# PX4FMUv2_4_3.net
KiCad netlist of a schematic drawn in EAGLE
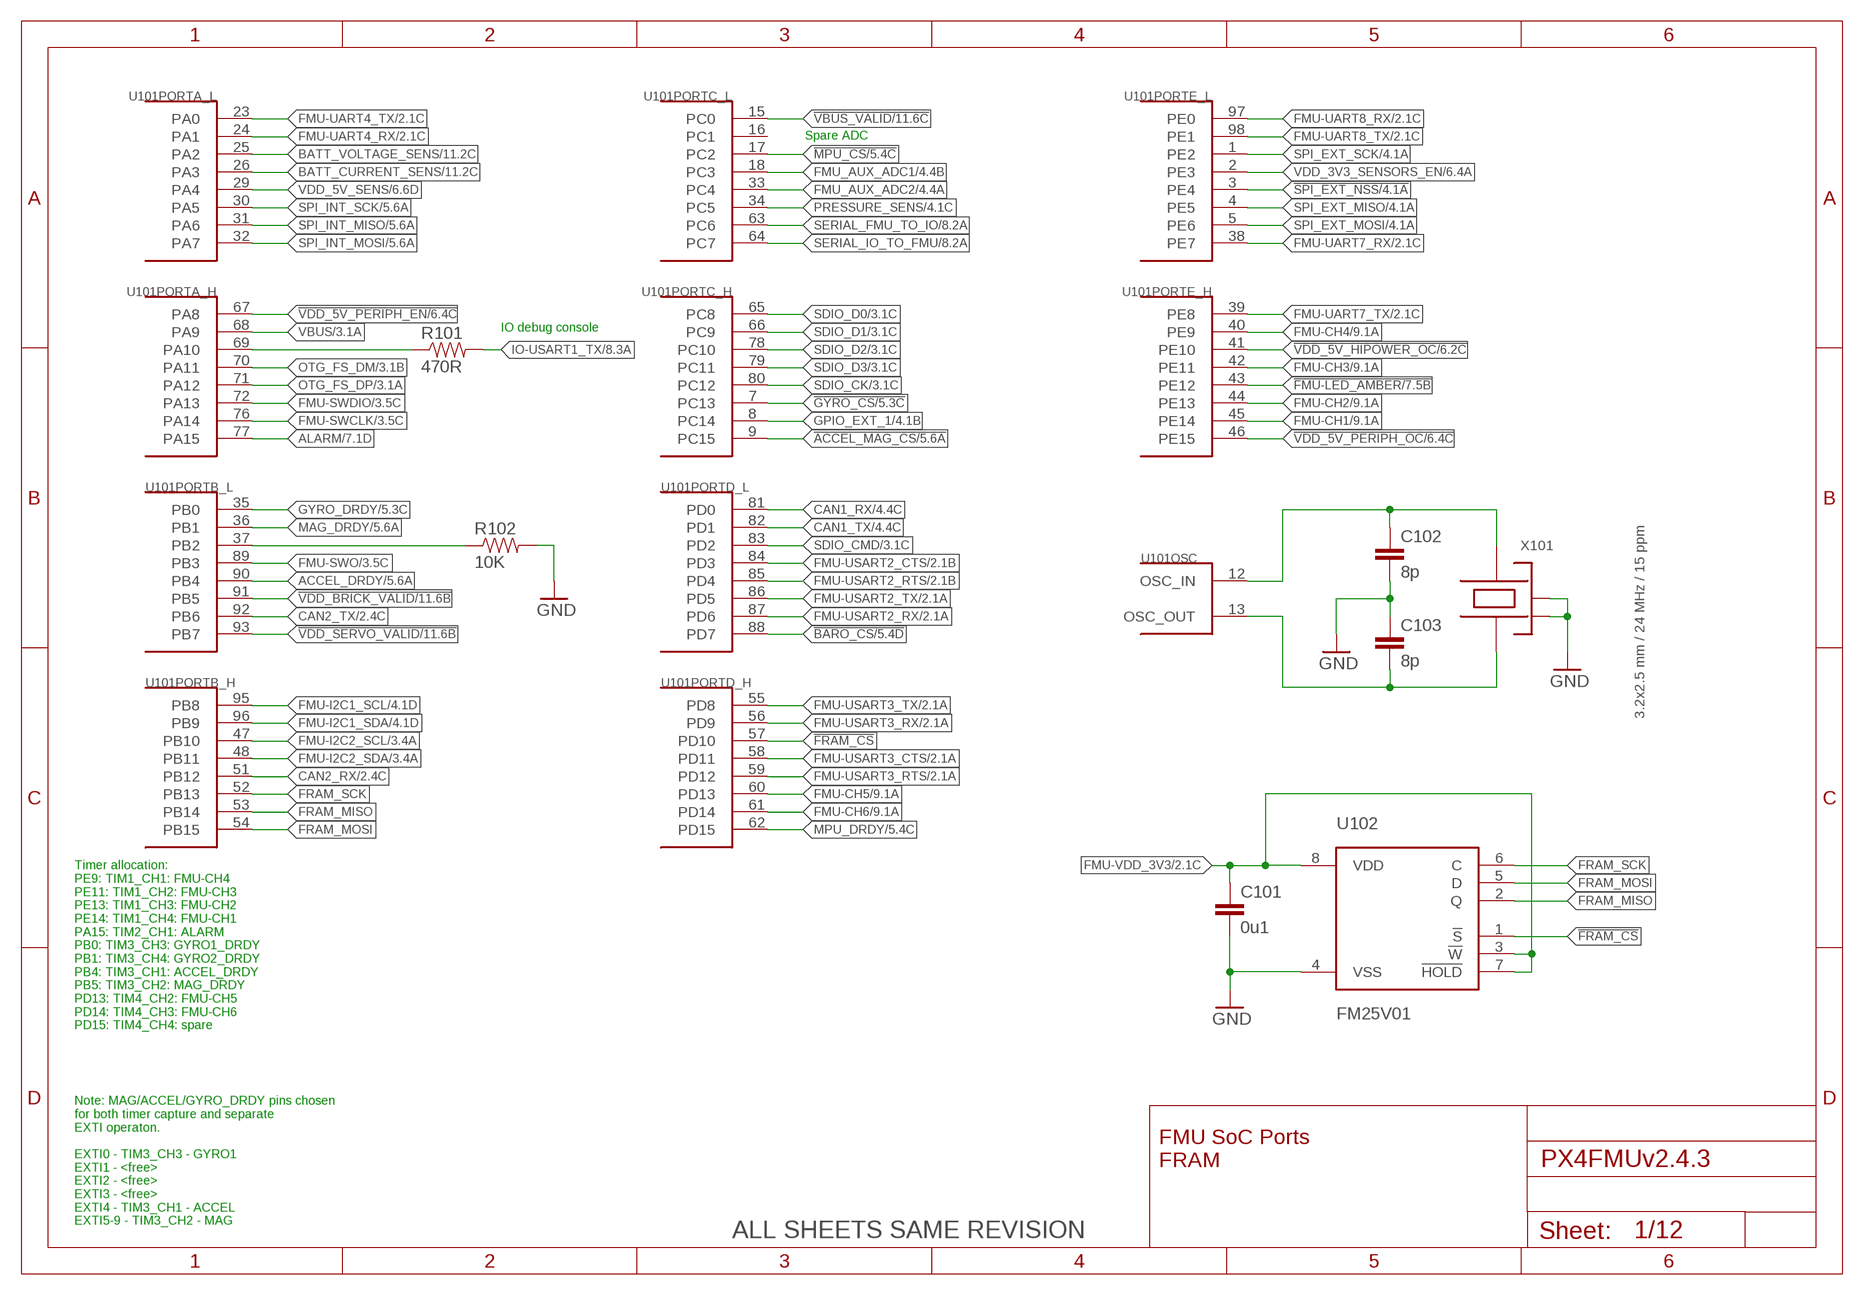
[diagram p0: schematic, sheet 1]
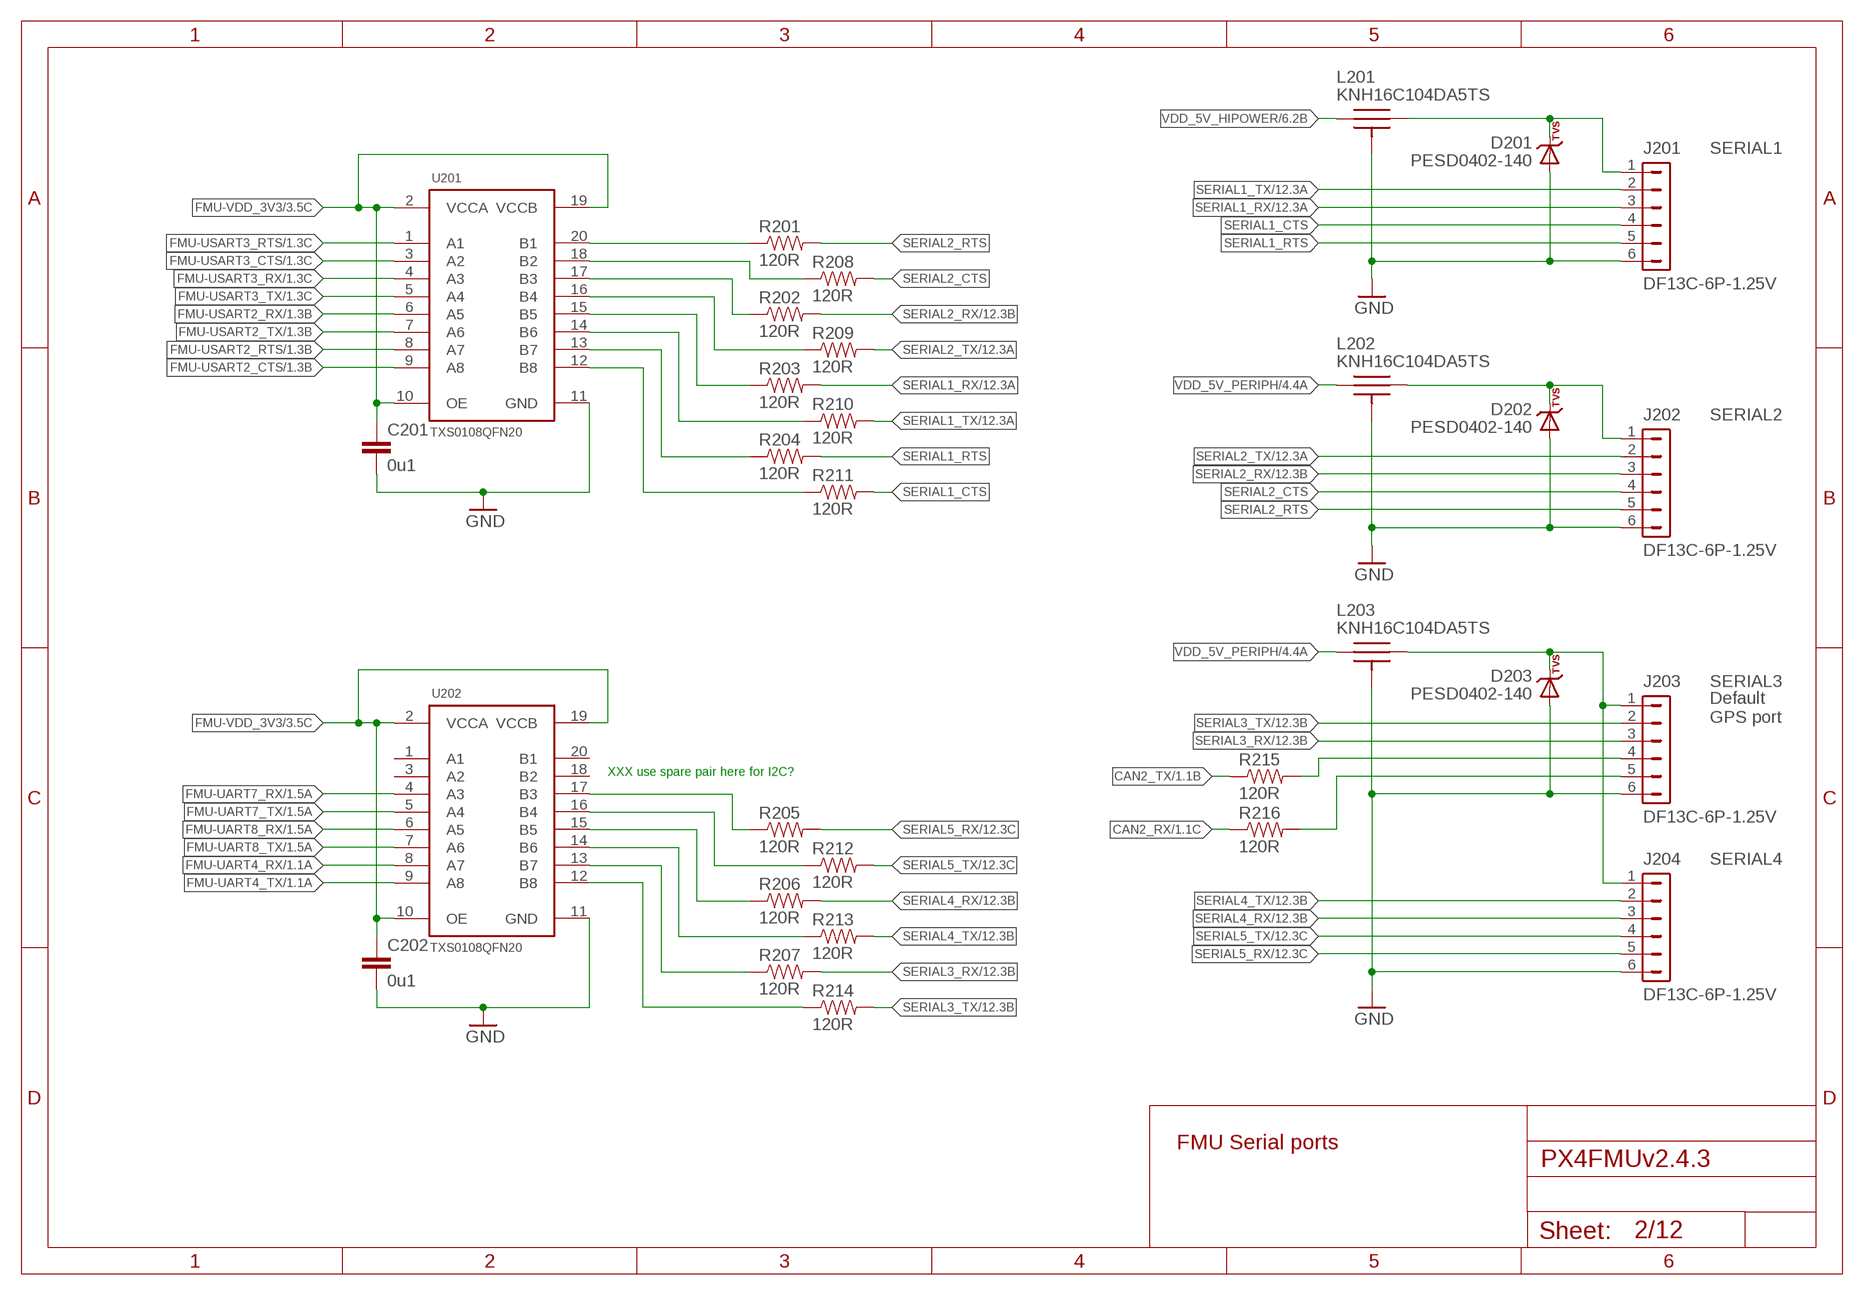
[diagram p1: schematic, sheet 2]
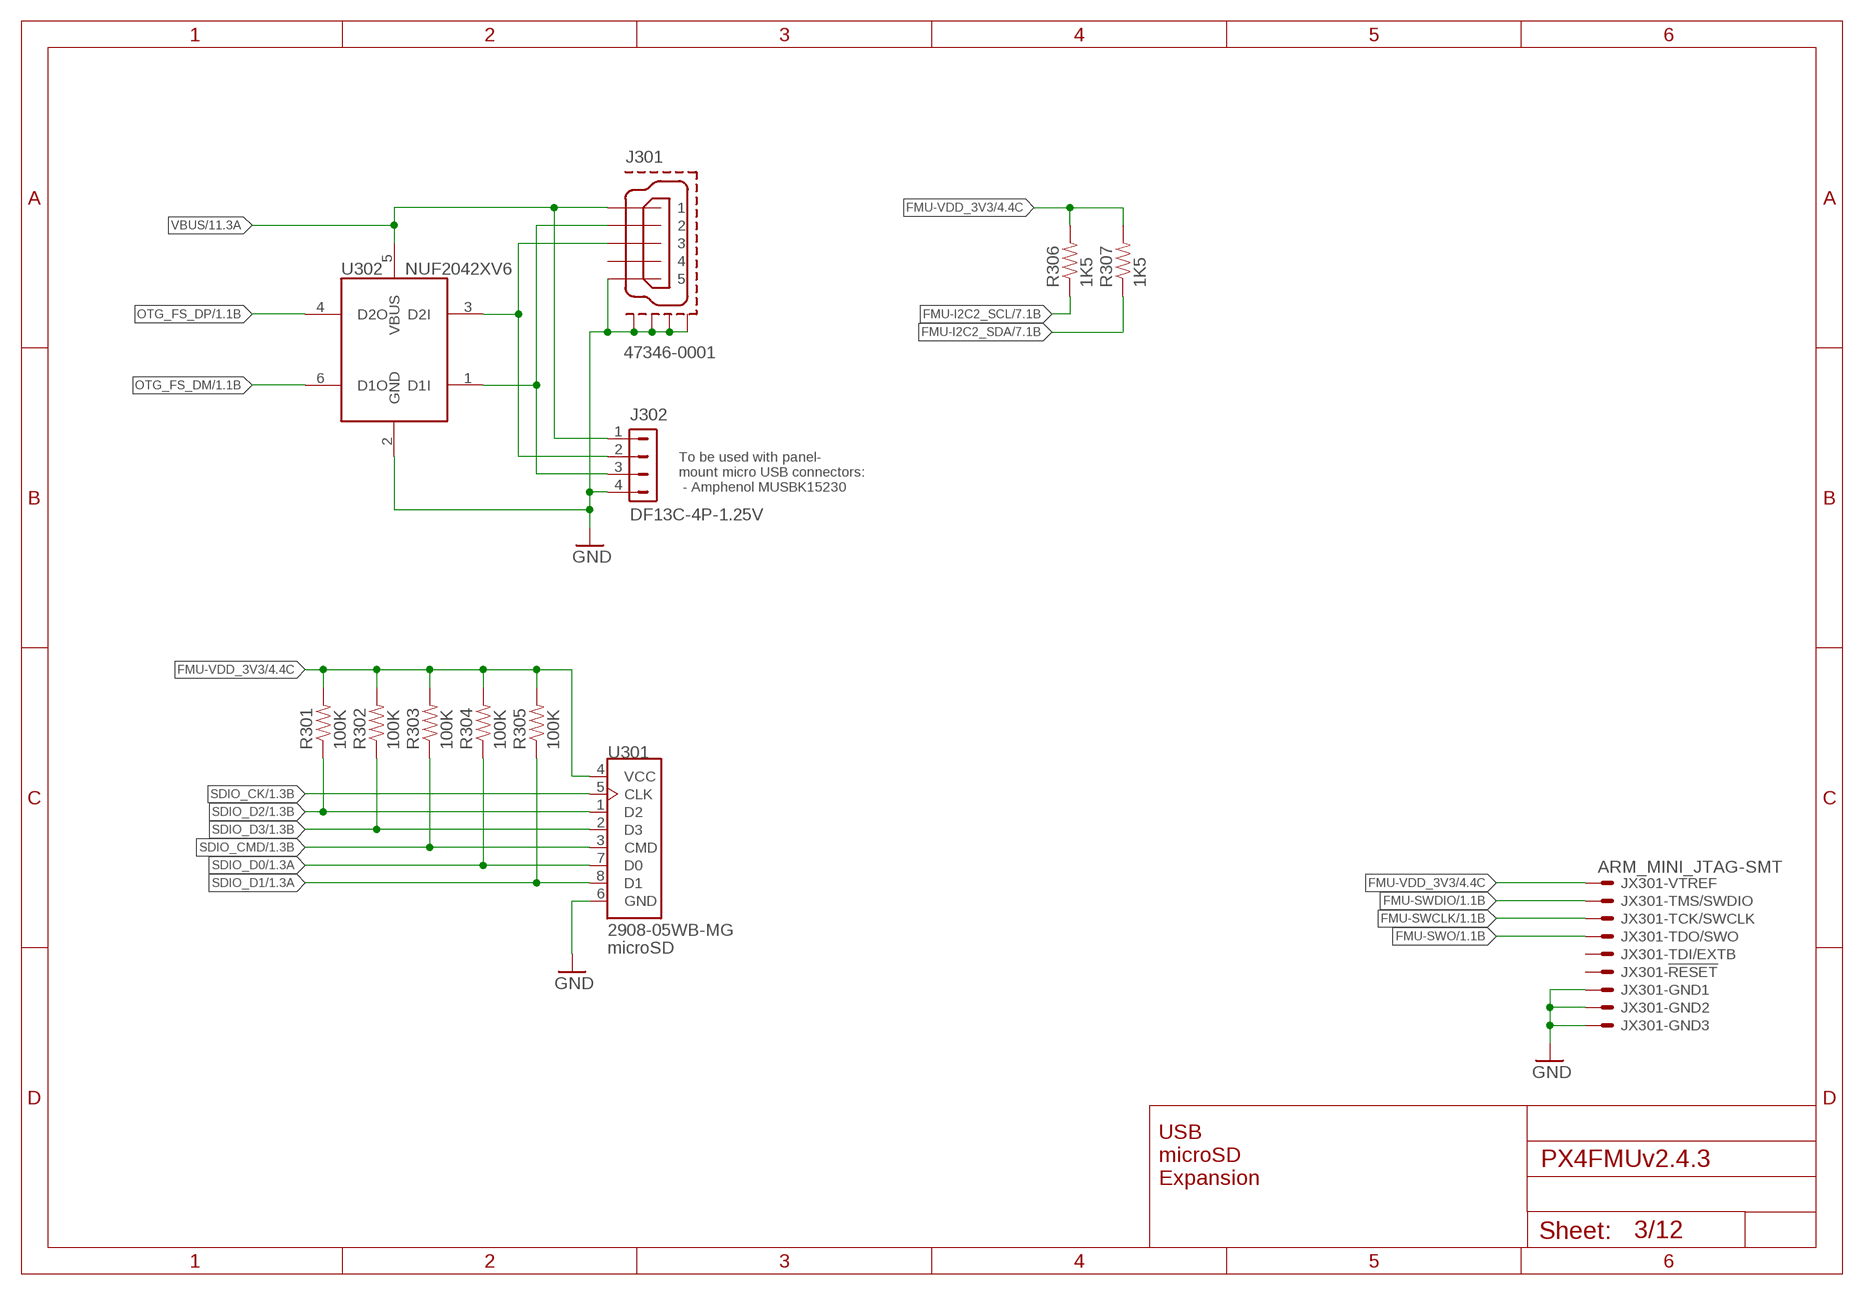
[diagram p2: schematic, sheet 3]
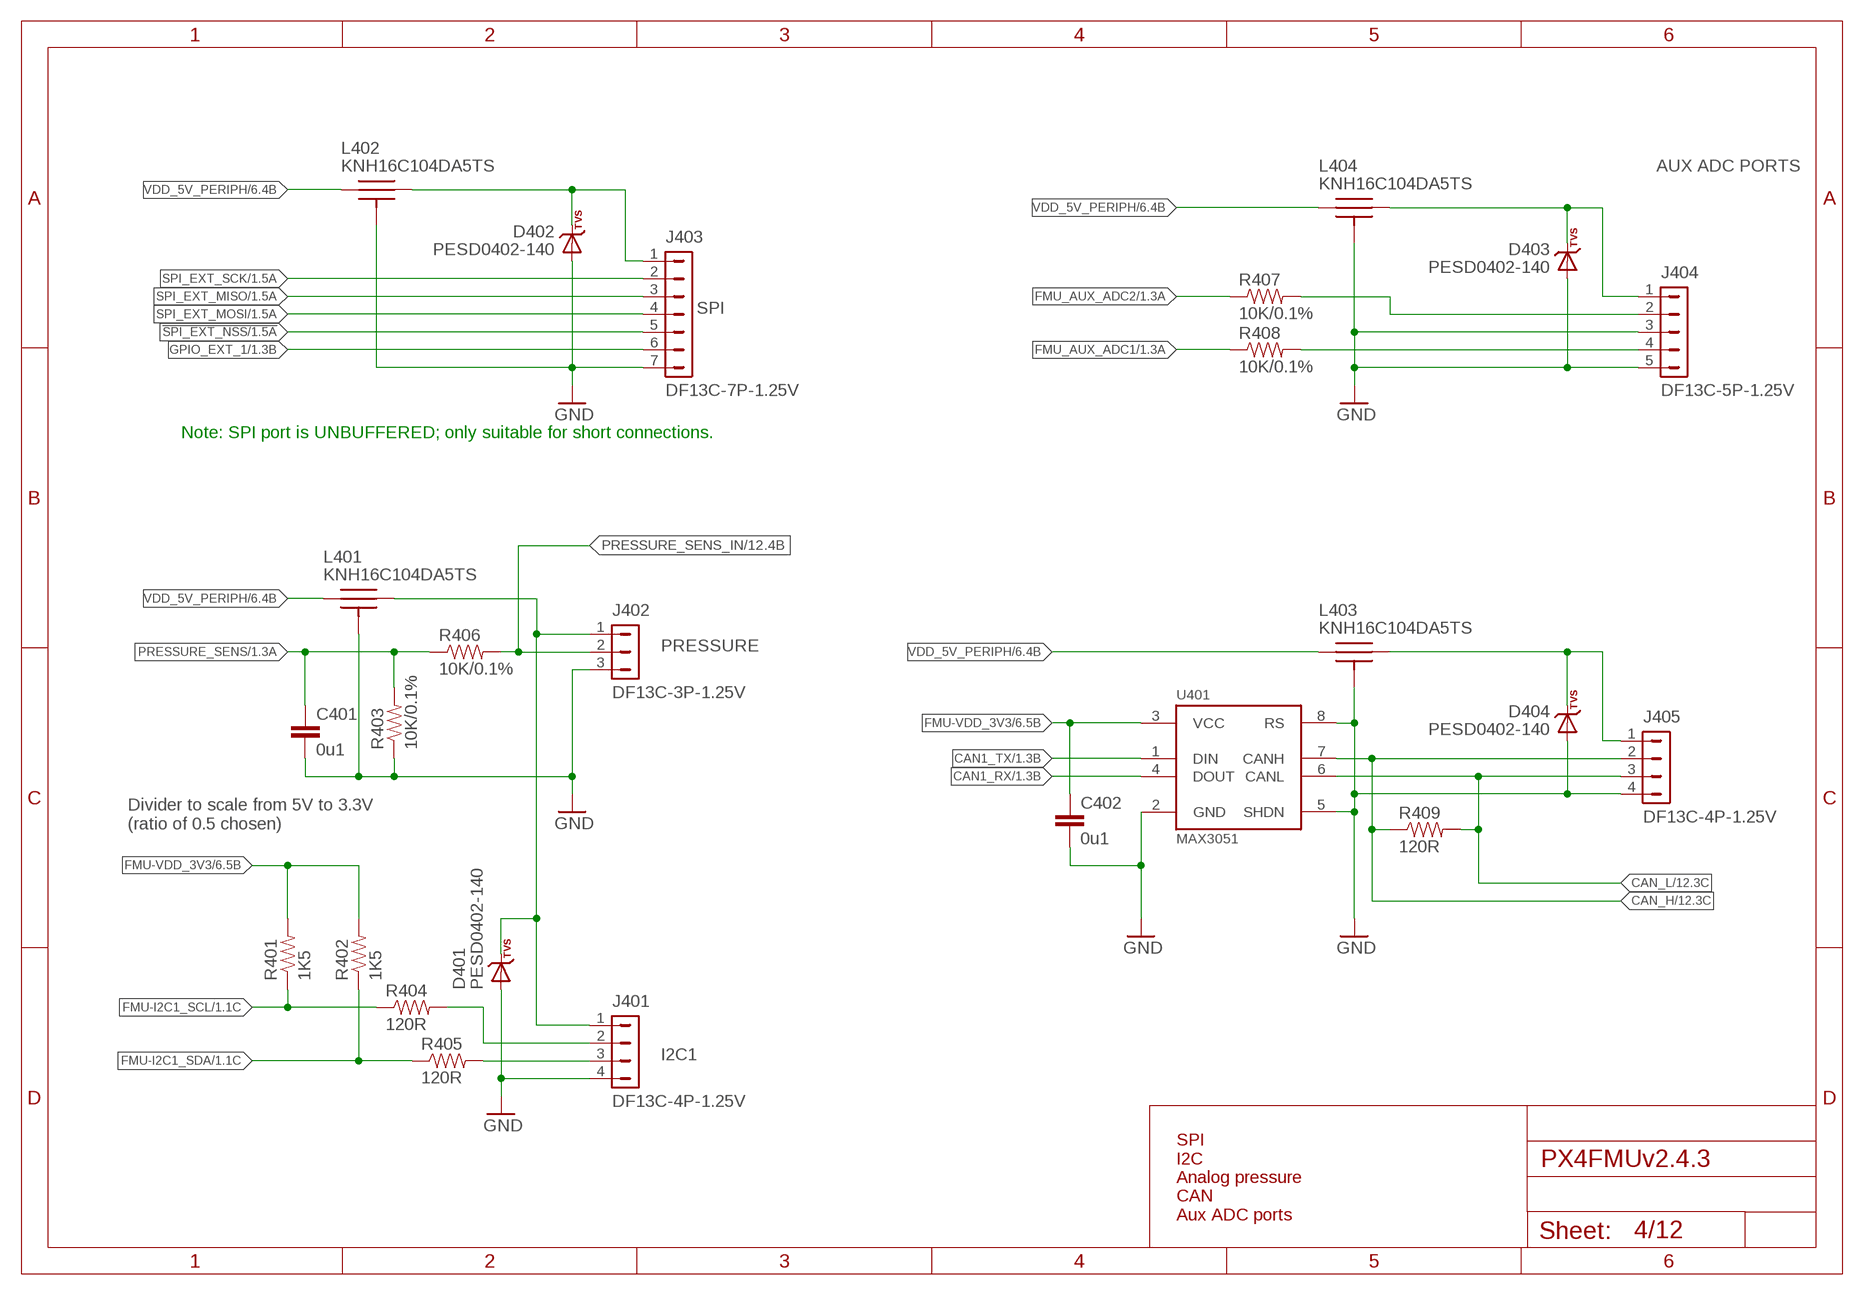
[diagram p3: schematic, sheet 4]
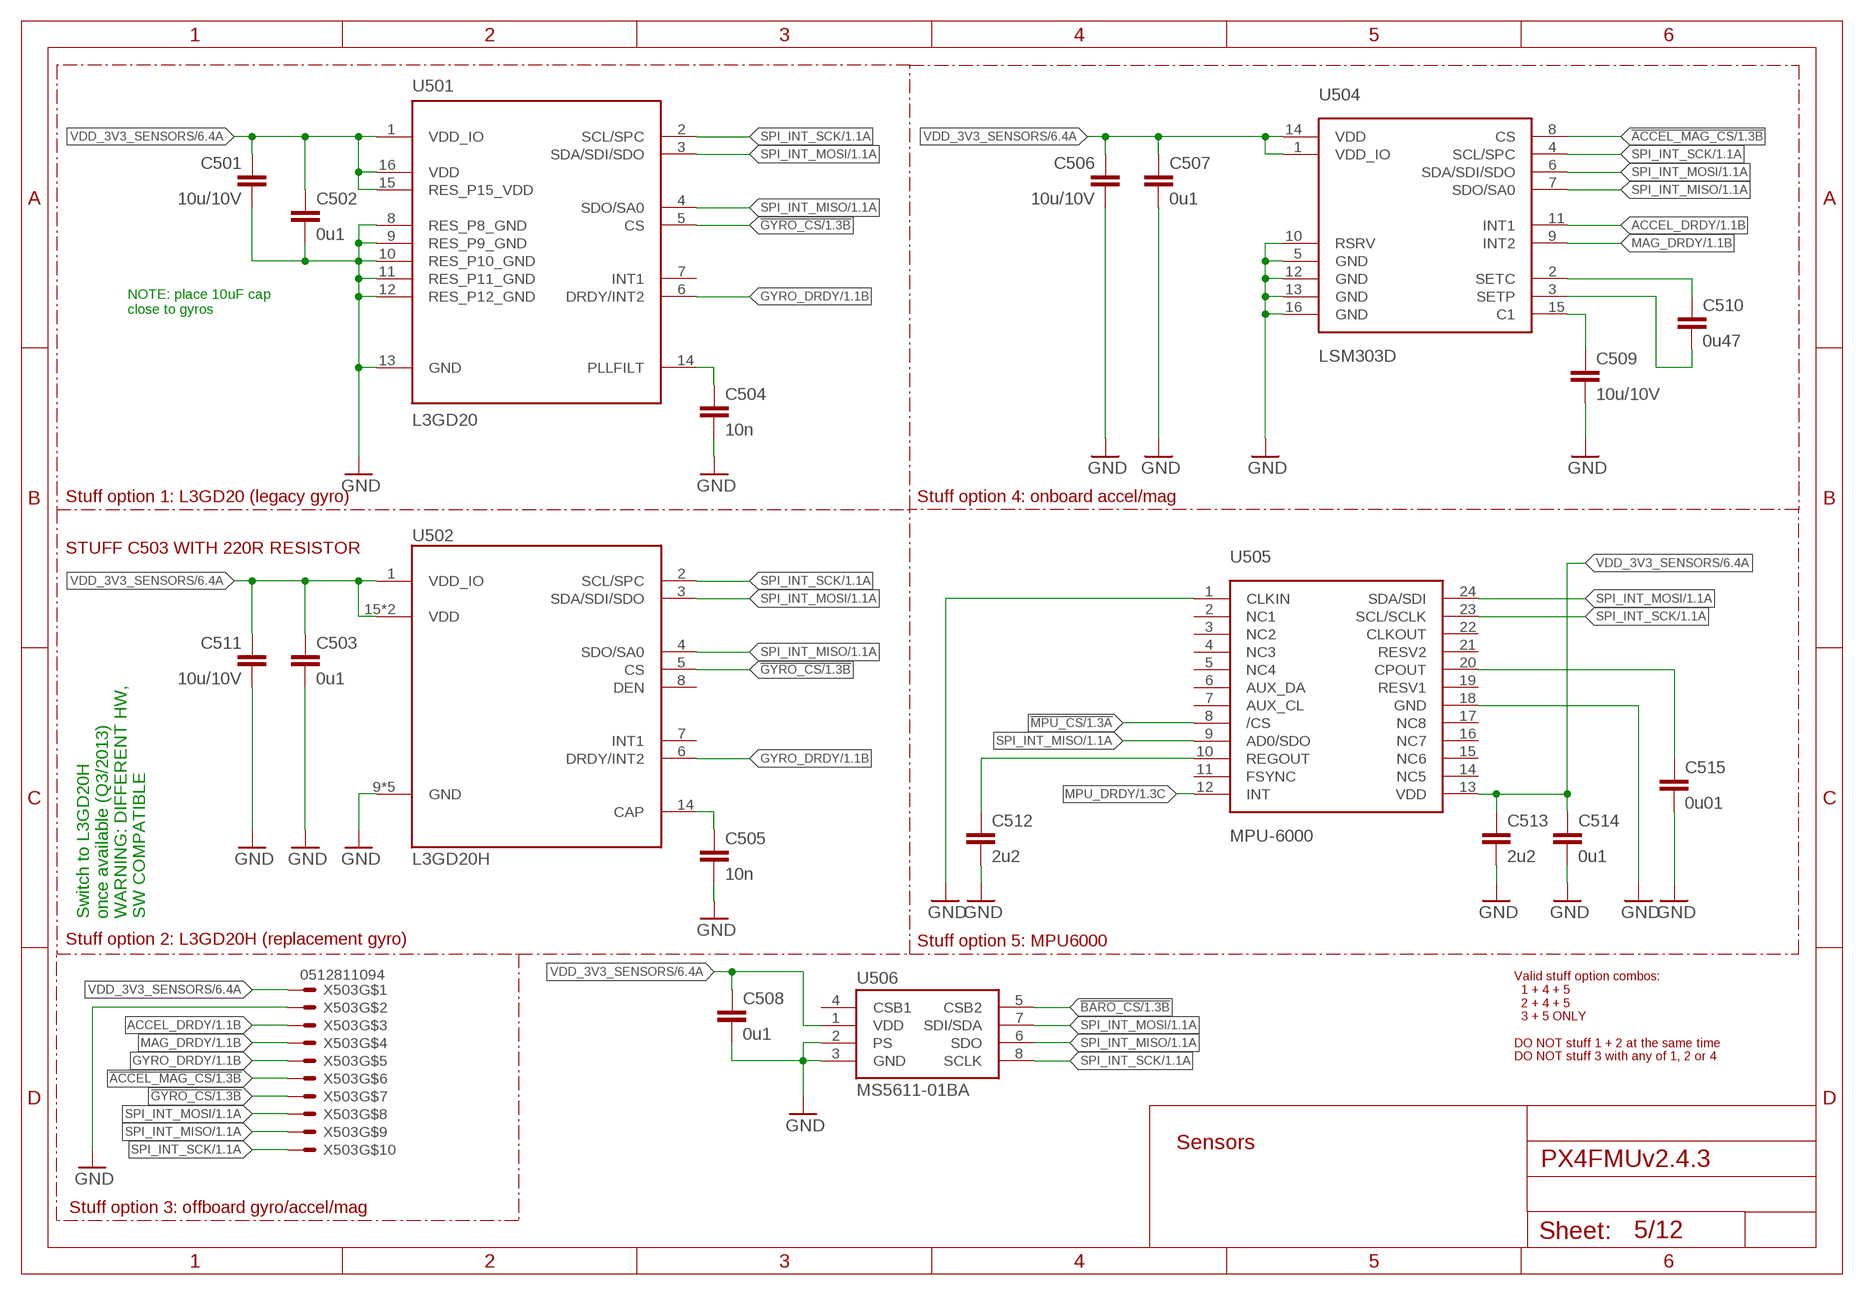
[diagram p4: schematic, sheet 5]
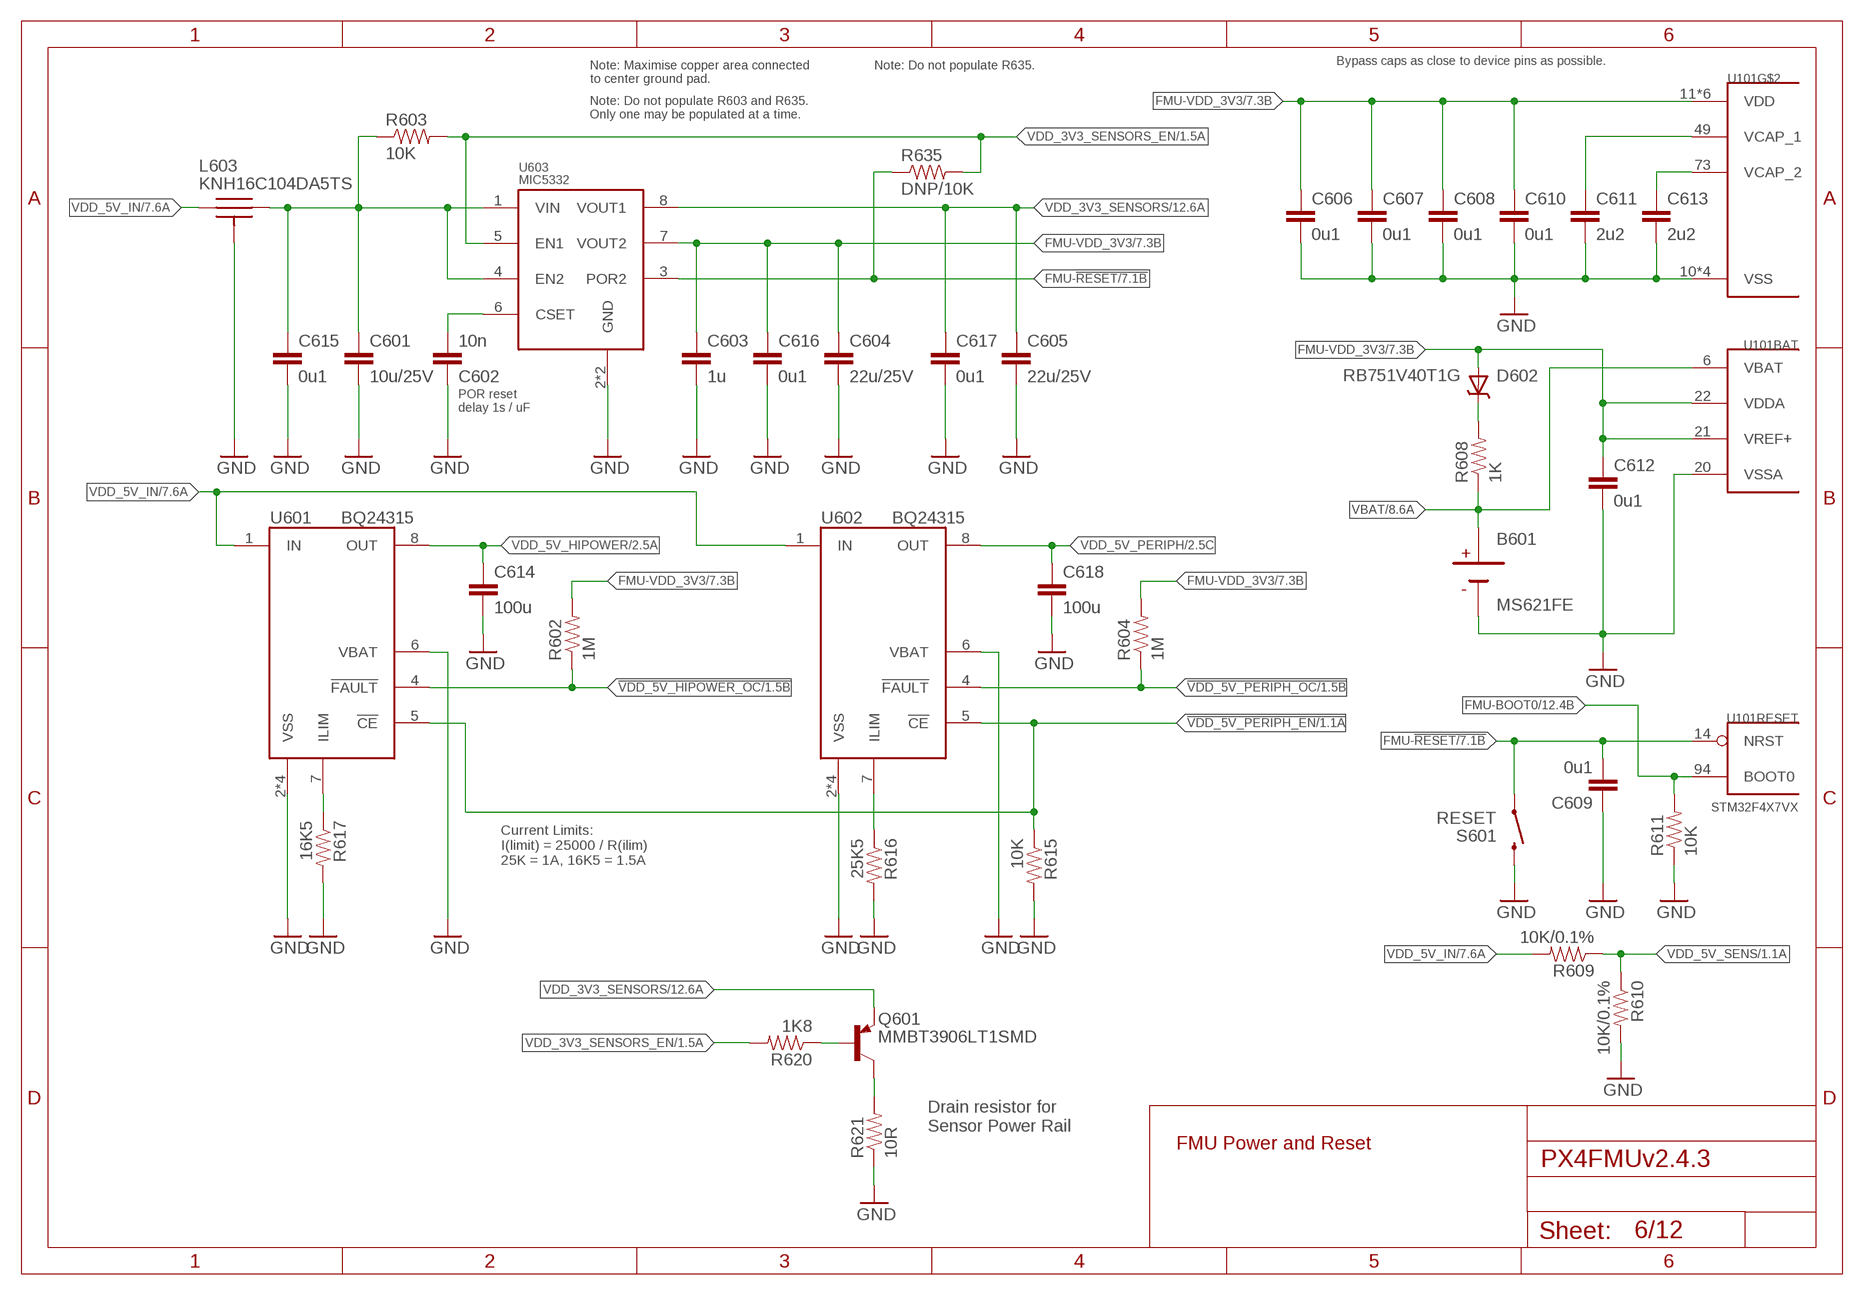
[diagram p5: schematic, sheet 6]
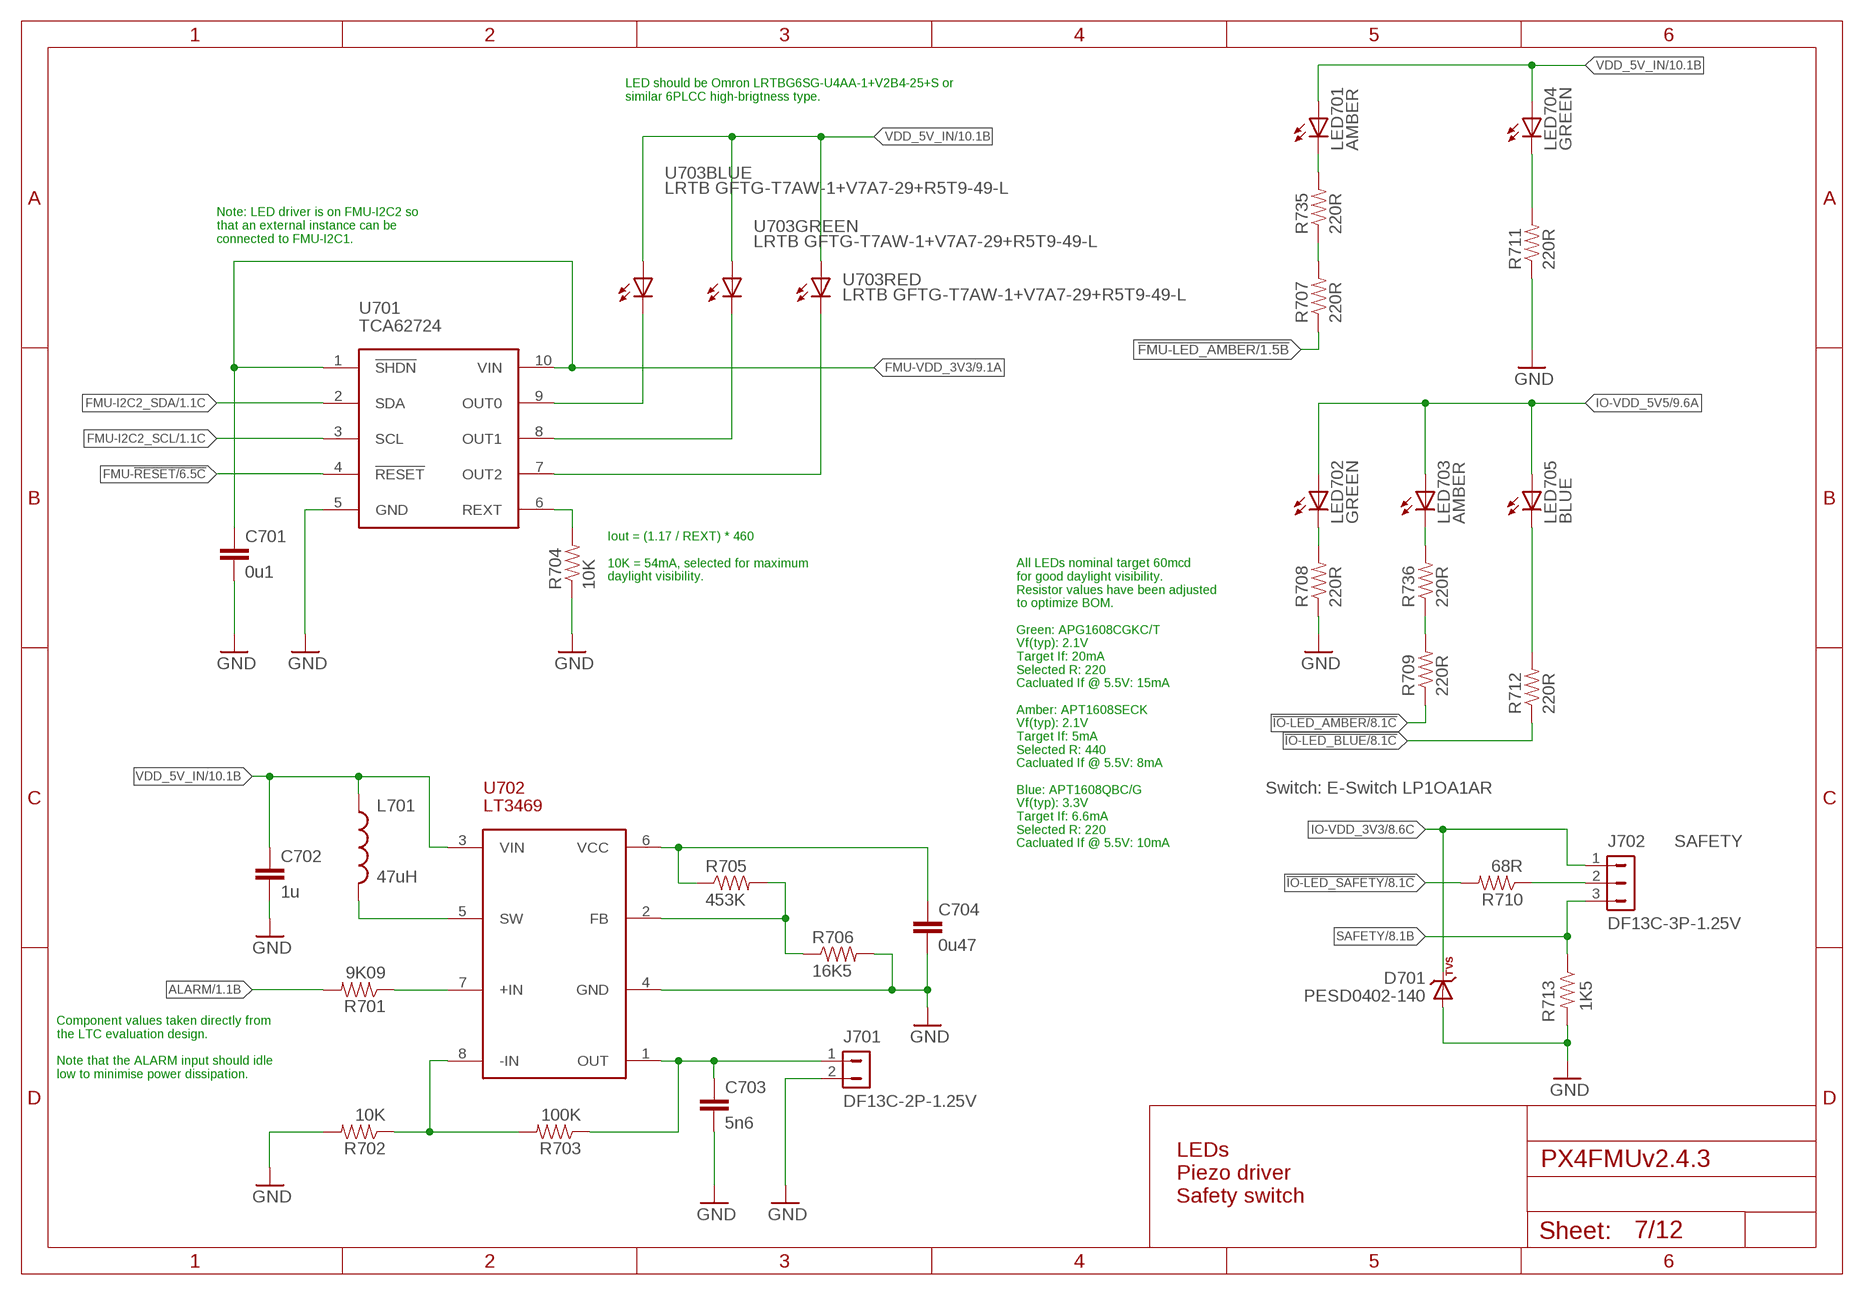
[diagram p6: schematic, sheet 7]
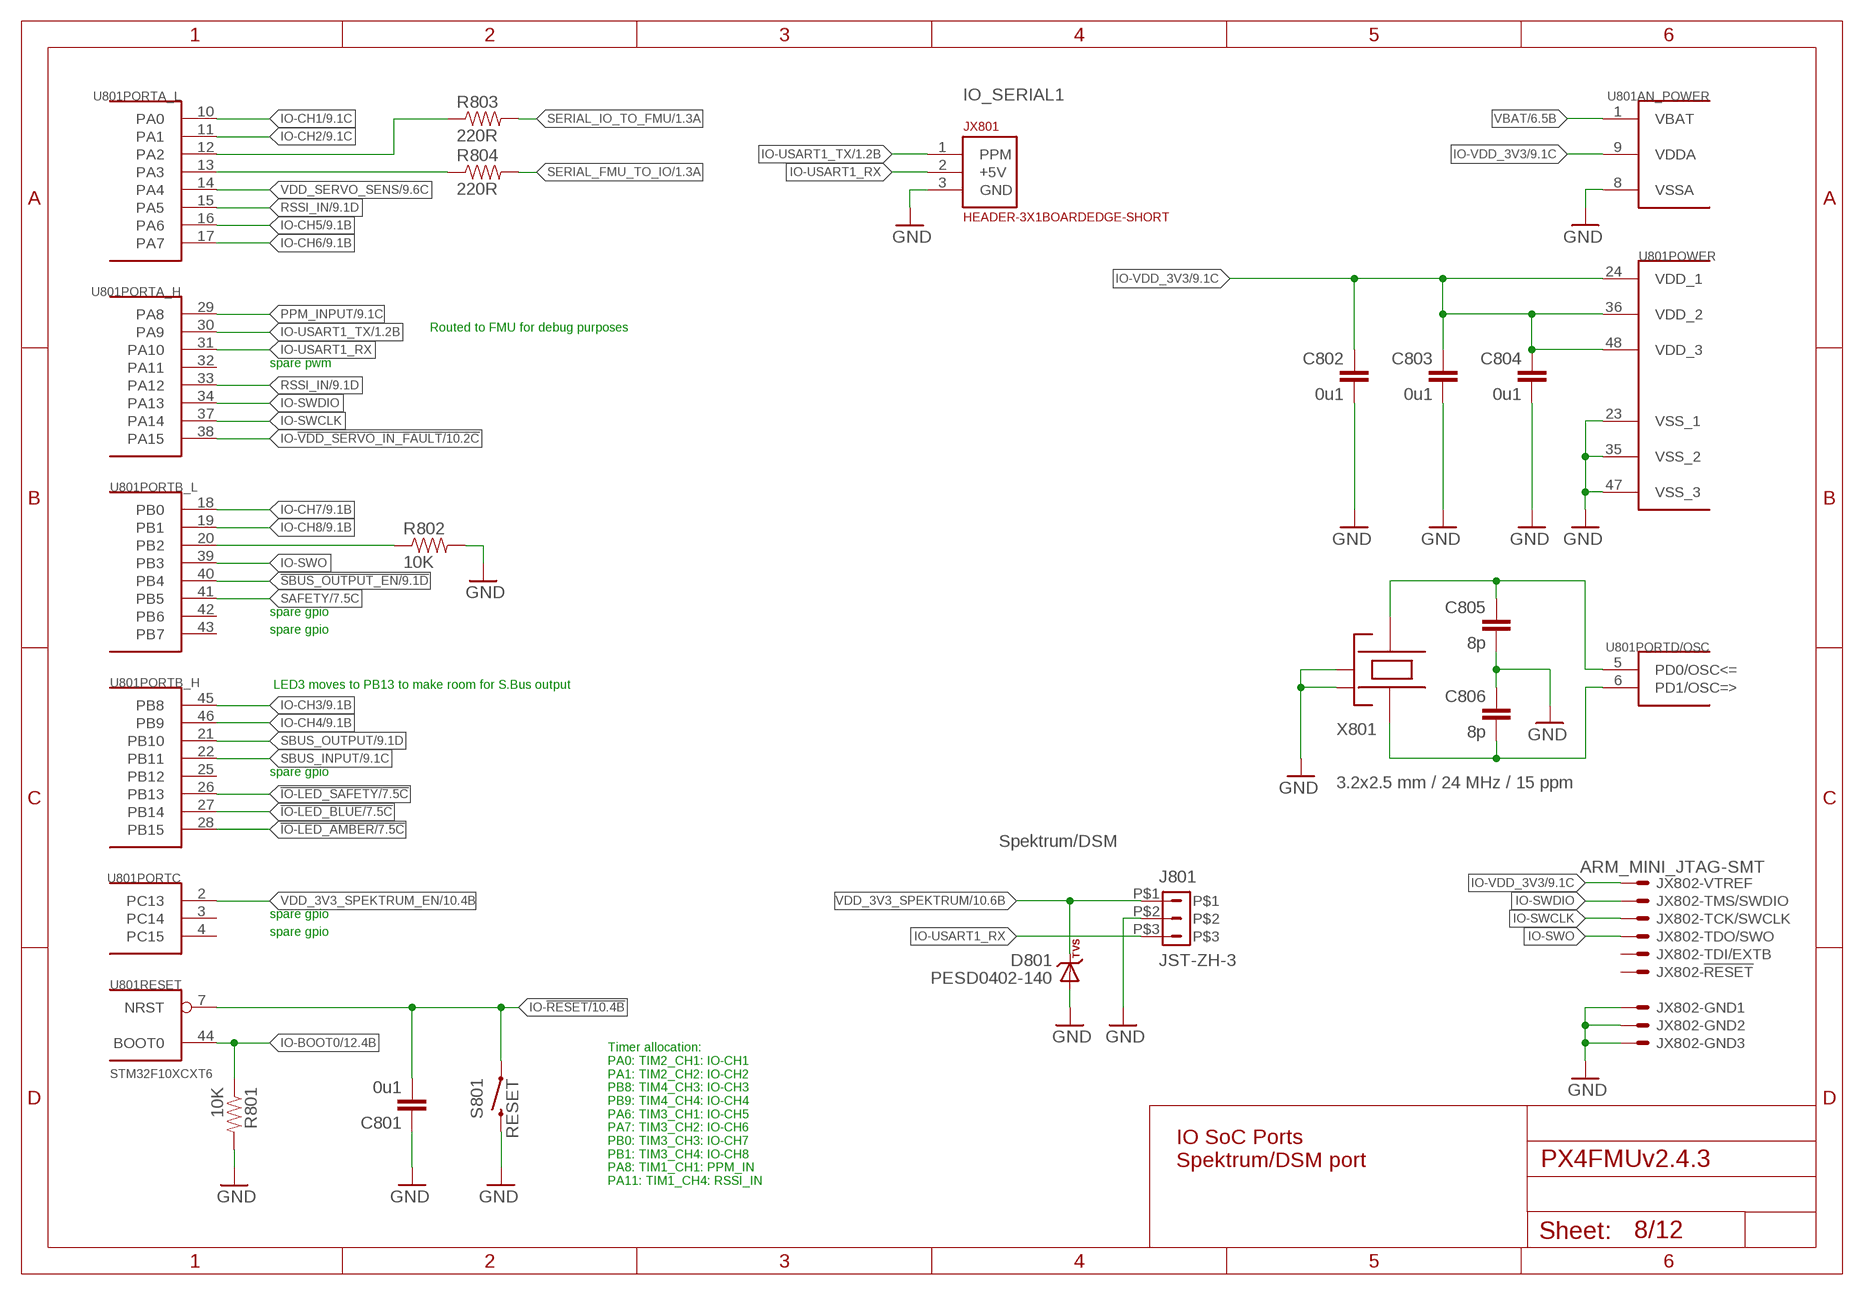
[diagram p7: schematic, sheet 8]
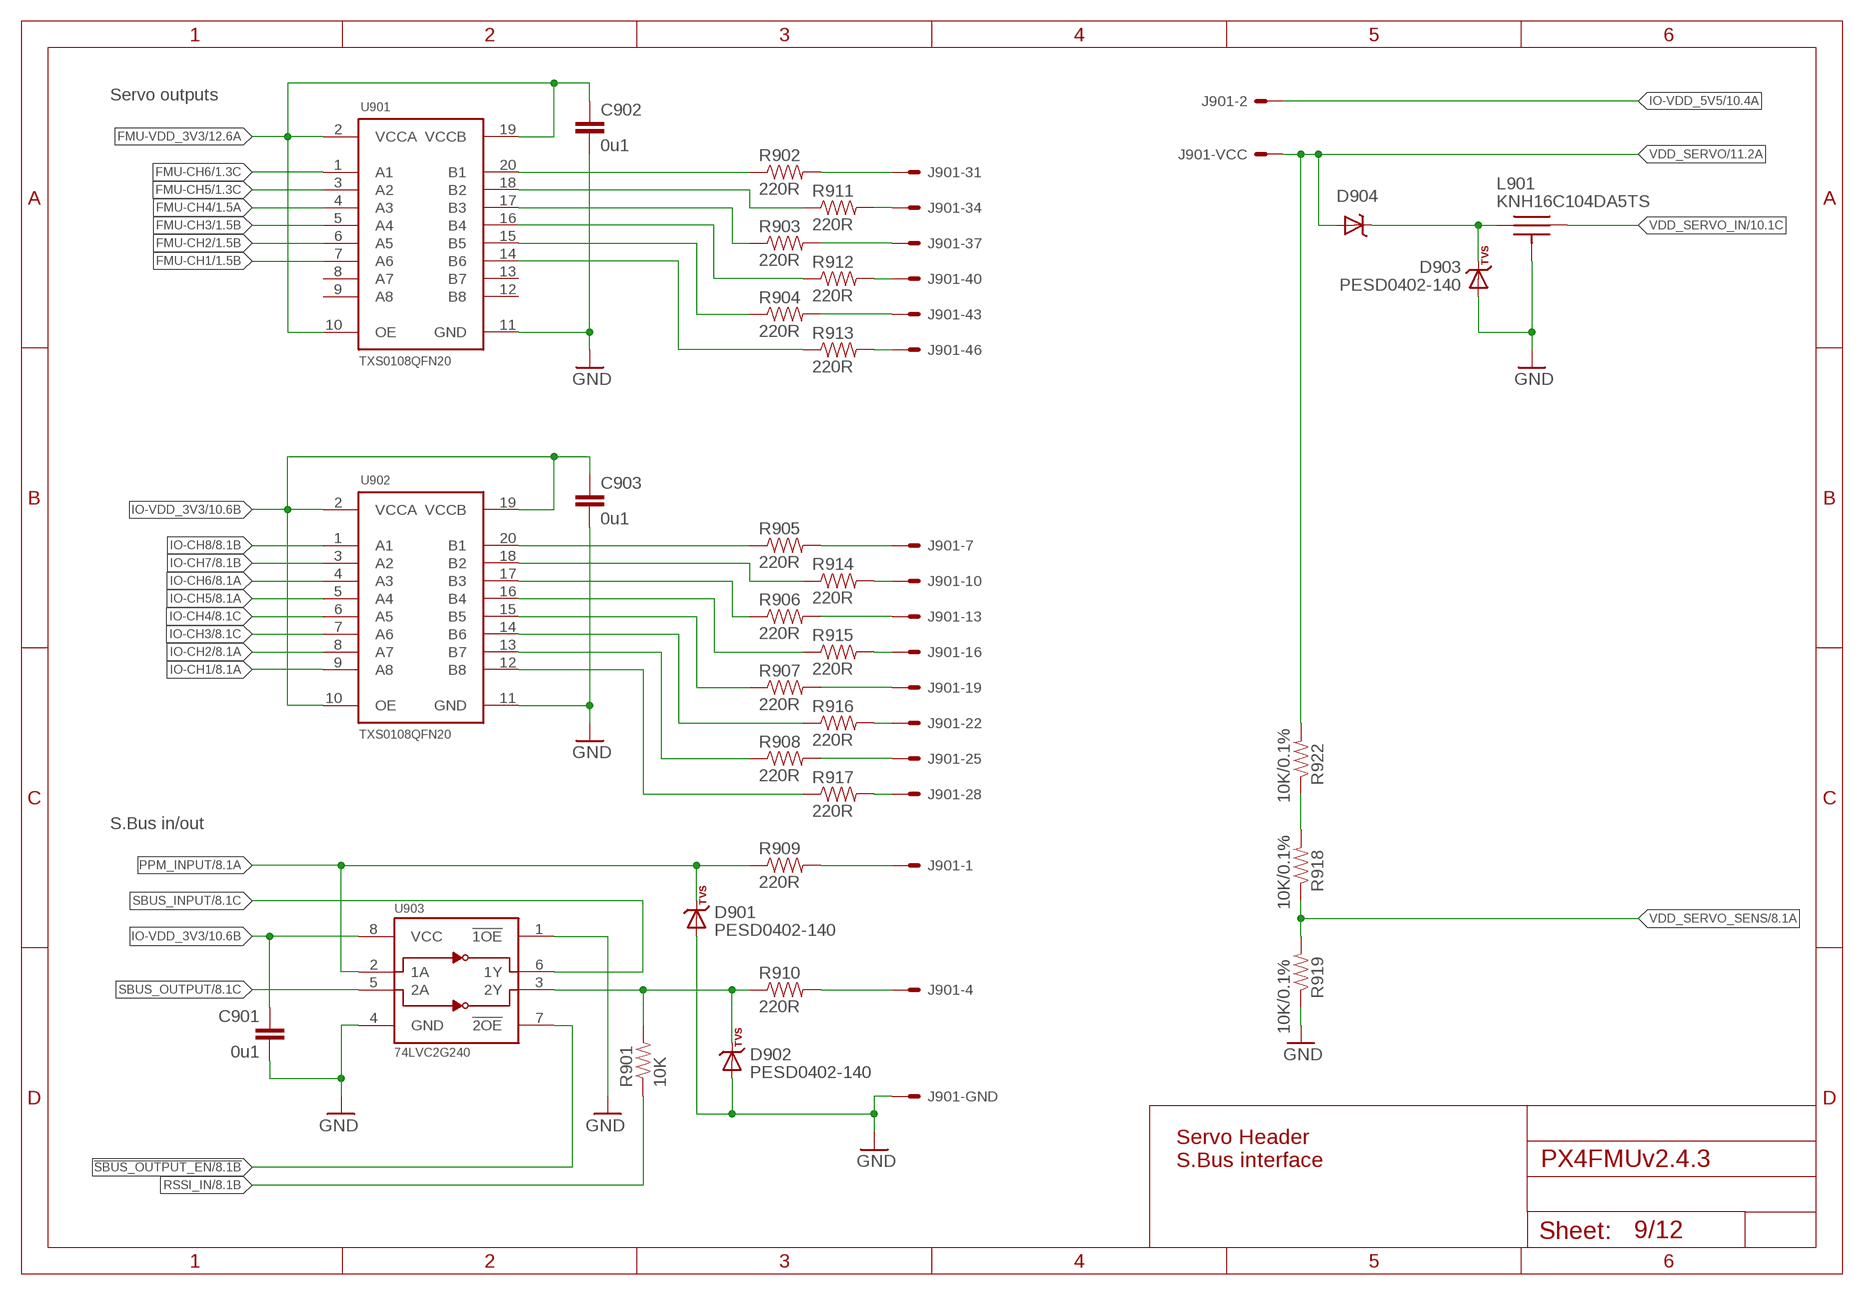
[diagram p8: schematic, sheet 9]
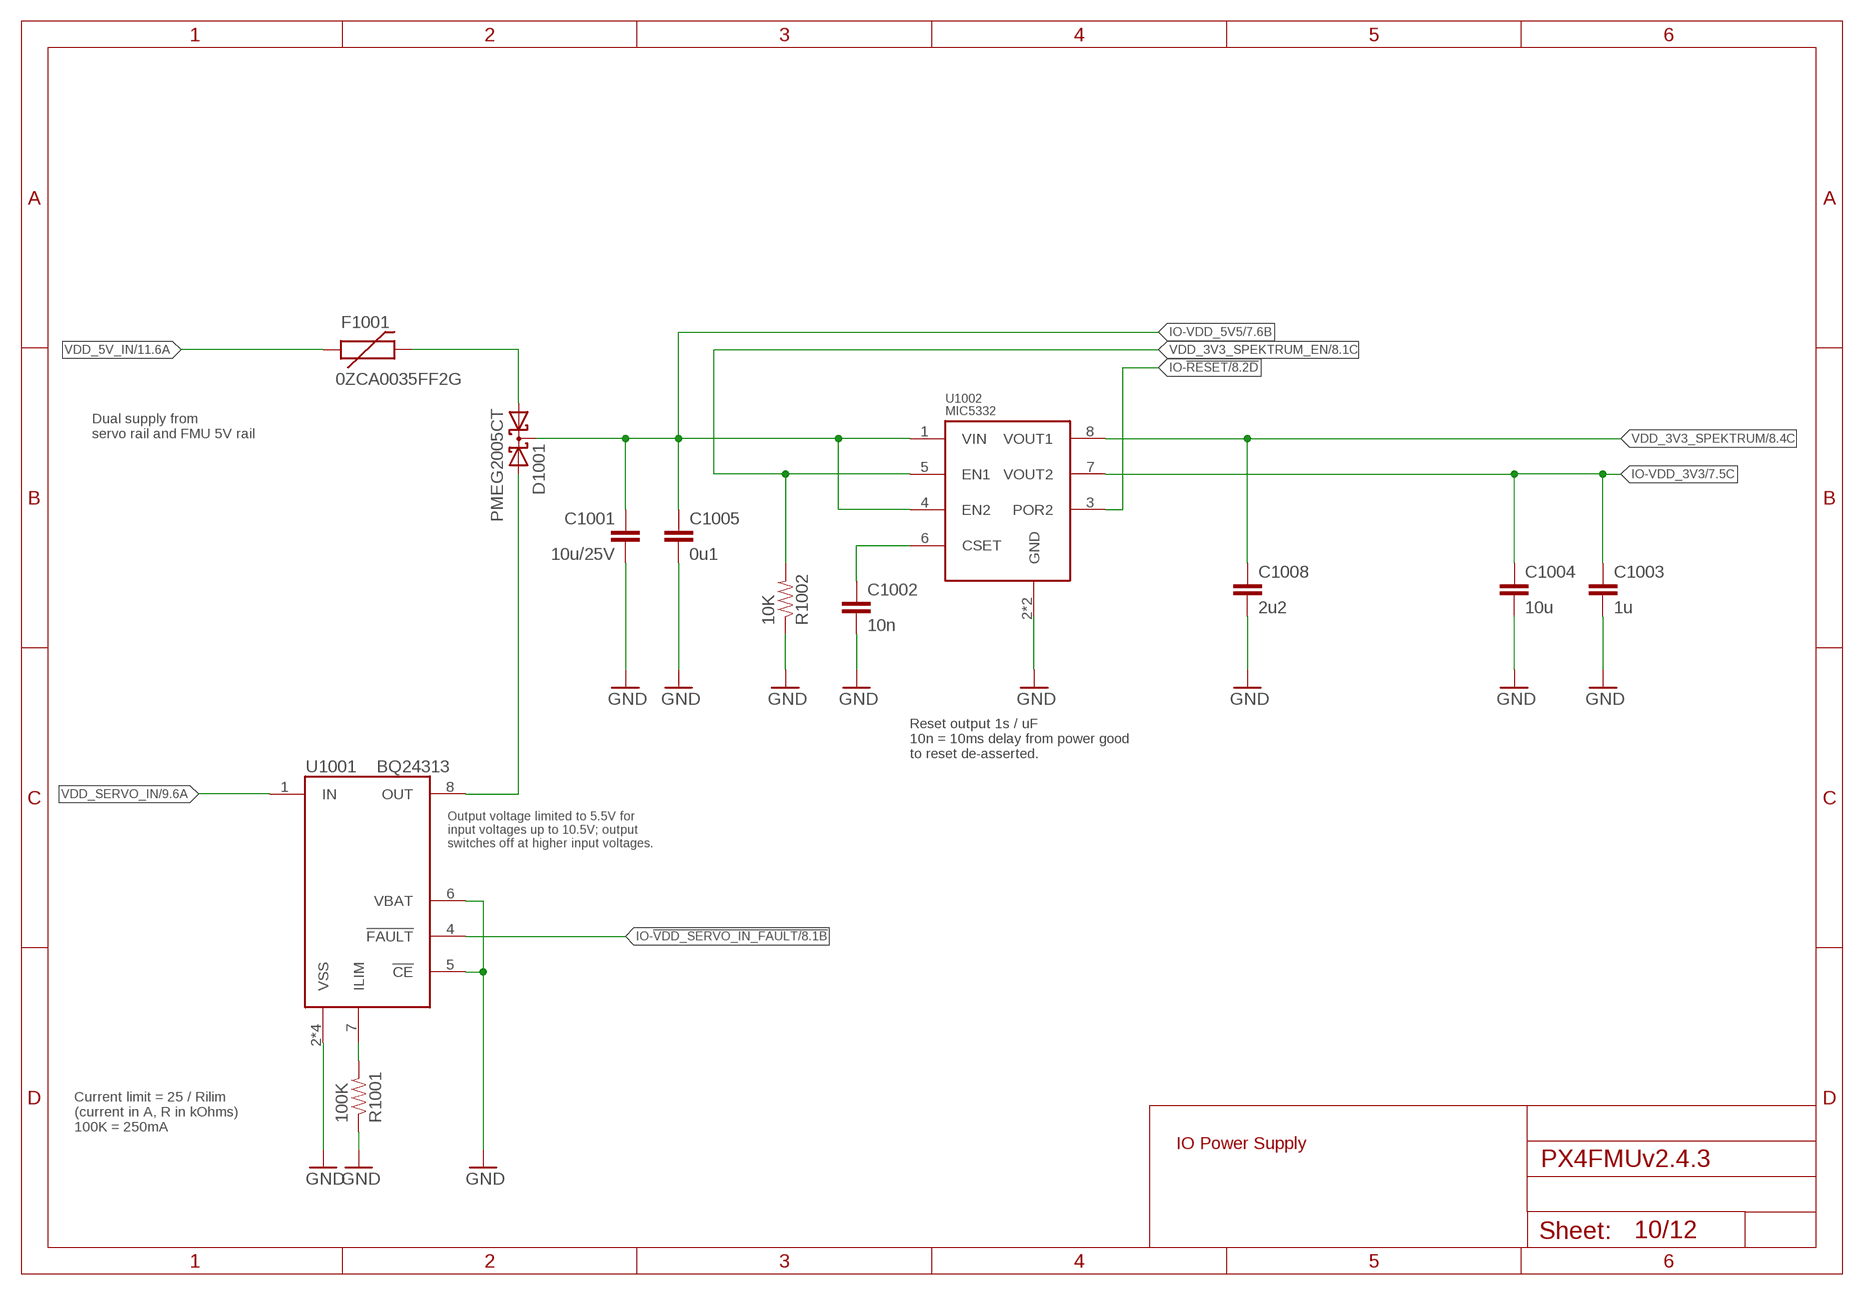
[diagram p9: schematic, sheet 10]
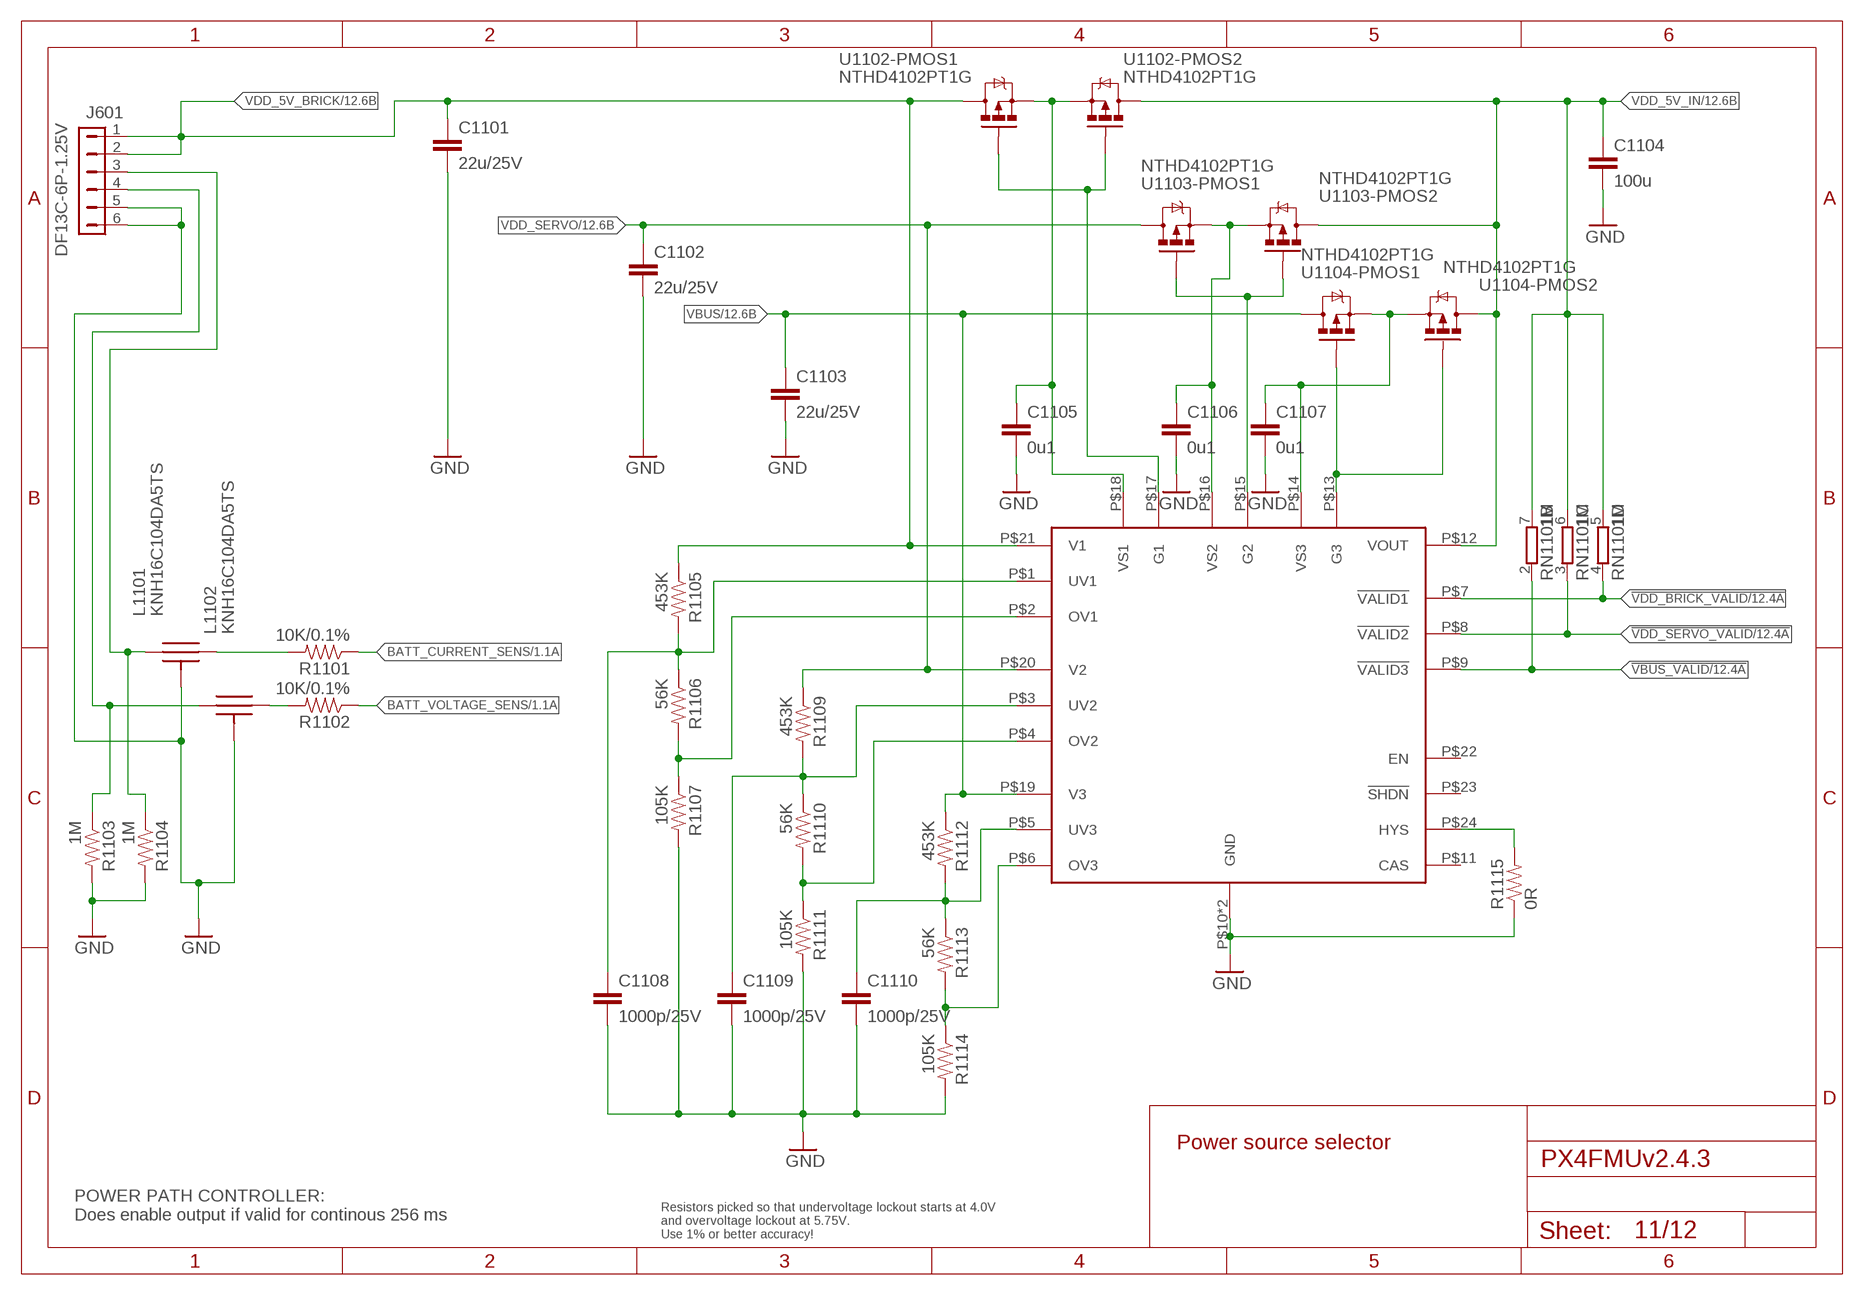
[diagram p10: schematic, sheet 11]
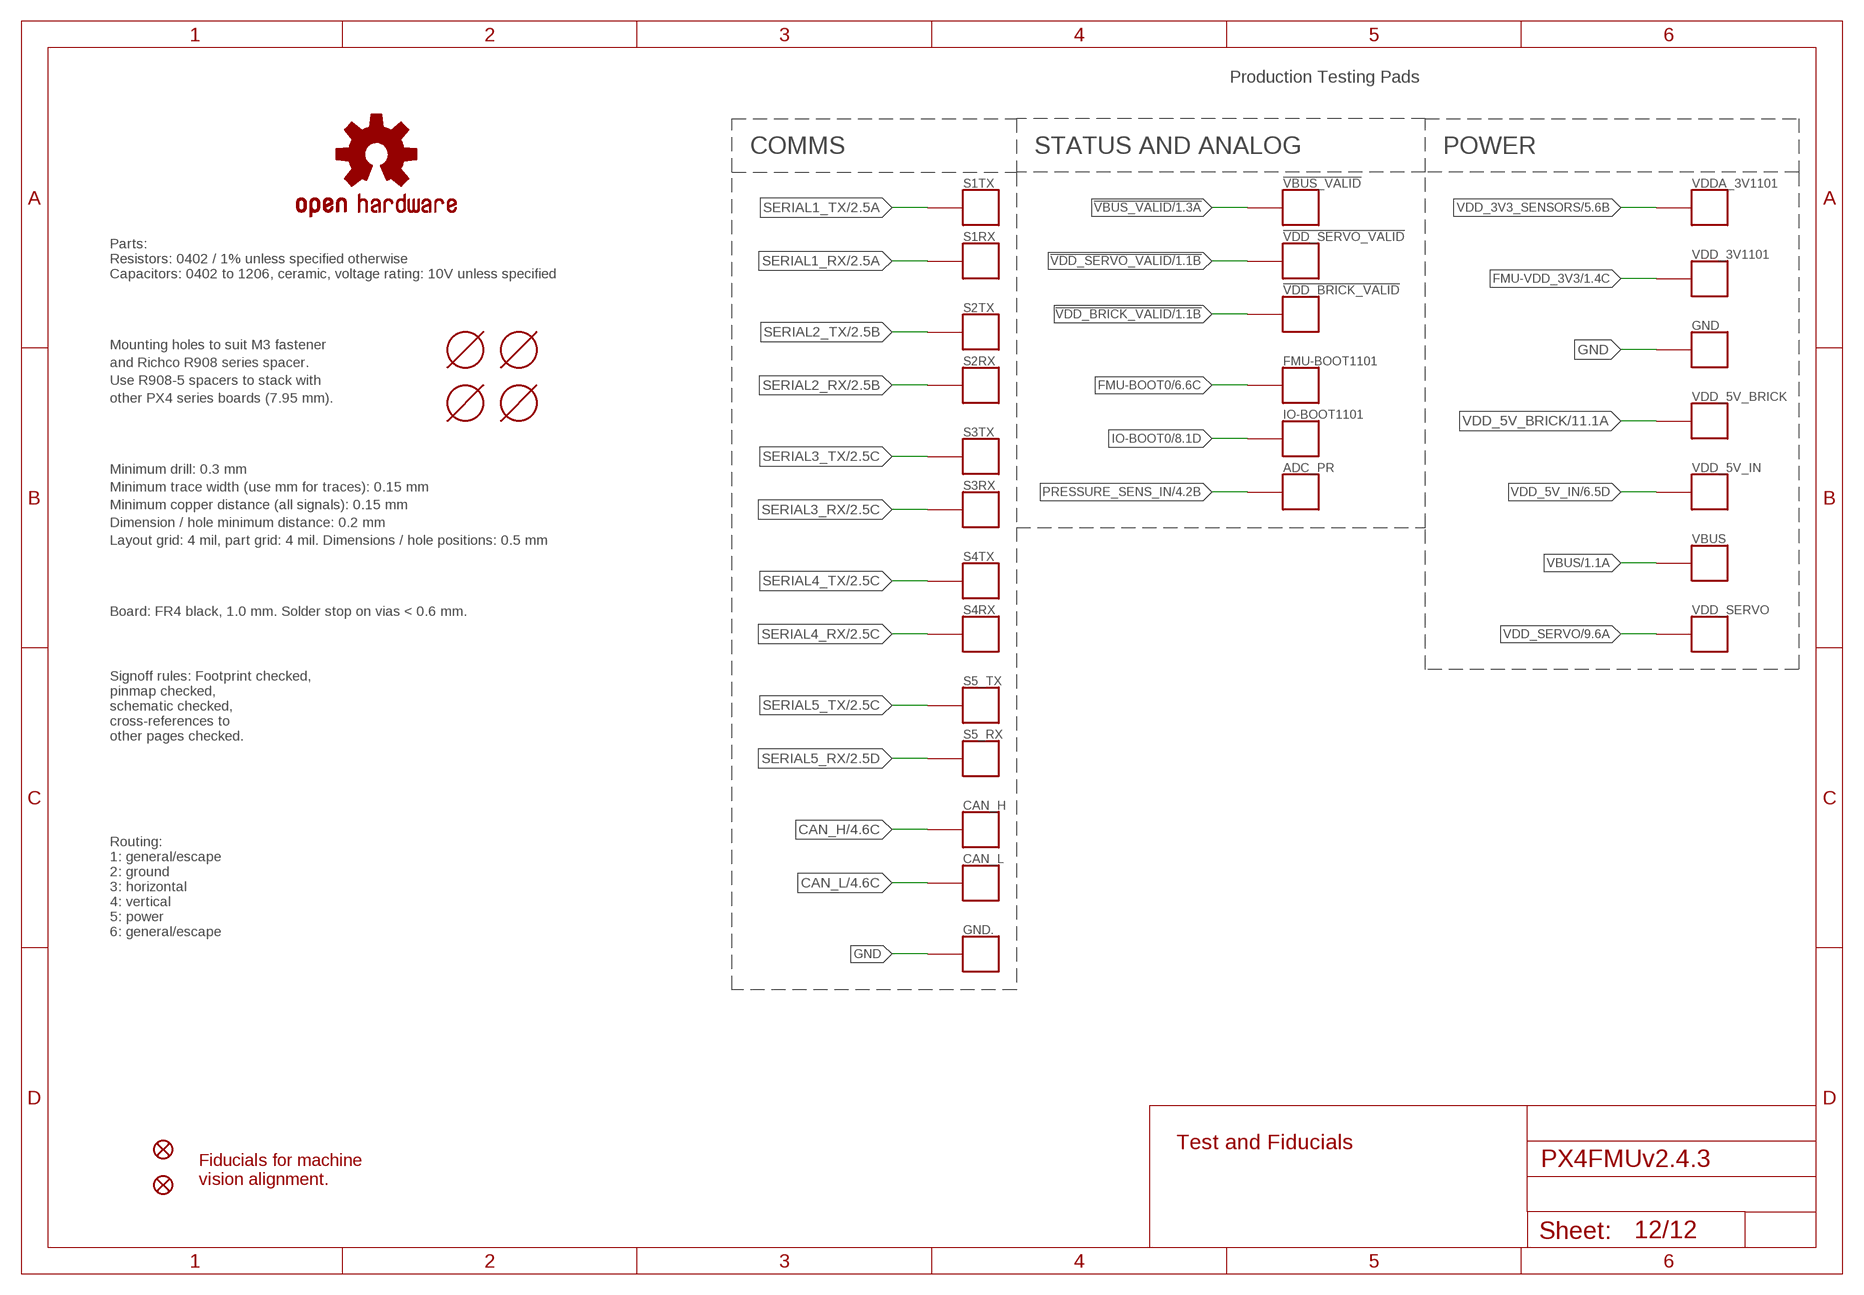
[diagram p11: schematic, sheet 12]

(export (version "E")
  (design (tool "Eeschema 10.0.6"))
  (components
    (comp (ref "!VBUS_VALID")
      (value "PAD.04")
      (footprint "eagle-import:PAD.04X.04")
      (libsource (lib "eagle-import") (part "PAD.04"))
    )
    (comp (ref "!VDD_BRICK_VALID")
      (value "PAD.04")
      (footprint "eagle-import:PAD.04X.04")
      (libsource (lib "eagle-import") (part "PAD.04"))
    )
    (comp (ref "!VDD_SERVO_VALID")
      (value "PAD.04")
      (footprint "eagle-import:PAD.04X.04")
      (libsource (lib "eagle-import") (part "PAD.04"))
    )
    (comp (ref "ADC_PR")
      (value "PAD.04")
      (footprint "eagle-import:PAD.04X.04")
      (libsource (lib "eagle-import") (part "PAD.04"))
    )
    (comp (ref "CAN_H")
      (value "PAD.04")
      (footprint "eagle-import:PAD.04X.04")
      (libsource (lib "eagle-import") (part "PAD.04"))
    )
    (comp (ref "CAN_L")
      (value "PAD.04")
      (footprint "eagle-import:PAD.04X.04")
      (libsource (lib "eagle-import") (part "PAD.04"))
    )
    (comp (ref "FMU-BOOT1101")
      (value "PAD.04")
      (footprint "eagle-import:PAD.04X.04")
      (libsource (lib "eagle-import") (part "PAD.04"))
    )
    (comp (ref "GND")
      (value "PAD.04")
      (footprint "eagle-import:PAD.04X.04")
      (libsource (lib "eagle-import") (part "PAD.04"))
    )
    (comp (ref "GND.")
      (value "PAD.04")
      (footprint "eagle-import:PAD.04X.04")
      (libsource (lib "eagle-import") (part "PAD.04"))
    )
    (comp (ref "IO-BOOT1101")
      (value "PAD.04")
      (footprint "eagle-import:PAD.04X.04")
      (libsource (lib "eagle-import") (part "PAD.04"))
    )
    (comp (ref "JP1")
      (value "FIDUCIAL1.5X3")
      (footprint "eagle-import:FIDUCIAL-1.5X3")
      (libsource (lib "eagle-import") (part "FIDUCIAL1.5X3"))
    )
    (comp (ref "JP2")
      (value "FIDUCIAL1.5X3")
      (footprint "eagle-import:FIDUCIAL-1.5X3")
      (libsource (lib "eagle-import") (part "FIDUCIAL1.5X3"))
    )
    (comp (ref "M3_MOUNT1101")
      (value "MOUNT-HOLE3.1MM")
      (footprint "eagle-import:MOUNT-HOLE3.1")
      (libsource (lib "eagle-import") (part "MOUNT-HOLE3.1MM"))
    )
    (comp (ref "M3_MOUNT1102")
      (value "MOUNT-HOLE3.1MM")
      (footprint "eagle-import:MOUNT-HOLE3.1")
      (libsource (lib "eagle-import") (part "MOUNT-HOLE3.1MM"))
    )
    (comp (ref "M3_MOUNT1103")
      (value "MOUNT-HOLE3.1MM")
      (footprint "eagle-import:MOUNT-HOLE3.1")
      (libsource (lib "eagle-import") (part "MOUNT-HOLE3.1MM"))
    )
    (comp (ref "M3_MOUNT1104")
      (value "MOUNT-HOLE3.1MM")
      (footprint "eagle-import:MOUNT-HOLE3.1")
      (libsource (lib "eagle-import") (part "MOUNT-HOLE3.1MM"))
    )
    (comp (ref "OSHW_LOGO")
      (value "OSHW-LOGOS")
      (footprint "eagle-import:OSHW-LOGO-S")
      (libsource (lib "eagle-import") (part "OSHW-LOGOS"))
    )
    (comp (ref "S1RX")
      (value "PAD.04")
      (footprint "eagle-import:PAD.04X.04")
      (libsource (lib "eagle-import") (part "PAD.04"))
    )
    (comp (ref "S1TX")
      (value "PAD.04")
      (footprint "eagle-import:PAD.04X.04")
      (libsource (lib "eagle-import") (part "PAD.04"))
    )
    (comp (ref "S2RX")
      (value "PAD.04")
      (footprint "eagle-import:PAD.04X.04")
      (libsource (lib "eagle-import") (part "PAD.04"))
    )
    (comp (ref "S2TX")
      (value "PAD.04")
      (footprint "eagle-import:PAD.04X.04")
      (libsource (lib "eagle-import") (part "PAD.04"))
    )
    (comp (ref "S3RX")
      (value "PAD.04")
      (footprint "eagle-import:PAD.04X.04")
      (libsource (lib "eagle-import") (part "PAD.04"))
    )
    (comp (ref "S3TX")
      (value "PAD.04")
      (footprint "eagle-import:PAD.04X.04")
      (libsource (lib "eagle-import") (part "PAD.04"))
    )
    (comp (ref "S4RX")
      (value "PAD.04")
      (footprint "eagle-import:PAD.04X.04")
      (libsource (lib "eagle-import") (part "PAD.04"))
    )
    (comp (ref "S4TX")
      (value "PAD.04")
      (footprint "eagle-import:PAD.04X.04")
      (libsource (lib "eagle-import") (part "PAD.04"))
    )
    (comp (ref "S5_RX")
      (value "PAD.04")
      (footprint "eagle-import:PAD.04X.04")
      (libsource (lib "eagle-import") (part "PAD.04"))
    )
    (comp (ref "S5_TX")
      (value "PAD.04")
      (footprint "eagle-import:PAD.04X.04")
      (libsource (lib "eagle-import") (part "PAD.04"))
    )
    (comp (ref "VBUS")
      (value "PAD.04")
      (footprint "eagle-import:PAD.04X.04")
      (libsource (lib "eagle-import") (part "PAD.04"))
    )
    (comp (ref "VDDA_3V1101")
      (value "PAD.04")
      (footprint "eagle-import:PAD.04X.04")
      (libsource (lib "eagle-import") (part "PAD.04"))
    )
    (comp (ref "VDD_3V1101")
      (value "PAD.04")
      (footprint "eagle-import:PAD.04X.04")
      (libsource (lib "eagle-import") (part "PAD.04"))
    )
    (comp (ref "VDD_5V_BRICK")
      (value "PAD.04")
      (footprint "eagle-import:PAD.04X.04")
      (libsource (lib "eagle-import") (part "PAD.04"))
    )
    (comp (ref "VDD_5V_IN")
      (value "PAD.04")
      (footprint "eagle-import:PAD.04X.04")
      (libsource (lib "eagle-import") (part "PAD.04"))
    )
    (comp (ref "VDD_SERVO")
      (value "PAD.04")
      (footprint "eagle-import:PAD.04X.04")
      (libsource (lib "eagle-import") (part "PAD.04"))
    )
    (comp (ref "C101")
      (value "0u1")
      (footprint "eagle-import:0402-CAP")
      (fields (field (name "PARTNO") "CC0402ZRY5V7BB104"))
      (libsource (lib "eagle-import") (part "CAP0402"))
    )
    (comp (ref "C102")
      (value "8p")
      (footprint "eagle-import:0402-CAP")
      (fields (field (name "PARTNO") "C1005C0G1H080C"))
      (libsource (lib "eagle-import") (part "CAP0402"))
    )
    (comp (ref "C103")
      (value "8p")
      (footprint "eagle-import:0402-CAP")
      (fields (field (name "PARTNO") "C1005C0G1H080C"))
      (libsource (lib "eagle-import") (part "CAP0402"))
    )
    (comp (ref "R101")
      (value "470R")
      (footprint "eagle-import:0402-RES")
      (fields (field (name "PARTNO") "RC0402FR-07470RL"))
      (libsource (lib "eagle-import") (part "RESISTOR0402-RES"))
    )
    (comp (ref "R102")
      (value "10K")
      (footprint "eagle-import:0402-RES")
      (fields (field (name "PARTNO") "RC0402FR-0710KL"))
      (libsource (lib "eagle-import") (part "RESISTOR0402-RES"))
    )
    (comp (ref "U101")
      (value "STM32F4X7VX")
      (footprint "eagle-import:TQFP100")
      (fields (field (name "PARTNO") "STM32F427VI"))
      (libsource (lib "eagle-import") (part "STM32F4X7VX"))
    )
    (comp (ref "U102")
      (value "FM25V01")
      (footprint "eagle-import:SO08")
      (fields (field (name "PARTNO") "FM25V01-G"))
      (libsource (lib "eagle-import") (part "FM25V01"))
    )
    (comp (ref "X101")
      (value "3.2x2.5 mm / 24 MHz / 15 ppm")
      (footprint "eagle-import:OSCILLATOR-3.2X2.5")
      (fields (field (name "PARTNO") "NX3225SA-24.000000MHZ"))
      (libsource (lib "eagle-import") (part "OSCILLATOR-3.2X2.5"))
    )
    (comp (ref "C1101")
      (value "22u/25V")
      (footprint "eagle-import:0805-CAP")
      (fields (field (name "PARTNO") "CL21A226MAQNNNE"))
      (libsource (lib "eagle-import") (part "CAP0805"))
    )
    (comp (ref "C1102")
      (value "22u/25V")
      (footprint "eagle-import:0805-CAP")
      (fields (field (name "PARTNO") "CL21A226MAQNNNE"))
      (libsource (lib "eagle-import") (part "CAP0805"))
    )
    (comp (ref "C1103")
      (value "22u/25V")
      (footprint "eagle-import:0805-CAP")
      (fields (field (name "PARTNO") "CL21A226MAQNNNE"))
      (libsource (lib "eagle-import") (part "CAP0805"))
    )
    (comp (ref "C1104")
      (value "100u")
      (footprint "eagle-import:1206-CAP")
      (fields (field (name "PARTNO") "C3216X5R1A107M160AC"))
      (libsource (lib "eagle-import") (part "CAP1206"))
    )
    (comp (ref "C1105")
      (value "0u1")
      (footprint "eagle-import:0402-CAP")
      (fields (field (name "PARTNO") "C1005X7R1E104K050BB"))
      (libsource (lib "eagle-import") (part "CAP0402"))
    )
    (comp (ref "C1106")
      (value "0u1")
      (footprint "eagle-import:0402-CAP")
      (fields (field (name "PARTNO") "C1005X7R1E104K050BB"))
      (libsource (lib "eagle-import") (part "CAP0402"))
    )
    (comp (ref "C1107")
      (value "0u1")
      (footprint "eagle-import:0402-CAP")
      (fields (field (name "PARTNO") "C1005X7R1E104K050BB"))
      (libsource (lib "eagle-import") (part "CAP0402"))
    )
    (comp (ref "C1108")
      (value "1000p/25V")
      (footprint "eagle-import:0402-CAP")
      (fields (field (name "PARTNO") "GRM1555C1E102JA01D"))
      (libsource (lib "eagle-import") (part "CAP0402"))
    )
    (comp (ref "C1109")
      (value "1000p/25V")
      (footprint "eagle-import:0402-CAP")
      (fields (field (name "PARTNO") "GRM1555C1E102JA01D"))
      (libsource (lib "eagle-import") (part "CAP0402"))
    )
    (comp (ref "C1110")
      (value "1000p/25V")
      (footprint "eagle-import:0402-CAP")
      (fields (field (name "PARTNO") "GRM1555C1E102JA01D"))
      (libsource (lib "eagle-import") (part "CAP0402"))
    )
    (comp (ref "J601")
      (value "DF13C-6P-1.25V")
      (footprint "eagle-import:DF13C-6P-1.25V")
      (fields (field (name "PARTNO") "DF13C-6P-1.25V(20)"))
      (libsource (lib "eagle-import") (part "DF13-6P-1.25V"))
    )
    (comp (ref "L1101")
      (value "KNH16C104DA5TS")
      (footprint "eagle-import:KYOCERA-KNH16-DA")
      (libsource (lib "eagle-import") (part "KNH16C104DA5TS"))
    )
    (comp (ref "L1102")
      (value "KNH16C104DA5TS")
      (footprint "eagle-import:KYOCERA-KNH16-DA")
      (libsource (lib "eagle-import") (part "KNH16C104DA5TS"))
    )
    (comp (ref "R1101")
      (value "10K/0.1%")
      (footprint "eagle-import:0402-RES")
      (fields (field (name "PARTNO") "ERA-2AEB103X"))
      (libsource (lib "eagle-import") (part "RESISTOR0402-RES"))
    )
    (comp (ref "R1102")
      (value "10K/0.1%")
      (footprint "eagle-import:0402-RES")
      (fields (field (name "PARTNO") "ERA-2AEB103X"))
      (libsource (lib "eagle-import") (part "RESISTOR0402-RES"))
    )
    (comp (ref "R1103")
      (value "1M")
      (footprint "eagle-import:0402-RES")
      (fields (field (name "PARTNO") "RC0402FR-071ML"))
      (libsource (lib "eagle-import") (part "RESISTOR0402-RES"))
    )
    (comp (ref "R1104")
      (value "1M")
      (footprint "eagle-import:0402-RES")
      (fields (field (name "PARTNO") "RC0402FR-071ML"))
      (libsource (lib "eagle-import") (part "RESISTOR0402-RES"))
    )
    (comp (ref "R1105")
      (value "453K")
      (footprint "eagle-import:0402-RES")
      (fields (field (name "PARTNO") "RMCF0402FT453K"))
      (libsource (lib "eagle-import") (part "RESISTOR0402-RES"))
    )
    (comp (ref "R1106")
      (value "56K")
      (footprint "eagle-import:0402-RES")
      (fields (field (name "PARTNO") "ERA-2AEB563X"))
      (libsource (lib "eagle-import") (part "RESISTOR0402-RES"))
    )
    (comp (ref "R1107")
      (value "105K")
      (footprint "eagle-import:0402-RES")
      (fields (field (name "PARTNO") "ERJ-2RKF1053X"))
      (libsource (lib "eagle-import") (part "RESISTOR0402-RES"))
    )
    (comp (ref "R1109")
      (value "453K")
      (footprint "eagle-import:0402-RES")
      (fields (field (name "PARTNO") "RMCF0402FT453K"))
      (libsource (lib "eagle-import") (part "RESISTOR0402-RES"))
    )
    (comp (ref "R1110")
      (value "56K")
      (footprint "eagle-import:0402-RES")
      (fields (field (name "PARTNO") "ERA-2AEB563X"))
      (libsource (lib "eagle-import") (part "RESISTOR0402-RES"))
    )
    (comp (ref "R1111")
      (value "105K")
      (footprint "eagle-import:0402-RES")
      (fields (field (name "PARTNO") "ERJ-2RKF1053X"))
      (libsource (lib "eagle-import") (part "RESISTOR0402-RES"))
    )
    (comp (ref "R1112")
      (value "453K")
      (footprint "eagle-import:0402-RES")
      (fields (field (name "PARTNO") "RMCF0402FT453K"))
      (libsource (lib "eagle-import") (part "RESISTOR0402-RES"))
    )
    (comp (ref "R1113")
      (value "56K")
      (footprint "eagle-import:0402-RES")
      (fields (field (name "PARTNO") "ERA-2AEB563X"))
      (libsource (lib "eagle-import") (part "RESISTOR0402-RES"))
    )
    (comp (ref "R1114")
      (value "105K")
      (footprint "eagle-import:0402-RES")
      (fields (field (name "PARTNO") "ERJ-2RKF1053X"))
      (libsource (lib "eagle-import") (part "RESISTOR0402-RES"))
    )
    (comp (ref "R1115")
      (value "0R")
      (footprint "eagle-import:0402-RES")
      (fields (field (name "PARTNO") "ERJ-2GE0R00X"))
      (libsource (lib "eagle-import") (part "RESISTOR0402-RES"))
    )
    (comp (ref "RN1101")
      (value "1M")
      (footprint "eagle-import:EXB28V")
      (fields (field (name "PARTNO") "EXB-28V105JX"))
      (libsource (lib "eagle-import") (part "4R-NEXB28V"))
    )
    (comp (ref "U1101")
      (value "LTC4417")
      (footprint "eagle-import:MO-220")
      (fields (field (name "PARTNO") "LTC4417IUF#PBF"))
      (libsource (lib "eagle-import") (part "LTC4117"))
    )
    (comp (ref "U1102")
      (value "NTHD4102PT1G")
      (footprint "eagle-import:1206-8")
      (fields (field (name "PARTNO") "NTHD4102PT1G"))
      (libsource (lib "eagle-import") (part "MOSFET-DUAL-PCHANNEL-CHIPFET"))
    )
    (comp (ref "U1103")
      (value "NTHD4102PT1G")
      (footprint "eagle-import:1206-8")
      (fields (field (name "PARTNO") "NTHD4102PT1G"))
      (libsource (lib "eagle-import") (part "MOSFET-DUAL-PCHANNEL-CHIPFET"))
    )
    (comp (ref "U1104")
      (value "NTHD4102PT1G")
      (footprint "eagle-import:1206-8")
      (fields (field (name "PARTNO") "NTHD4102PT1G"))
      (libsource (lib "eagle-import") (part "MOSFET-DUAL-PCHANNEL-CHIPFET"))
    )
    (comp (ref "C401")
      (value "0u1")
      (footprint "eagle-import:0402-CAP")
      (fields (field (name "PARTNO") "CC0402ZRY5V7BB104"))
      (libsource (lib "eagle-import") (part "CAP0402"))
    )
    (comp (ref "C402")
      (value "0u1")
      (footprint "eagle-import:0402-CAP")
      (fields (field (name "PARTNO") "CC0402ZRY5V7BB104"))
      (libsource (lib "eagle-import") (part "CAP0402"))
    )
    (comp (ref "D401")
      (value "PESD0402-140")
      (footprint "eagle-import:0402-TVS")
      (libsource (lib "eagle-import") (part "DIODE-TVS"))
    )
    (comp (ref "D402")
      (value "PESD0402-140")
      (footprint "eagle-import:0402-TVS")
      (libsource (lib "eagle-import") (part "DIODE-TVS"))
    )
    (comp (ref "D403")
      (value "PESD0402-140")
      (footprint "eagle-import:0402-TVS")
      (libsource (lib "eagle-import") (part "DIODE-TVS"))
    )
    (comp (ref "D404")
      (value "PESD0402-140")
      (footprint "eagle-import:0402-TVS")
      (libsource (lib "eagle-import") (part "DIODE-TVS"))
    )
    (comp (ref "J401")
      (value "DF13C-4P-1.25V")
      (footprint "eagle-import:DF13C-4P-1.25V")
      (fields (field (name "PARTNO") "DF13C-4P-1.25V(20)"))
      (libsource (lib "eagle-import") (part "DF13-4P-1.25V"))
    )
    (comp (ref "J402")
      (value "DF13C-3P-1.25V")
      (footprint "eagle-import:DF13C-3P-1.25V")
      (fields (field (name "PARTNO") "DF13C-3P-1.25V(20)"))
      (libsource (lib "eagle-import") (part "DF13-3P-1.25V"))
    )
    (comp (ref "J403")
      (value "DF13C-7P-1.25V")
      (footprint "eagle-import:DF13C-7P-1.25V")
      (fields (field (name "PARTNO") "DF13C-7P-1.25V(20)"))
      (libsource (lib "eagle-import") (part "DF13-7P-1.25V"))
    )
    (comp (ref "J404")
      (value "DF13C-5P-1.25V")
      (footprint "eagle-import:DF13C-5P-1.25V")
      (fields (field (name "PARTNO") "DF13C-5P-1.25V(20)"))
      (libsource (lib "eagle-import") (part "DF13-5P-1.25V"))
    )
    (comp (ref "J405")
      (value "DF13C-4P-1.25V")
      (footprint "eagle-import:DF13C-4P-1.25V")
      (fields (field (name "PARTNO") "DF13C-4P-1.25V(20)"))
      (libsource (lib "eagle-import") (part "DF13-4P-1.25V"))
    )
    (comp (ref "L401")
      (value "KNH16C104DA5TS")
      (footprint "eagle-import:KYOCERA-KNH16-DA")
      (libsource (lib "eagle-import") (part "KNH16C104DA5TS"))
    )
    (comp (ref "L402")
      (value "KNH16C104DA5TS")
      (footprint "eagle-import:KYOCERA-KNH16-DA")
      (libsource (lib "eagle-import") (part "KNH16C104DA5TS"))
    )
    (comp (ref "L403")
      (value "KNH16C104DA5TS")
      (footprint "eagle-import:KYOCERA-KNH16-DA")
      (libsource (lib "eagle-import") (part "KNH16C104DA5TS"))
    )
    (comp (ref "L404")
      (value "KNH16C104DA5TS")
      (footprint "eagle-import:KYOCERA-KNH16-DA")
      (libsource (lib "eagle-import") (part "KNH16C104DA5TS"))
    )
    (comp (ref "R401")
      (value "1K5")
      (footprint "eagle-import:0402-RES")
      (fields (field (name "PARTNO") "RC0402FR-071K5L"))
      (libsource (lib "eagle-import") (part "RESISTOR0402-RES"))
    )
    (comp (ref "R402")
      (value "1K5")
      (footprint "eagle-import:0402-RES")
      (fields (field (name "PARTNO") "RC0402FR-071K5L"))
      (libsource (lib "eagle-import") (part "RESISTOR0402-RES"))
    )
    (comp (ref "R403")
      (value "10K/0.1%")
      (footprint "eagle-import:0402-RES")
      (fields (field (name "PARTNO") "ERA-2AEB103X"))
      (libsource (lib "eagle-import") (part "RESISTOR0402-RES"))
    )
    (comp (ref "R404")
      (value "120R")
      (footprint "eagle-import:0402-RES")
      (fields (field (name "PARTNO") "RC0402FR-07120RL"))
      (libsource (lib "eagle-import") (part "RESISTOR0402-RES"))
    )
    (comp (ref "R405")
      (value "120R")
      (footprint "eagle-import:0402-RES")
      (fields (field (name "PARTNO") "RC0402FR-07120RL"))
      (libsource (lib "eagle-import") (part "RESISTOR0402-RES"))
    )
    (comp (ref "R406")
      (value "10K/0.1%")
      (footprint "eagle-import:0402-RES")
      (fields (field (name "PARTNO") "ERA-2AEB103X"))
      (libsource (lib "eagle-import") (part "RESISTOR0402-RES"))
    )
    (comp (ref "R407")
      (value "10K/0.1%")
      (footprint "eagle-import:0402-RES")
      (fields (field (name "PARTNO") "ERA-2AEB103X"))
      (libsource (lib "eagle-import") (part "RESISTOR0402-RES"))
    )
    (comp (ref "R408")
      (value "10K/0.1%")
      (footprint "eagle-import:0402-RES")
      (fields (field (name "PARTNO") "ERA-2AEB103X"))
      (libsource (lib "eagle-import") (part "RESISTOR0402-RES"))
    )
    (comp (ref "R409")
      (value "120R")
      (footprint "eagle-import:0402-RES")
      (fields (field (name "PARTNO") "RC0402FR-07120RL"))
      (libsource (lib "eagle-import") (part "RESISTOR0402-RES"))
    )
    (comp (ref "U401")
      (value "MAX3051")
      (footprint "eagle-import:SOT23-8")
      (fields (field (name "PARTNO") "MAX3051EKA"))
      (libsource (lib "eagle-import") (part "MAX3051MAX3051EKA"))
    )
    (comp (ref "C1001")
      (value "10u/25V")
      (footprint "eagle-import:0805-CAP")
      (fields (field (name "PARTNO") "CL21A106KAYNNNE"))
      (libsource (lib "eagle-import") (part "CAP0805"))
    )
    (comp (ref "C1002")
      (value "10n")
      (footprint "eagle-import:0402-CAP")
      (fields (field (name "PARTNO") "CC0402KRX7R7BB103"))
      (libsource (lib "eagle-import") (part "CAP0402"))
    )
    (comp (ref "C1003")
      (value "1u")
      (footprint "eagle-import:0603-CAP")
      (fields (field (name "PARTNO") "CC0603ZRY5V7BB105"))
      (libsource (lib "eagle-import") (part "CAP0603"))
    )
    (comp (ref "C1004")
      (value "10u")
      (footprint "eagle-import:0603-CAP")
      (fields (field (name "PARTNO") "C1608X5R1A106K080AC"))
      (libsource (lib "eagle-import") (part "CAP0603"))
    )
    (comp (ref "C1005")
      (value "0u1")
      (footprint "eagle-import:0402-CAP")
      (fields (field (name "PARTNO") "CC0402ZRY5V7BB104"))
      (libsource (lib "eagle-import") (part "CAP0402"))
    )
    (comp (ref "C1008")
      (value "2u2")
      (footprint "eagle-import:0402-CAP")
      (fields (field (name "PARTNO") "C1005X6S1C225K050BC"))
      (libsource (lib "eagle-import") (part "CAP0402"))
    )
    (comp (ref "D1001")
      (value "PMEG2005CT")
      (footprint "eagle-import:SOT23-3")
      (libsource (lib "eagle-import") (part "PMEG2005CT"))
    )
    (comp (ref "F1001")
      (value "0ZCA0035FF2G")
      (footprint "eagle-import:PTC-1206")
      (libsource (lib "eagle-import") (part "PTCSMD"))
    )
    (comp (ref "R1001")
      (value "100K")
      (footprint "eagle-import:0402-RES")
      (fields (field (name "PARTNO") "RC0402FR-07100KL"))
      (libsource (lib "eagle-import") (part "RESISTOR0402-RES"))
    )
    (comp (ref "R1002")
      (value "10K")
      (footprint "eagle-import:0402-RES")
      (fields (field (name "PARTNO") "RC0402FR-0710KL"))
      (libsource (lib "eagle-import") (part "RESISTOR0402-RES"))
    )
    (comp (ref "U1001")
      (value "BQ24313")
      (footprint "eagle-import:QFN8-DSG")
      (fields (field (name "PARTNO") "BQ24313DSGT"))
      (libsource (lib "eagle-import") (part "BQ24313"))
    )
    (comp (ref "U1002")
      (value "MIC5332")
      (footprint "eagle-import:MLF-8-EPAD")
      (fields (field (name "PARTNO") "MIC5332-SSYMT"))
      (libsource (lib "eagle-import") (part "MIC5332"))
    )
    (comp (ref "C201")
      (value "0u1")
      (footprint "eagle-import:0402-CAP")
      (fields (field (name "PARTNO") "CC0402ZRY5V7BB104"))
      (libsource (lib "eagle-import") (part "CAP0402"))
    )
    (comp (ref "C202")
      (value "0u1")
      (footprint "eagle-import:0402-CAP")
      (fields (field (name "PARTNO") "CC0402ZRY5V7BB104"))
      (libsource (lib "eagle-import") (part "CAP0402"))
    )
    (comp (ref "D201")
      (value "PESD0402-140")
      (footprint "eagle-import:0402-TVS")
      (libsource (lib "eagle-import") (part "DIODE-TVS"))
    )
    (comp (ref "D202")
      (value "PESD0402-140")
      (footprint "eagle-import:0402-TVS")
      (libsource (lib "eagle-import") (part "DIODE-TVS"))
    )
    (comp (ref "D203")
      (value "PESD0402-140")
      (footprint "eagle-import:0402-TVS")
      (libsource (lib "eagle-import") (part "DIODE-TVS"))
    )
    (comp (ref "J201")
      (value "DF13C-6P-1.25V")
      (footprint "eagle-import:DF13C-6P-1.25V")
      (fields (field (name "PARTNO") "DF13C-6P-1.25V(20)"))
      (libsource (lib "eagle-import") (part "DF13-6P-1.25V"))
    )
    (comp (ref "J202")
      (value "DF13C-6P-1.25V")
      (footprint "eagle-import:DF13C-6P-1.25V")
      (fields (field (name "PARTNO") "DF13C-6P-1.25V(20)"))
      (libsource (lib "eagle-import") (part "DF13-6P-1.25V"))
    )
    (comp (ref "J203")
      (value "DF13C-6P-1.25V")
      (footprint "eagle-import:DF13C-6P-1.25V")
      (fields (field (name "PARTNO") "DF13C-6P-1.25V(20)"))
      (libsource (lib "eagle-import") (part "DF13-6P-1.25V"))
    )
    (comp (ref "J204")
      (value "DF13C-6P-1.25V")
      (footprint "eagle-import:DF13C-6P-1.25V")
      (fields (field (name "PARTNO") "DF13C-6P-1.25V(20)"))
      (libsource (lib "eagle-import") (part "DF13-6P-1.25V"))
    )
    (comp (ref "L201")
      (value "KNH16C104DA5TS")
      (footprint "eagle-import:KYOCERA-KNH16-DA")
      (libsource (lib "eagle-import") (part "KNH16C104DA5TS"))
    )
    (comp (ref "L202")
      (value "KNH16C104DA5TS")
      (footprint "eagle-import:KYOCERA-KNH16-DA")
      (libsource (lib "eagle-import") (part "KNH16C104DA5TS"))
    )
    (comp (ref "L203")
      (value "KNH16C104DA5TS")
      (footprint "eagle-import:KYOCERA-KNH16-DA")
      (libsource (lib "eagle-import") (part "KNH16C104DA5TS"))
    )
    (comp (ref "R201")
      (value "120R")
      (footprint "eagle-import:0402-RES")
      (fields (field (name "PARTNO") "RC0402FR-07120RL"))
      (libsource (lib "eagle-import") (part "RESISTOR0402-RES"))
    )
    (comp (ref "R202")
      (value "120R")
      (footprint "eagle-import:0402-RES")
      (fields (field (name "PARTNO") "RC0402FR-07120RL"))
      (libsource (lib "eagle-import") (part "RESISTOR0402-RES"))
    )
    (comp (ref "R203")
      (value "120R")
      (footprint "eagle-import:0402-RES")
      (fields (field (name "PARTNO") "RC0402FR-07120RL"))
      (libsource (lib "eagle-import") (part "RESISTOR0402-RES"))
    )
    (comp (ref "R204")
      (value "120R")
      (footprint "eagle-import:0402-RES")
      (fields (field (name "PARTNO") "RC0402FR-07120RL"))
      (libsource (lib "eagle-import") (part "RESISTOR0402-RES"))
    )
    (comp (ref "R205")
      (value "120R")
      (footprint "eagle-import:0402-RES")
      (fields (field (name "PARTNO") "RC0402FR-07120RL"))
      (libsource (lib "eagle-import") (part "RESISTOR0402-RES"))
    )
    (comp (ref "R206")
      (value "120R")
      (footprint "eagle-import:0402-RES")
      (fields (field (name "PARTNO") "RC0402FR-07120RL"))
      (libsource (lib "eagle-import") (part "RESISTOR0402-RES"))
    )
    (comp (ref "R207")
      (value "120R")
      (footprint "eagle-import:0402-RES")
      (fields (field (name "PARTNO") "RC0402FR-07120RL"))
      (libsource (lib "eagle-import") (part "RESISTOR0402-RES"))
    )
    (comp (ref "R208")
      (value "120R")
      (footprint "eagle-import:0402-RES")
      (fields (field (name "PARTNO") "RC0402FR-07120RL"))
      (libsource (lib "eagle-import") (part "RESISTOR0402-RES"))
    )
    (comp (ref "R209")
      (value "120R")
      (footprint "eagle-import:0402-RES")
      (fields (field (name "PARTNO") "RC0402FR-07120RL"))
      (libsource (lib "eagle-import") (part "RESISTOR0402-RES"))
    )
    (comp (ref "R210")
      (value "120R")
      (footprint "eagle-import:0402-RES")
      (fields (field (name "PARTNO") "RC0402FR-07120RL"))
      (libsource (lib "eagle-import") (part "RESISTOR0402-RES"))
    )
    (comp (ref "R211")
      (value "120R")
      (footprint "eagle-import:0402-RES")
      (fields (field (name "PARTNO") "RC0402FR-07120RL"))
      (libsource (lib "eagle-import") (part "RESISTOR0402-RES"))
    )
    (comp (ref "R212")
      (value "120R")
      (footprint "eagle-import:0402-RES")
      (fields (field (name "PARTNO") "RC0402FR-07120RL"))
      (libsource (lib "eagle-import") (part "RESISTOR0402-RES"))
    )
    (comp (ref "R213")
      (value "120R")
      (footprint "eagle-import:0402-RES")
      (fields (field (name "PARTNO") "RC0402FR-07120RL"))
      (libsource (lib "eagle-import") (part "RESISTOR0402-RES"))
    )
    (comp (ref "R214")
      (value "120R")
      (footprint "eagle-import:0402-RES")
      (fields (field (name "PARTNO") "RC0402FR-07120RL"))
      (libsource (lib "eagle-import") (part "RESISTOR0402-RES"))
    )
    (comp (ref "R215")
      (value "120R")
      (footprint "eagle-import:0402-RES")
      (fields (field (name "PARTNO") "RC0402FR-07120RL"))
      (libsource (lib "eagle-import") (part "RESISTOR0402-RES"))
    )
    (comp (ref "R216")
      (value "120R")
      (footprint "eagle-import:0402-RES")
      (fields (field (name "PARTNO") "RC0402FR-07120RL"))
      (libsource (lib "eagle-import") (part "RESISTOR0402-RES"))
    )
    (comp (ref "U201")
      (value "TXS0108QFN20")
      (footprint "eagle-import:QFN20-RGY")
      (fields (field (name "PARTNO") "TXS0108ERGYR"))
      (libsource (lib "eagle-import") (part "TXS0108QFN20"))
    )
    (comp (ref "U202")
      (value "TXS0108QFN20")
      (footprint "eagle-import:QFN20-RGY")
      (fields (field (name "PARTNO") "TXS0108ERGYR"))
      (libsource (lib "eagle-import") (part "TXS0108QFN20"))
    )
    (comp (ref "J301")
      (value "47346-0001")
      (footprint "eagle-import:MOLEX-47346-0001")
      (libsource (lib "eagle-import") (part "MOLEX-47346-0001"))
    )
    (comp (ref "J302")
      (value "DF13C-4P-1.25V")
      (footprint "eagle-import:DF13C-4P-1.25V")
      (fields (field (name "PARTNO") "DF13C-4P-1.25V(20)"))
      (libsource (lib "eagle-import") (part "DF13-4P-1.25V"))
    )
    (comp (ref "JX301")
      (value "ARM_MINI_JTAG-SMT")
      (footprint "eagle-import:FTSH-105-01-XXX-DV-K")
      (fields (field (name "BOM") "EXCLUDE") (field (name "PARTNO") "M50-3900542"))
      (libsource (lib "eagle-import") (part "ARM_MINI_JTAG-SMT"))
    )
    (comp (ref "R301")
      (value "100K")
      (footprint "eagle-import:0402-RES")
      (fields (field (name "PARTNO") "RC0402FR-07100KL"))
      (libsource (lib "eagle-import") (part "RESISTOR0402-RES"))
    )
    (comp (ref "R302")
      (value "100K")
      (footprint "eagle-import:0402-RES")
      (fields (field (name "PARTNO") "RC0402FR-07100KL"))
      (libsource (lib "eagle-import") (part "RESISTOR0402-RES"))
    )
    (comp (ref "R303")
      (value "100K")
      (footprint "eagle-import:0402-RES")
      (fields (field (name "PARTNO") "RC0402FR-07100KL"))
      (libsource (lib "eagle-import") (part "RESISTOR0402-RES"))
    )
    (comp (ref "R304")
      (value "100K")
      (footprint "eagle-import:0402-RES")
      (fields (field (name "PARTNO") "RC0402FR-07100KL"))
      (libsource (lib "eagle-import") (part "RESISTOR0402-RES"))
    )
    (comp (ref "R305")
      (value "100K")
      (footprint "eagle-import:0402-RES")
      (fields (field (name "PARTNO") "RC0402FR-07100KL"))
      (libsource (lib "eagle-import") (part "RESISTOR0402-RES"))
    )
    (comp (ref "R306")
      (value "1K5")
      (footprint "eagle-import:0402-RES")
      (fields (field (name "PARTNO") "RC0402FR-071K5L"))
      (libsource (lib "eagle-import") (part "RESISTOR0402-RES"))
    )
    (comp (ref "R307")
      (value "1K5")
      (footprint "eagle-import:0402-RES")
      (fields (field (name "PARTNO") "RC0402FR-071K5L"))
      (libsource (lib "eagle-import") (part "RESISTOR0402-RES"))
    )
    (comp (ref "U301")
      (value "2908-05WB-MG")
      (footprint "eagle-import:MICROSD")
      (libsource (lib "eagle-import") (part "MICROSDSDI"))
    )
    (comp (ref "U302")
      (value "NUF2042XV6")
      (footprint "eagle-import:SOT563-6")
      (fields (field (name "PARTNO") "NUF2042XV6T1G"))
      (libsource (lib "eagle-import") (part "NUF2042XV6"))
    )
    (comp (ref "B601")
      (value "MS621FE")
      (footprint "eagle-import:MS621FE")
      (fields (field (name "PARTNO") "MS621FE-FL11E"))
      (libsource (lib "eagle-import") (part "MS621FE"))
    )
    (comp (ref "C601")
      (value "10u/25V")
      (footprint "eagle-import:0805-CAP")
      (fields (field (name "PARTNO") "CL21A106KAYNNNE"))
      (libsource (lib "eagle-import") (part "CAP0805"))
    )
    (comp (ref "C602")
      (value "10n")
      (footprint "eagle-import:0402-CAP")
      (fields (field (name "PARTNO") "CC0402KRX7R7BB103"))
      (libsource (lib "eagle-import") (part "CAP0402"))
    )
    (comp (ref "C603")
      (value "1u")
      (footprint "eagle-import:0603-CAP")
      (fields (field (name "PARTNO") "CC0603ZRY5V7BB105"))
      (libsource (lib "eagle-import") (part "CAP0603"))
    )
    (comp (ref "C604")
      (value "22u/25V")
      (footprint "eagle-import:0805-CAP")
      (fields (field (name "PARTNO") "CL21A226MAQNNNE"))
      (libsource (lib "eagle-import") (part "CAP0805"))
    )
    (comp (ref "C605")
      (value "22u/25V")
      (footprint "eagle-import:0805-CAP")
      (fields (field (name "PARTNO") "CL21A226MAQNNNE"))
      (libsource (lib "eagle-import") (part "CAP0805"))
    )
    (comp (ref "C606")
      (value "0u1")
      (footprint "eagle-import:0402-CAP")
      (fields (field (name "PARTNO") "CC0402ZRY5V7BB104"))
      (libsource (lib "eagle-import") (part "CAP0402"))
    )
    (comp (ref "C607")
      (value "0u1")
      (footprint "eagle-import:0402-CAP")
      (fields (field (name "PARTNO") "CC0402ZRY5V7BB104"))
      (libsource (lib "eagle-import") (part "CAP0402"))
    )
    (comp (ref "C608")
      (value "0u1")
      (footprint "eagle-import:0402-CAP")
      (fields (field (name "PARTNO") "CC0402ZRY5V7BB104"))
      (libsource (lib "eagle-import") (part "CAP0402"))
    )
    (comp (ref "C609")
      (value "0u1")
      (footprint "eagle-import:0402-CAP")
      (fields (field (name "PARTNO") "CC0402ZRY5V7BB104"))
      (libsource (lib "eagle-import") (part "CAP0402"))
    )
    (comp (ref "C610")
      (value "0u1")
      (footprint "eagle-import:0402-CAP")
      (fields (field (name "PARTNO") "CC0402ZRY5V7BB104"))
      (libsource (lib "eagle-import") (part "CAP0402"))
    )
    (comp (ref "C611")
      (value "2u2")
      (footprint "eagle-import:0603-CAP")
      (fields (field (name "PARTNO") "C1608X6S1C225K080AC"))
      (libsource (lib "eagle-import") (part "CAP0603"))
    )
    (comp (ref "C612")
      (value "0u1")
      (footprint "eagle-import:0402-CAP")
      (fields (field (name "PARTNO") "CC0402ZRY5V7BB104"))
      (libsource (lib "eagle-import") (part "CAP0402"))
    )
    (comp (ref "C613")
      (value "2u2")
      (footprint "eagle-import:0603-CAP")
      (fields (field (name "PARTNO") "C1608X6S1C225K080AC"))
      (libsource (lib "eagle-import") (part "CAP0603"))
    )
    (comp (ref "C614")
      (value "100u")
      (footprint "eagle-import:1206-CAP")
      (fields (field (name "PARTNO") "C3216X5R1A107M160AC"))
      (libsource (lib "eagle-import") (part "CAP1206"))
    )
    (comp (ref "C615")
      (value "0u1")
      (footprint "eagle-import:0402-CAP")
      (fields (field (name "PARTNO") "CC0402ZRY5V7BB104"))
      (libsource (lib "eagle-import") (part "CAP0402"))
    )
    (comp (ref "C616")
      (value "0u1")
      (footprint "eagle-import:0402-CAP")
      (fields (field (name "PARTNO") "CC0402ZRY5V7BB104"))
      (libsource (lib "eagle-import") (part "CAP0402"))
    )
    (comp (ref "C617")
      (value "0u1")
      (footprint "eagle-import:0402-CAP")
      (fields (field (name "PARTNO") "CC0402ZRY5V7BB104"))
      (libsource (lib "eagle-import") (part "CAP0402"))
    )
    (comp (ref "C618")
      (value "100u")
      (footprint "eagle-import:1206-CAP")
      (fields (field (name "PARTNO") "C3216X5R1A107M160AC"))
      (libsource (lib "eagle-import") (part "CAP1206"))
    )
    (comp (ref "D602")
      (value "RB751V40T1G")
      (footprint "eagle-import:SOD323")
      (libsource (lib "eagle-import") (part "DIODE-SCHOTTKY_SOD323"))
    )
    (comp (ref "L603")
      (value "KNH16C104DA5TS")
      (footprint "eagle-import:KYOCERA-KNH16-DA")
      (libsource (lib "eagle-import") (part "KNH16C104DA5TS"))
    )
    (comp (ref "Q601")
      (value "MMBT3906LT1SMD")
      (footprint "eagle-import:SOT23-BEC")
      (fields (field (name "PARTNO") "MMBT 3906 LT1"))
      (libsource (lib "eagle-import") (part "MMBT3906SMDLT1"))
    )
    (comp (ref "R602")
      (value "1M")
      (footprint "eagle-import:0402-RES")
      (fields (field (name "PARTNO") "RC0402FR-071ML"))
      (libsource (lib "eagle-import") (part "RESISTOR0402-RES"))
    )
    (comp (ref "R603")
      (value "10K")
      (footprint "eagle-import:0402-RES")
      (fields (field (name "PARTNO") "RC0402FR-0710KL"))
      (libsource (lib "eagle-import") (part "RESISTOR0402-RES"))
    )
    (comp (ref "R604")
      (value "1M")
      (footprint "eagle-import:0402-RES")
      (fields (field (name "PARTNO") "RC0402FR-071ML"))
      (libsource (lib "eagle-import") (part "RESISTOR0402-RES"))
    )
    (comp (ref "R608")
      (value "1K")
      (footprint "eagle-import:0402-RES")
      (fields (field (name "PARTNO") "RC0402FR-071KL"))
      (libsource (lib "eagle-import") (part "RESISTOR0402-RES"))
    )
    (comp (ref "R609")
      (value "10K/0.1%")
      (footprint "eagle-import:0402-RES")
      (fields (field (name "PARTNO") "ERA-2AEB103X"))
      (libsource (lib "eagle-import") (part "RESISTOR0402-RES"))
    )
    (comp (ref "R610")
      (value "10K/0.1%")
      (footprint "eagle-import:0402-RES")
      (fields (field (name "PARTNO") "ERA-2AEB103X"))
      (libsource (lib "eagle-import") (part "RESISTOR0402-RES"))
    )
    (comp (ref "R611")
      (value "10K")
      (footprint "eagle-import:0402-RES")
      (fields (field (name "PARTNO") "RC0402FR-0710KL"))
      (libsource (lib "eagle-import") (part "RESISTOR0402-RES"))
    )
    (comp (ref "R615")
      (value "10K")
      (footprint "eagle-import:0402-RES")
      (fields (field (name "PARTNO") "RC0402FR-0710KL"))
      (libsource (lib "eagle-import") (part "RESISTOR0402-RES"))
    )
    (comp (ref "R616")
      (value "25K5")
      (footprint "eagle-import:0402-RES")
      (fields (field (name "PARTNO") "RMCF0402FT25K5"))
      (libsource (lib "eagle-import") (part "RESISTOR0402-RES"))
    )
    (comp (ref "R617")
      (value "16K5")
      (footprint "eagle-import:0402-RES")
      (fields (field (name "PARTNO") "RMCF0402FT16K5"))
      (libsource (lib "eagle-import") (part "RESISTOR0402-RES"))
    )
    (comp (ref "R620")
      (value "1K8")
      (footprint "eagle-import:0402-RES")
      (fields (field (name "PARTNO") "RC1005F182CS"))
      (libsource (lib "eagle-import") (part "RESISTOR0402-RES"))
    )
    (comp (ref "R621")
      (value "10R")
      (footprint "eagle-import:0603-RES")
      (fields (field (name "PARTNO") "RC1608J100CS"))
      (libsource (lib "eagle-import") (part "RESISTOR0603-RES"))
    )
    (comp (ref "R635")
      (value "DNP/10K")
      (footprint "eagle-import:0402-RES")
      (fields (field (name "PARTNO") "RC0402FR-0710KL"))
      (libsource (lib "eagle-import") (part "RESISTOR0402-RES"))
    )
    (comp (ref "S601")
      (value "RESET")
      (footprint "eagle-import:EVQP7J01K")
      (fields (field (name "PARTNO") "EVQ-P7J01P"))
      (libsource (lib "eagle-import") (part "SWITCH-MOMENTARY-2"))
    )
    (comp (ref "U601")
      (value "BQ24315")
      (footprint "eagle-import:QFN8-DSG")
      (fields (field (name "PARTNO") "BQ24315DSGR"))
      (libsource (lib "eagle-import") (part "BQ24315"))
    )
    (comp (ref "U602")
      (value "BQ24315")
      (footprint "eagle-import:QFN8-DSG")
      (fields (field (name "PARTNO") "BQ24315DSGR"))
      (libsource (lib "eagle-import") (part "BQ24315"))
    )
    (comp (ref "U603")
      (value "MIC5332")
      (footprint "eagle-import:MLF-8-EPAD")
      (fields (field (name "PARTNO") "MIC5332-SSYMT"))
      (libsource (lib "eagle-import") (part "MIC5332"))
    )
    (comp (ref "C901")
      (value "0u1")
      (footprint "eagle-import:0402-CAP")
      (fields (field (name "PARTNO") "CC0402ZRY5V7BB104"))
      (libsource (lib "eagle-import") (part "CAP0402"))
    )
    (comp (ref "C902")
      (value "0u1")
      (footprint "eagle-import:0402-CAP")
      (fields (field (name "PARTNO") "CC0402ZRY5V7BB104"))
      (libsource (lib "eagle-import") (part "CAP0402"))
    )
    (comp (ref "C903")
      (value "0u1")
      (footprint "eagle-import:0402-CAP")
      (fields (field (name "PARTNO") "CC0402ZRY5V7BB104"))
      (libsource (lib "eagle-import") (part "CAP0402"))
    )
    (comp (ref "D901")
      (value "PESD0402-140")
      (footprint "eagle-import:0402-TVS")
      (libsource (lib "eagle-import") (part "DIODE-TVS"))
    )
    (comp (ref "D902")
      (value "PESD0402-140")
      (footprint "eagle-import:0402-TVS")
      (libsource (lib "eagle-import") (part "DIODE-TVS"))
    )
    (comp (ref "D903")
      (value "PESD0402-140")
      (footprint "eagle-import:0402-TVS")
      (libsource (lib "eagle-import") (part "DIODE-TVS"))
    )
    (comp (ref "D904")
      (value "MSS1P4-M3")
      (footprint "eagle-import:MICROSMP")
      (fields (field (name "PARTNO") "MSS1P4-M3/89A"))
      (libsource (lib "eagle-import") (part "DIODE-SCHOTTKY_MSMP"))
    )
    (comp (ref "J901")
      (value "HEADER-3X163X16RA")
      (footprint "eagle-import:3X16RA")
      (fields (field (name "BOM") "EXCLUDE"))
      (libsource (lib "eagle-import") (part "HEADER-3X163X16RA"))
    )
    (comp (ref "L901")
      (value "KNH16C104DA5TS")
      (footprint "eagle-import:KYOCERA-KNH16-DA")
      (libsource (lib "eagle-import") (part "KNH16C104DA5TS"))
    )
    (comp (ref "R901")
      (value "10K")
      (footprint "eagle-import:0402-RES")
      (fields (field (name "PARTNO") "RC0402FR-0710KL"))
      (libsource (lib "eagle-import") (part "RESISTOR0402-RES"))
    )
    (comp (ref "R902")
      (value "220R")
      (footprint "eagle-import:0402-RES")
      (fields (field (name "PARTNO") "RC0402FR-07220RL"))
      (libsource (lib "eagle-import") (part "RESISTOR0402-RES"))
    )
    (comp (ref "R903")
      (value "220R")
      (footprint "eagle-import:0402-RES")
      (fields (field (name "PARTNO") "RC0402FR-07220RL"))
      (libsource (lib "eagle-import") (part "RESISTOR0402-RES"))
    )
    (comp (ref "R904")
      (value "220R")
      (footprint "eagle-import:0402-RES")
      (fields (field (name "PARTNO") "RC0402FR-07220RL"))
      (libsource (lib "eagle-import") (part "RESISTOR0402-RES"))
    )
    (comp (ref "R905")
      (value "220R")
      (footprint "eagle-import:0402-RES")
      (fields (field (name "PARTNO") "RC0402FR-07220RL"))
      (libsource (lib "eagle-import") (part "RESISTOR0402-RES"))
    )
    (comp (ref "R906")
      (value "220R")
      (footprint "eagle-import:0402-RES")
      (fields (field (name "PARTNO") "RC0402FR-07220RL"))
      (libsource (lib "eagle-import") (part "RESISTOR0402-RES"))
    )
    (comp (ref "R907")
      (value "220R")
      (footprint "eagle-import:0402-RES")
      (fields (field (name "PARTNO") "RC0402FR-07220RL"))
      (libsource (lib "eagle-import") (part "RESISTOR0402-RES"))
    )
    (comp (ref "R908")
      (value "220R")
      (footprint "eagle-import:0402-RES")
      (fields (field (name "PARTNO") "RC0402FR-07220RL"))
      (libsource (lib "eagle-import") (part "RESISTOR0402-RES"))
    )
    (comp (ref "R909")
      (value "220R")
      (footprint "eagle-import:0402-RES")
      (fields (field (name "PARTNO") "RC0402FR-07220RL"))
      (libsource (lib "eagle-import") (part "RESISTOR0402-RES"))
    )
    (comp (ref "R910")
      (value "220R")
      (footprint "eagle-import:0402-RES")
      (fields (field (name "PARTNO") "RC0402FR-07220RL"))
      (libsource (lib "eagle-import") (part "RESISTOR0402-RES"))
    )
    (comp (ref "R911")
      (value "220R")
      (footprint "eagle-import:0402-RES")
      (fields (field (name "PARTNO") "RC0402FR-07220RL"))
      (libsource (lib "eagle-import") (part "RESISTOR0402-RES"))
    )
    (comp (ref "R912")
      (value "220R")
      (footprint "eagle-import:0402-RES")
      (fields (field (name "PARTNO") "RC0402FR-07220RL"))
      (libsource (lib "eagle-import") (part "RESISTOR0402-RES"))
    )
    (comp (ref "R913")
      (value "220R")
      (footprint "eagle-import:0402-RES")
      (fields (field (name "PARTNO") "RC0402FR-07220RL"))
      (libsource (lib "eagle-import") (part "RESISTOR0402-RES"))
    )
    (comp (ref "R914")
      (value "220R")
      (footprint "eagle-import:0402-RES")
      (fields (field (name "PARTNO") "RC0402FR-07220RL"))
      (libsource (lib "eagle-import") (part "RESISTOR0402-RES"))
    )
    (comp (ref "R915")
      (value "220R")
      (footprint "eagle-import:0402-RES")
      (fields (field (name "PARTNO") "RC0402FR-07220RL"))
      (libsource (lib "eagle-import") (part "RESISTOR0402-RES"))
    )
    (comp (ref "R916")
      (value "220R")
      (footprint "eagle-import:0402-RES")
      (fields (field (name "PARTNO") "RC0402FR-07220RL"))
      (libsource (lib "eagle-import") (part "RESISTOR0402-RES"))
    )
    (comp (ref "R917")
      (value "220R")
      (footprint "eagle-import:0402-RES")
      (fields (field (name "PARTNO") "RC0402FR-07220RL"))
      (libsource (lib "eagle-import") (part "RESISTOR0402-RES"))
    )
    (comp (ref "R918")
      (value "10K/0.1%")
      (footprint "eagle-import:0402-RES")
      (fields (field (name "PARTNO") "ERA-2AEB103X"))
      (libsource (lib "eagle-import") (part "RESISTOR0402-RES"))
    )
    (comp (ref "R919")
      (value "10K/0.1%")
      (footprint "eagle-import:0402-RES")
      (fields (field (name "PARTNO") "ERA-2AEB103X"))
      (libsource (lib "eagle-import") (part "RESISTOR0402-RES"))
    )
    (comp (ref "R922")
      (value "10K/0.1%")
      (footprint "eagle-import:0402-RES")
      (fields (field (name "PARTNO") "ERA-2AEB103X"))
      (libsource (lib "eagle-import") (part "RESISTOR0402-RES"))
    )
    (comp (ref "U901")
      (value "TXS0108QFN20")
      (footprint "eagle-import:QFN20-RGY")
      (fields (field (name "PARTNO") "TXS0108ERGYR"))
      (libsource (lib "eagle-import") (part "TXS0108QFN20"))
    )
    (comp (ref "U902")
      (value "TXS0108QFN20")
      (footprint "eagle-import:QFN20-RGY")
      (fields (field (name "PARTNO") "TXS0108ERGYR"))
      (libsource (lib "eagle-import") (part "TXS0108QFN20"))
    )
    (comp (ref "U903")
      (value "74LVC2G240")
      (footprint "eagle-import:TSSOP8_SOT505-2")
      (fields (field (name "PARTNO") "74LVC2G240DP,125"))
      (libsource (lib "eagle-import") (part "74LVC2G240-TSSOP-8"))
    )
    (comp (ref "C801")
      (value "0u1")
      (footprint "eagle-import:0402-CAP")
      (fields (field (name "PARTNO") "CC0402ZRY5V7BB104"))
      (libsource (lib "eagle-import") (part "CAP0402"))
    )
    (comp (ref "C802")
      (value "0u1")
      (footprint "eagle-import:0402-CAP")
      (fields (field (name "PARTNO") "CC0402ZRY5V7BB104"))
      (libsource (lib "eagle-import") (part "CAP0402"))
    )
    (comp (ref "C803")
      (value "0u1")
      (footprint "eagle-import:0402-CAP")
      (fields (field (name "PARTNO") "CC0402ZRY5V7BB104"))
      (libsource (lib "eagle-import") (part "CAP0402"))
    )
    (comp (ref "C804")
      (value "0u1")
      (footprint "eagle-import:0402-CAP")
      (fields (field (name "PARTNO") "CC0402ZRY5V7BB104"))
      (libsource (lib "eagle-import") (part "CAP0402"))
    )
    (comp (ref "C805")
      (value "8p")
      (footprint "eagle-import:0402-CAP")
      (fields (field (name "PARTNO") "C1005C0G1H080C"))
      (libsource (lib "eagle-import") (part "CAP0402"))
    )
    (comp (ref "C806")
      (value "8p")
      (footprint "eagle-import:0402-CAP")
      (fields (field (name "PARTNO") "C1005C0G1H080C"))
      (libsource (lib "eagle-import") (part "CAP0402"))
    )
    (comp (ref "D801")
      (value "PESD0402-140")
      (footprint "eagle-import:0402-TVS")
      (libsource (lib "eagle-import") (part "DIODE-TVS"))
    )
    (comp (ref "J801")
      (value "JST-ZH-3")
      (footprint "eagle-import:JST-ZH-SMT-VERTICAL")
      (fields (field (name "PARTNO") "B3B-ZR-SM4-TF (LF)(SN)(P)"))
      (libsource (lib "eagle-import") (part "JST-ZH-3"))
    )
    (comp (ref "JX801")
      (value "HEADER-3X1BOARDEDGE-SHORT")
      (footprint "eagle-import:HEADER_3X01_SMD_H_BOARD_EDGE_SHORT")
      (libsource (lib "eagle-import") (part "HEADER-3X1BOARDEDGE-SHORT"))
    )
    (comp (ref "JX802")
      (value "ARM_MINI_JTAG-SMT")
      (footprint "eagle-import:FTSH-105-01-XXX-DV-K")
      (fields (field (name "BOM") "EXCLUDE") (field (name "PARTNO") "M50-3900542"))
      (libsource (lib "eagle-import") (part "ARM_MINI_JTAG-SMT"))
    )
    (comp (ref "R801")
      (value "10K")
      (footprint "eagle-import:0402-RES")
      (fields (field (name "PARTNO") "RC0402FR-0710KL"))
      (libsource (lib "eagle-import") (part "RESISTOR0402-RES"))
    )
    (comp (ref "R802")
      (value "10K")
      (footprint "eagle-import:0402-RES")
      (fields (field (name "PARTNO") "RC0402FR-0710KL"))
      (libsource (lib "eagle-import") (part "RESISTOR0402-RES"))
    )
    (comp (ref "R803")
      (value "220R")
      (footprint "eagle-import:0402-RES")
      (fields (field (name "PARTNO") "RC0402FR-07220RL"))
      (libsource (lib "eagle-import") (part "RESISTOR0402-RES"))
    )
    (comp (ref "R804")
      (value "220R")
      (footprint "eagle-import:0402-RES")
      (fields (field (name "PARTNO") "RC0402FR-07220RL"))
      (libsource (lib "eagle-import") (part "RESISTOR0402-RES"))
    )
    (comp (ref "S801")
      (value "RESET")
      (footprint "eagle-import:EVQP7J01K")
      (fields (field (name "PARTNO") "EVQ-P7J01P"))
      (libsource (lib "eagle-import") (part "SWITCH-MOMENTARY-2"))
    )
    (comp (ref "U801")
      (value "STM32F10XCXT6")
      (footprint "eagle-import:TQFP48")
      (fields (field (name "PARTNO") "STM32F100C8T6B"))
      (libsource (lib "eagle-import") (part "STM32F10XCXT6"))
    )
    (comp (ref "X801")
      (value "3.2x2.5 mm / 24 MHz / 15 ppm")
      (footprint "eagle-import:OSCILLATOR-3.2X2.5")
      (fields (field (name "PARTNO") "NX3225SA-24.000000MHZ"))
      (libsource (lib "eagle-import") (part "OSCILLATOR-3.2X2.5"))
    )
    (comp (ref "C701")
      (value "0u1")
      (footprint "eagle-import:0402-CAP")
      (fields (field (name "PARTNO") "CC0402ZRY5V7BB104"))
      (libsource (lib "eagle-import") (part "CAP0402"))
    )
    (comp (ref "C702")
      (value "1u")
      (footprint "eagle-import:0603-CAP")
      (fields (field (name "PARTNO") "CC0603ZRY5V7BB105"))
      (libsource (lib "eagle-import") (part "CAP0603"))
    )
    (comp (ref "C703")
      (value "5n6")
      (footprint "eagle-import:0402-CAP")
      (fields (field (name "PARTNO") "C0402C562K5RACTU"))
      (libsource (lib "eagle-import") (part "CAP0402"))
    )
    (comp (ref "C704")
      (value "0u47")
      (footprint "eagle-import:0402-CAP")
      (fields (field (name "PARTNO") "C1005X5R1C474K050BC"))
      (libsource (lib "eagle-import") (part "CAP0402"))
    )
    (comp (ref "D701")
      (value "PESD0402-140")
      (footprint "eagle-import:0402-TVS")
      (libsource (lib "eagle-import") (part "DIODE-TVS"))
    )
    (comp (ref "J701")
      (value "DF13C-2P-1.25V")
      (footprint "eagle-import:DF13C-2P-1.25V")
      (fields (field (name "PARTNO") "DF13C-2P-1.25V(20)"))
      (libsource (lib "eagle-import") (part "DF13-2P-1.25V"))
    )
    (comp (ref "J702")
      (value "DF13C-3P-1.25V")
      (footprint "eagle-import:DF13C-3P-1.25V")
      (fields (field (name "PARTNO") "DF13C-3P-1.25V(20)"))
      (libsource (lib "eagle-import") (part "DF13-3P-1.25V"))
    )
    (comp (ref "L701")
      (value "47uH")
      (footprint "eagle-import:0805-IND")
      (fields (field (name "PARTNO") "MLZ2012M470W"))
      (libsource (lib "eagle-import") (part "INDUCTOR0805"))
    )
    (comp (ref "LED701")
      (value "AMBER")
      (footprint "eagle-import:0603-LED")
      (fields (field (name "PARTNO") "APTD1608SECK"))
      (libsource (lib "eagle-import") (part "LED0603"))
    )
    (comp (ref "LED702")
      (value "GREEN")
      (footprint "eagle-import:0603-LED")
      (fields (field (name "PARTNO") "APTD1608CGCK"))
      (libsource (lib "eagle-import") (part "LED0603"))
    )
    (comp (ref "LED703")
      (value "AMBER")
      (footprint "eagle-import:0603-LED")
      (fields (field (name "PARTNO") "APTD1608SECK"))
      (libsource (lib "eagle-import") (part "LED0603"))
    )
    (comp (ref "LED704")
      (value "GREEN")
      (footprint "eagle-import:0603-LED")
      (fields (field (name "PARTNO") "APTD1608CGCK"))
      (libsource (lib "eagle-import") (part "LED0603"))
    )
    (comp (ref "LED705")
      (value "BLUE")
      (footprint "eagle-import:0603-LED")
      (fields (field (name "PARTNO") "APTD1608QBC/D"))
      (libsource (lib "eagle-import") (part "LED0603"))
    )
    (comp (ref "R701")
      (value "9K09")
      (footprint "eagle-import:0402-RES")
      (fields (field (name "PARTNO") "RMCF0402FT9K09"))
      (libsource (lib "eagle-import") (part "RESISTOR0402-RES"))
    )
    (comp (ref "R702")
      (value "10K")
      (footprint "eagle-import:0402-RES")
      (fields (field (name "PARTNO") "RC0402FR-0710KL"))
      (libsource (lib "eagle-import") (part "RESISTOR0402-RES"))
    )
    (comp (ref "R703")
      (value "100K")
      (footprint "eagle-import:0402-RES")
      (fields (field (name "PARTNO") "RC0402FR-07100KL"))
      (libsource (lib "eagle-import") (part "RESISTOR0402-RES"))
    )
    (comp (ref "R704")
      (value "10K")
      (footprint "eagle-import:0402-RES")
      (fields (field (name "PARTNO") "RC0402FR-0710KL"))
      (libsource (lib "eagle-import") (part "RESISTOR0402-RES"))
    )
    (comp (ref "R705")
      (value "453K")
      (footprint "eagle-import:0402-RES")
      (fields (field (name "PARTNO") "RMCF0402FT453K"))
      (libsource (lib "eagle-import") (part "RESISTOR0402-RES"))
    )
    (comp (ref "R706")
      (value "16K5")
      (footprint "eagle-import:0402-RES")
      (fields (field (name "PARTNO") "RMCF0402FT16K5"))
      (libsource (lib "eagle-import") (part "RESISTOR0402-RES"))
    )
    (comp (ref "R707")
      (value "220R")
      (footprint "eagle-import:0402-RES")
      (fields (field (name "PARTNO") "RC0402FR-07220RL"))
      (libsource (lib "eagle-import") (part "RESISTOR0402-RES"))
    )
    (comp (ref "R708")
      (value "220R")
      (footprint "eagle-import:0402-RES")
      (fields (field (name "PARTNO") "RC0402FR-07220RL"))
      (libsource (lib "eagle-import") (part "RESISTOR0402-RES"))
    )
    (comp (ref "R709")
      (value "220R")
      (footprint "eagle-import:0402-RES")
      (fields (field (name "PARTNO") "RC0402FR-07220RL"))
      (libsource (lib "eagle-import") (part "RESISTOR0402-RES"))
    )
    (comp (ref "R710")
      (value "68R")
      (footprint "eagle-import:0402-RES")
      (fields (field (name "PARTNO") "ERJ-2GEJ680X"))
      (libsource (lib "eagle-import") (part "RESISTOR0402-RES"))
    )
    (comp (ref "R711")
      (value "220R")
      (footprint "eagle-import:0402-RES")
      (fields (field (name "PARTNO") "RC0402FR-07220RL"))
      (libsource (lib "eagle-import") (part "RESISTOR0402-RES"))
    )
    (comp (ref "R712")
      (value "220R")
      (footprint "eagle-import:0402-RES")
      (fields (field (name "PARTNO") "RC0402FR-07220RL"))
      (libsource (lib "eagle-import") (part "RESISTOR0402-RES"))
    )
    (comp (ref "R713")
      (value "1K5")
      (footprint "eagle-import:0402-RES")
      (fields (field (name "PARTNO") "RC0402FR-071K5L"))
      (libsource (lib "eagle-import") (part "RESISTOR0402-RES"))
    )
    (comp (ref "R735")
      (value "220R")
      (footprint "eagle-import:0402-RES")
      (fields (field (name "PARTNO") "RC0402FR-07220RL"))
      (libsource (lib "eagle-import") (part "RESISTOR0402-RES"))
    )
    (comp (ref "R736")
      (value "220R")
      (footprint "eagle-import:0402-RES")
      (fields (field (name "PARTNO") "RC0402FR-07220RL"))
      (libsource (lib "eagle-import") (part "RESISTOR0402-RES"))
    )
    (comp (ref "U701")
      (value "TCA62724FMG")
      (footprint "eagle-import:SON10")
      (libsource (lib "eagle-import") (part "TCA62724FMG"))
    )
    (comp (ref "U702")
      (value "LT3469")
      (footprint "eagle-import:SOT23-8")
      (fields (field (name "PARTNO") "LT3469ETS8"))
      (libsource (lib "eagle-import") (part "LT3469"))
    )
    (comp (ref "U703")
      (value "LRTB GFTG-T7AW-1+V7A7-29+R5T9-49-L")
      (footprint "eagle-import:6-PLCC")
      (fields (field (name "PARTNO") "LRTB GFTG-T7AW-1+V7A7-29+R5T9-49-L"))
      (libsource (lib "eagle-import") (part "RGB-LED6-PLCC"))
    )
    (comp (ref "C501")
      (value "10u/10V")
      (footprint "eagle-import:0805-CAP")
      (fields (field (name "PARTNO") "CC0805ZKY5V6BB106"))
      (libsource (lib "eagle-import") (part "CAP0805"))
    )
    (comp (ref "C502")
      (value "0u1")
      (footprint "eagle-import:0402-CAP")
      (fields (field (name "PARTNO") "CC0402ZRY5V7BB104"))
      (libsource (lib "eagle-import") (part "CAP0402"))
    )
    (comp (ref "C503")
      (value "0u1")
      (footprint "eagle-import:0402-CAP")
      (fields (field (name "PARTNO") "CC0402ZRY5V7BB104"))
      (libsource (lib "eagle-import") (part "CAP0402"))
    )
    (comp (ref "C504")
      (value "10n")
      (footprint "eagle-import:0402-CAP")
      (fields (field (name "PARTNO") "CC0402KRX7R7BB103"))
      (libsource (lib "eagle-import") (part "CAP0402"))
    )
    (comp (ref "C505")
      (value "10n")
      (footprint "eagle-import:0402-CAP")
      (fields (field (name "PARTNO") "CC0402KRX7R7BB103"))
      (libsource (lib "eagle-import") (part "CAP0402"))
    )
    (comp (ref "C506")
      (value "10u/10V")
      (footprint "eagle-import:0805-CAP")
      (fields (field (name "PARTNO") "CC0805ZKY5V6BB106"))
      (libsource (lib "eagle-import") (part "CAP0805"))
    )
    (comp (ref "C507")
      (value "0u1")
      (footprint "eagle-import:0402-CAP")
      (fields (field (name "PARTNO") "CC0402ZRY5V7BB104"))
      (libsource (lib "eagle-import") (part "CAP0402"))
    )
    (comp (ref "C508")
      (value "0u1")
      (footprint "eagle-import:0402-CAP")
      (fields (field (name "PARTNO") "CC0402ZRY5V7BB104"))
      (libsource (lib "eagle-import") (part "CAP0402"))
    )
    (comp (ref "C509")
      (value "10u/10V")
      (footprint "eagle-import:0805-CAP")
      (fields (field (name "PARTNO") "CC0805ZKY5V6BB106"))
      (libsource (lib "eagle-import") (part "CAP0805"))
    )
    (comp (ref "C510")
      (value "0u47")
      (footprint "eagle-import:0402-CAP")
      (fields (field (name "PARTNO") "C1005X5R1C474K050BC"))
      (libsource (lib "eagle-import") (part "CAP0402"))
    )
    (comp (ref "C511")
      (value "10u/10V")
      (footprint "eagle-import:0805-CAP")
      (fields (field (name "PARTNO") "CC0805ZKY5V6BB106"))
      (libsource (lib "eagle-import") (part "CAP0805"))
    )
    (comp (ref "C512")
      (value "2u2")
      (footprint "eagle-import:0603-CAP")
      (fields (field (name "PARTNO") "C1608X6S1C225K080AC"))
      (libsource (lib "eagle-import") (part "CAP0603"))
    )
    (comp (ref "C513")
      (value "2u2")
      (footprint "eagle-import:0603-CAP")
      (fields (field (name "PARTNO") "C1608X6S1C225K080AC"))
      (libsource (lib "eagle-import") (part "CAP0603"))
    )
    (comp (ref "C514")
      (value "0u1")
      (footprint "eagle-import:0402-CAP")
      (fields (field (name "PARTNO") "CC0402ZRY5V7BB104"))
      (libsource (lib "eagle-import") (part "CAP0402"))
    )
    (comp (ref "C515")
      (value "0u01")
      (footprint "eagle-import:0603-CAP")
      (fields (field (name "PARTNO") "06033C103JAT2A"))
      (libsource (lib "eagle-import") (part "CAP0603"))
    )
    (comp (ref "U501")
      (value "L3GD20")
      (footprint "eagle-import:L3G4200DH-MAN")
      (libsource (lib "eagle-import") (part "L3G4200DH-LL"))
    )
    (comp (ref "U502")
      (value "L3GD20H")
      (footprint "eagle-import:LGA-16L")
      (libsource (lib "eagle-import") (part "L3GD20H"))
    )
    (comp (ref "U504")
      (value "LSM303D")
      (footprint "eagle-import:LGA-16L")
      (libsource (lib "eagle-import") (part "LSM303D"))
    )
    (comp (ref "U505")
      (value "MPU-6000")
      (footprint "eagle-import:QFN-24")
      (libsource (lib "eagle-import") (part "MPU-6000"))
    )
    (comp (ref "U506")
      (value "MS5611-01BA")
      (footprint "eagle-import:MS5611-01BA")
      (libsource (lib "eagle-import") (part "MS5611-01BA"))
    )
    (comp (ref "X503")
      (value "0512811094")
      (footprint "eagle-import:51281-1094")
      (fields (field (name "PARTNO") "0781191109"))
      (libsource (lib "eagle-import") (part "CONN_FPC_10RA"))
    )
  )
  (nets
    (net (code "1") (name "ACCEL_DRDY") (class "Default")
      (node (ref "U101") (pin "90") (pinfunction "PB4_90") (pintype "bidirectional"))
      (node (ref "U504") (pin "11") (pinfunction "INT1_11") (pintype "bidirectional"))
      (node (ref "X503") (pin "3") (pinfunction "S_3") (pintype "passive"))
    )
    (net (code "2") (name "ALARM") (class "Default")
      (node (ref "R701") (pin "P$2") (pinfunction "2_P$2") (pintype "passive"))
      (node (ref "U101") (pin "77") (pinfunction "PA15_77") (pintype "bidirectional"))
    )
    (net (code "3") (name "BATT_CURRENT_SENS") (class "Default")
      (node (ref "R1101") (pin "P$1") (pinfunction "1_P$1") (pintype "passive"))
      (node (ref "U101") (pin "26") (pinfunction "PA3_26") (pintype "bidirectional"))
    )
    (net (code "4") (name "BATT_VOLTAGE_SENS") (class "Default")
      (node (ref "R1102") (pin "P$1") (pinfunction "1_P$1") (pintype "passive"))
      (node (ref "U101") (pin "25") (pinfunction "PA2_25") (pintype "bidirectional"))
    )
    (net (code "5") (name "CAN1_RX") (class "Default")
      (node (ref "U101") (pin "81") (pinfunction "PD0_81") (pintype "bidirectional"))
      (node (ref "U401") (pin "4") (pinfunction "DOUT_4") (pintype "output"))
    )
    (net (code "6") (name "CAN1_TX") (class "Default")
      (node (ref "U101") (pin "82") (pinfunction "PD1_82") (pintype "bidirectional"))
      (node (ref "U401") (pin "1") (pinfunction "DIN_1") (pintype "input"))
    )
    (net (code "7") (name "CAN2_RX") (class "Default")
      (node (ref "R216") (pin "P$1") (pinfunction "1_P$1") (pintype "passive"))
      (node (ref "U101") (pin "51") (pinfunction "PB12_51") (pintype "bidirectional"))
    )
    (net (code "8") (name "CAN2_TX") (class "Default")
      (node (ref "R215") (pin "P$1") (pinfunction "1_P$1") (pintype "passive"))
      (node (ref "U101") (pin "92") (pinfunction "PB6_92") (pintype "bidirectional"))
    )
    (net (code "9") (name "CAN_H") (class "Default")
      (node (ref "CAN_H") (pin "P$1") (pinfunction "P$1_P$1") (pintype "passive"))
      (node (ref "J405") (pin "2") (pinfunction "2_2") (pintype "passive"))
      (node (ref "R409") (pin "P$1") (pinfunction "1_P$1") (pintype "passive"))
      (node (ref "U401") (pin "7") (pinfunction "CANH_7") (pintype "bidirectional"))
    )
    (net (code "10") (name "CAN_L") (class "Default")
      (node (ref "CAN_L") (pin "P$1") (pinfunction "P$1_P$1") (pintype "passive"))
      (node (ref "J405") (pin "3") (pinfunction "3_3") (pintype "passive"))
      (node (ref "R409") (pin "P$2") (pinfunction "2_P$2") (pintype "passive"))
      (node (ref "U401") (pin "6") (pinfunction "CANL_6") (pintype "bidirectional"))
    )
    (net (code "11") (name "FMU-BOOT0") (class "Default")
      (node (ref "FMU-BOOT1101") (pin "P$1") (pinfunction "P$1_P$1") (pintype "passive"))
      (node (ref "R611") (pin "P$2") (pinfunction "2_P$2") (pintype "passive"))
      (node (ref "U101") (pin "94") (pinfunction "BOOT0_94") (pintype "input"))
    )
    (net (code "12") (name "FMU-CH1") (class "Default")
      (node (ref "U101") (pin "45") (pinfunction "PE14_45") (pintype "bidirectional"))
      (node (ref "U901") (pin "7") (pinfunction "A6_7") (pintype "bidirectional"))
    )
    (net (code "13") (name "FMU-CH2") (class "Default")
      (node (ref "U101") (pin "44") (pinfunction "PE13_44") (pintype "bidirectional"))
      (node (ref "U901") (pin "6") (pinfunction "A5_6") (pintype "bidirectional"))
    )
    (net (code "14") (name "FMU-CH3") (class "Default")
      (node (ref "U101") (pin "42") (pinfunction "PE11_42") (pintype "bidirectional"))
      (node (ref "U901") (pin "5") (pinfunction "A4_5") (pintype "bidirectional"))
    )
    (net (code "15") (name "FMU-CH4") (class "Default")
      (node (ref "U101") (pin "40") (pinfunction "PE9_40") (pintype "bidirectional"))
      (node (ref "U901") (pin "4") (pinfunction "A3_4") (pintype "bidirectional"))
    )
    (net (code "16") (name "FMU-CH5") (class "Default")
      (node (ref "U101") (pin "60") (pinfunction "PD13_60") (pintype "bidirectional"))
      (node (ref "U901") (pin "3") (pinfunction "A2_3") (pintype "bidirectional"))
    )
    (net (code "17") (name "FMU-CH6") (class "Default")
      (node (ref "U101") (pin "61") (pinfunction "PD14_61") (pintype "bidirectional"))
      (node (ref "U901") (pin "1") (pinfunction "A1_1") (pintype "bidirectional"))
    )
    (net (code "18") (name "FMU-I2C1_SCL") (class "Default")
      (node (ref "R401") (pin "P$1") (pinfunction "1_P$1") (pintype "passive"))
      (node (ref "R404") (pin "P$1") (pinfunction "1_P$1") (pintype "passive"))
      (node (ref "U101") (pin "95") (pinfunction "PB8_95") (pintype "bidirectional"))
    )
    (net (code "19") (name "FMU-I2C1_SDA") (class "Default")
      (node (ref "R402") (pin "P$1") (pinfunction "1_P$1") (pintype "passive"))
      (node (ref "R405") (pin "P$1") (pinfunction "1_P$1") (pintype "passive"))
      (node (ref "U101") (pin "96") (pinfunction "PB9_96") (pintype "bidirectional"))
    )
    (net (code "20") (name "FMU-I2C2_SCL") (class "Default")
      (node (ref "R306") (pin "P$1") (pinfunction "1_P$1") (pintype "passive"))
      (node (ref "U101") (pin "47") (pinfunction "PB10_47") (pintype "bidirectional"))
      (node (ref "U701") (pin "3") (pinfunction "SCL_3") (pintype "bidirectional"))
    )
    (net (code "21") (name "FMU-I2C2_SDA") (class "Default")
      (node (ref "R307") (pin "P$1") (pinfunction "1_P$1") (pintype "passive"))
      (node (ref "U101") (pin "48") (pinfunction "PB11_48") (pintype "bidirectional"))
      (node (ref "U701") (pin "2") (pinfunction "SDA_2") (pintype "bidirectional"))
    )
    (net (code "22") (name "FMU-SWCLK") (class "Default")
      (node (ref "JX301") (pin "4") (pinfunction "S_4") (pintype "passive"))
      (node (ref "U101") (pin "76") (pinfunction "PA14_76") (pintype "bidirectional"))
    )
    (net (code "23") (name "FMU-SWDIO") (class "Default")
      (node (ref "JX301") (pin "2") (pinfunction "S_2") (pintype "passive"))
      (node (ref "U101") (pin "72") (pinfunction "PA13_72") (pintype "bidirectional"))
    )
    (net (code "24") (name "FMU-SWO") (class "Default")
      (node (ref "JX301") (pin "6") (pinfunction "S_6") (pintype "passive"))
      (node (ref "U101") (pin "89") (pinfunction "PB3_89") (pintype "bidirectional"))
    )
    (net (code "25") (name "FMU-UART4_RX") (class "Default")
      (node (ref "U101") (pin "24") (pinfunction "PA1_24") (pintype "bidirectional"))
      (node (ref "U202") (pin "8") (pinfunction "A7_8") (pintype "bidirectional"))
    )
    (net (code "26") (name "FMU-UART4_TX") (class "Default")
      (node (ref "U101") (pin "23") (pinfunction "PA0_23") (pintype "bidirectional"))
      (node (ref "U202") (pin "9") (pinfunction "A8_9") (pintype "bidirectional"))
    )
    (net (code "27") (name "FMU-UART7_RX") (class "Default")
      (node (ref "U101") (pin "38") (pinfunction "PE7_38") (pintype "bidirectional"))
      (node (ref "U202") (pin "4") (pinfunction "A3_4") (pintype "bidirectional"))
    )
    (net (code "28") (name "FMU-UART7_TX") (class "Default")
      (node (ref "U101") (pin "39") (pinfunction "PE8_39") (pintype "bidirectional"))
      (node (ref "U202") (pin "5") (pinfunction "A4_5") (pintype "bidirectional"))
    )
    (net (code "29") (name "FMU-UART8_RX") (class "Default")
      (node (ref "U101") (pin "97") (pinfunction "PE0_97") (pintype "bidirectional"))
      (node (ref "U202") (pin "6") (pinfunction "A5_6") (pintype "bidirectional"))
    )
    (net (code "30") (name "FMU-UART8_TX") (class "Default")
      (node (ref "U101") (pin "98") (pinfunction "PE1_98") (pintype "bidirectional"))
      (node (ref "U202") (pin "7") (pinfunction "A6_7") (pintype "bidirectional"))
    )
    (net (code "31") (name "FMU-USART2_CTS") (class "Default")
      (node (ref "U101") (pin "84") (pinfunction "PD3_84") (pintype "bidirectional"))
      (node (ref "U201") (pin "9") (pinfunction "A8_9") (pintype "bidirectional"))
    )
    (net (code "32") (name "FMU-USART2_RTS") (class "Default")
      (node (ref "U101") (pin "85") (pinfunction "PD4_85") (pintype "bidirectional"))
      (node (ref "U201") (pin "8") (pinfunction "A7_8") (pintype "bidirectional"))
    )
    (net (code "33") (name "FMU-USART2_RX") (class "Default")
      (node (ref "U101") (pin "87") (pinfunction "PD6_87") (pintype "bidirectional"))
      (node (ref "U201") (pin "6") (pinfunction "A5_6") (pintype "bidirectional"))
    )
    (net (code "34") (name "FMU-USART2_TX") (class "Default")
      (node (ref "U101") (pin "86") (pinfunction "PD5_86") (pintype "bidirectional"))
      (node (ref "U201") (pin "7") (pinfunction "A6_7") (pintype "bidirectional"))
    )
    (net (code "35") (name "FMU-USART3_CTS") (class "Default")
      (node (ref "U101") (pin "58") (pinfunction "PD11_58") (pintype "bidirectional"))
      (node (ref "U201") (pin "3") (pinfunction "A2_3") (pintype "bidirectional"))
    )
    (net (code "36") (name "FMU-USART3_RTS") (class "Default")
      (node (ref "U101") (pin "59") (pinfunction "PD12_59") (pintype "bidirectional"))
      (node (ref "U201") (pin "1") (pinfunction "A1_1") (pintype "bidirectional"))
    )
    (net (code "37") (name "FMU-USART3_RX") (class "Default")
      (node (ref "U101") (pin "56") (pinfunction "PD9_56") (pintype "bidirectional"))
      (node (ref "U201") (pin "4") (pinfunction "A3_4") (pintype "bidirectional"))
    )
    (net (code "38") (name "FMU-USART3_TX") (class "Default")
      (node (ref "U101") (pin "55") (pinfunction "PD8_55") (pintype "bidirectional"))
      (node (ref "U201") (pin "5") (pinfunction "A4_5") (pintype "bidirectional"))
    )
    (net (code "39") (name "FMU-VDD_3V3") (class "Default")
      (node (ref "C101") (pin "P$1") (pinfunction "1_P$1") (pintype "passive"))
      (node (ref "C201") (pin "P$1") (pinfunction "1_P$1") (pintype "passive"))
      (node (ref "C202") (pin "P$1") (pinfunction "1_P$1") (pintype "passive"))
      (node (ref "C402") (pin "P$1") (pinfunction "1_P$1") (pintype "passive"))
      (node (ref "C603") (pin "P$1") (pinfunction "1_P$1") (pintype "passive"))
      (node (ref "C604") (pin "P$1") (pinfunction "1_P$1") (pintype "passive"))
      (node (ref "C606") (pin "P$1") (pinfunction "1_P$1") (pintype "passive"))
      (node (ref "C607") (pin "P$1") (pinfunction "1_P$1") (pintype "passive"))
      (node (ref "C608") (pin "P$1") (pinfunction "1_P$1") (pintype "passive"))
      (node (ref "C610") (pin "P$1") (pinfunction "1_P$1") (pintype "passive"))
      (node (ref "C612") (pin "P$1") (pinfunction "1_P$1") (pintype "passive"))
      (node (ref "C616") (pin "P$1") (pinfunction "1_P$1") (pintype "passive"))
      (node (ref "C701") (pin "P$1") (pinfunction "1_P$1") (pintype "passive"))
      (node (ref "C902") (pin "P$1") (pinfunction "1_P$1") (pintype "passive"))
      (node (ref "D602") (pin "A") (pinfunction "A_A") (pintype "passive"))
      (node (ref "JX301") (pin "1") (pinfunction "S_1") (pintype "passive"))
      (node (ref "R301") (pin "P$2") (pinfunction "2_P$2") (pintype "passive"))
      (node (ref "R302") (pin "P$2") (pinfunction "2_P$2") (pintype "passive"))
      (node (ref "R303") (pin "P$2") (pinfunction "2_P$2") (pintype "passive"))
      (node (ref "R304") (pin "P$2") (pinfunction "2_P$2") (pintype "passive"))
      (node (ref "R305") (pin "P$2") (pinfunction "2_P$2") (pintype "passive"))
      (node (ref "R306") (pin "P$2") (pinfunction "2_P$2") (pintype "passive"))
      (node (ref "R307") (pin "P$2") (pinfunction "2_P$2") (pintype "passive"))
      (node (ref "R401") (pin "P$2") (pinfunction "2_P$2") (pintype "passive"))
      (node (ref "R402") (pin "P$2") (pinfunction "2_P$2") (pintype "passive"))
      (node (ref "R602") (pin "P$2") (pinfunction "2_P$2") (pintype "passive"))
      (node (ref "R604") (pin "P$2") (pinfunction "2_P$2") (pintype "passive"))
      (node (ref "U101") (pin "100") (pinfunction "VDD_100") (pintype "power_in"))
      (node (ref "U101") (pin "11") (pinfunction "VDD_11") (pintype "power_in"))
      (node (ref "U101") (pin "19") (pinfunction "VDD_19") (pintype "power_in"))
      (node (ref "U101") (pin "21") (pinfunction "VREF+_21") (pintype "input"))
      (node (ref "U101") (pin "22") (pinfunction "VDDA_22") (pintype "power_in"))
      (node (ref "U101") (pin "28") (pinfunction "VDD_28") (pintype "power_in"))
      (node (ref "U101") (pin "50") (pinfunction "VDD_50") (pintype "power_in"))
      (node (ref "U101") (pin "75") (pinfunction "VDD_75") (pintype "power_in"))
      (node (ref "U102") (pin "3") (pinfunction "~{W}_3") (pintype "bidirectional"))
      (node (ref "U102") (pin "7") (pinfunction "~{HOLD}_7") (pintype "bidirectional"))
      (node (ref "U102") (pin "8") (pinfunction "VDD_8") (pintype "bidirectional"))
      (node (ref "U201") (pin "10") (pinfunction "OE_10") (pintype "input"))
      (node (ref "U201") (pin "19") (pinfunction "VCCB_19") (pintype "input"))
      (node (ref "U201") (pin "2") (pinfunction "VCCA_2") (pintype "input"))
      (node (ref "U202") (pin "10") (pinfunction "OE_10") (pintype "input"))
      (node (ref "U202") (pin "19") (pinfunction "VCCB_19") (pintype "input"))
      (node (ref "U202") (pin "2") (pinfunction "VCCA_2") (pintype "input"))
      (node (ref "U301") (pin "4") (pinfunction "VCC_4") (pintype "passive"))
      (node (ref "U401") (pin "3") (pinfunction "VCC_3") (pintype "input"))
      (node (ref "U603") (pin "7") (pinfunction "VOUT2_7") (pintype "bidirectional"))
      (node (ref "U701") (pin "1") (pinfunction "~{SHDN}_1") (pintype "input"))
      (node (ref "U701") (pin "10") (pinfunction "VIN_10") (pintype "power_in"))
      (node (ref "U901") (pin "10") (pinfunction "OE_10") (pintype "input"))
      (node (ref "U901") (pin "19") (pinfunction "VCCB_19") (pintype "input"))
      (node (ref "U901") (pin "2") (pinfunction "VCCA_2") (pintype "input"))
      (node (ref "VDD_3V1101") (pin "P$1") (pinfunction "P$1_P$1") (pintype "passive"))
    )
    (net (code "40") (name "FMU-~{RESET}") (class "Default")
      (node (ref "C609") (pin "P$2") (pinfunction "2_P$2") (pintype "passive"))
      (node (ref "R635") (pin "P$1") (pinfunction "1_P$1") (pintype "passive"))
      (node (ref "S601") (pin "A1") (pinfunction "1_A1") (pintype "passive"))
      (node (ref "U101") (pin "14") (pinfunction "NRST_14") (pintype "input"))
      (node (ref "U603") (pin "3") (pinfunction "POR2_3") (pintype "bidirectional"))
      (node (ref "U701") (pin "4") (pinfunction "~{RESET}_4") (pintype "input"))
    )
    (net (code "41") (name "FMU_AUX_ADC1") (class "Default")
      (node (ref "R408") (pin "P$1") (pinfunction "1_P$1") (pintype "passive"))
      (node (ref "U101") (pin "18") (pinfunction "PC3_18") (pintype "bidirectional"))
    )
    (net (code "42") (name "FMU_AUX_ADC2") (class "Default")
      (node (ref "R407") (pin "P$1") (pinfunction "1_P$1") (pintype "passive"))
      (node (ref "U101") (pin "33") (pinfunction "PC4_33") (pintype "bidirectional"))
    )
    (net (code "43") (name "FRAM_MISO") (class "Default")
      (node (ref "U101") (pin "53") (pinfunction "PB14_53") (pintype "bidirectional"))
      (node (ref "U102") (pin "2") (pinfunction "Q_2") (pintype "bidirectional"))
    )
    (net (code "44") (name "FRAM_MOSI") (class "Default")
      (node (ref "U101") (pin "54") (pinfunction "PB15_54") (pintype "bidirectional"))
      (node (ref "U102") (pin "5") (pinfunction "D_5") (pintype "bidirectional"))
    )
    (net (code "45") (name "FRAM_SCK") (class "Default")
      (node (ref "U101") (pin "52") (pinfunction "PB13_52") (pintype "bidirectional"))
      (node (ref "U102") (pin "6") (pinfunction "C_6") (pintype "bidirectional"))
    )
    (net (code "46") (name "GND") (class "Default")
      (node (ref "B601") (pin "2") (pinfunction "NEG_2") (pintype "bidirectional"))
      (node (ref "C1001") (pin "P$2") (pinfunction "2_P$2") (pintype "passive"))
      (node (ref "C1002") (pin "P$2") (pinfunction "2_P$2") (pintype "passive"))
      (node (ref "C1003") (pin "P$2") (pinfunction "2_P$2") (pintype "passive"))
      (node (ref "C1004") (pin "P$2") (pinfunction "2_P$2") (pintype "passive"))
      (node (ref "C1005") (pin "P$2") (pinfunction "2_P$2") (pintype "passive"))
      (node (ref "C1008") (pin "P$2") (pinfunction "2_P$2") (pintype "passive"))
      (node (ref "C101") (pin "P$2") (pinfunction "2_P$2") (pintype "passive"))
      (node (ref "C102") (pin "P$2") (pinfunction "2_P$2") (pintype "passive"))
      (node (ref "C103") (pin "P$1") (pinfunction "1_P$1") (pintype "passive"))
      (node (ref "C1101") (pin "P$2") (pinfunction "2_P$2") (pintype "passive"))
      (node (ref "C1102") (pin "P$2") (pinfunction "2_P$2") (pintype "passive"))
      (node (ref "C1103") (pin "P$2") (pinfunction "2_P$2") (pintype "passive"))
      (node (ref "C1104") (pin "P$2") (pinfunction "2_P$2") (pintype "passive"))
      (node (ref "C1105") (pin "P$2") (pinfunction "2_P$2") (pintype "passive"))
      (node (ref "C1106") (pin "P$2") (pinfunction "2_P$2") (pintype "passive"))
      (node (ref "C1107") (pin "P$2") (pinfunction "2_P$2") (pintype "passive"))
      (node (ref "C1108") (pin "P$2") (pinfunction "2_P$2") (pintype "passive"))
      (node (ref "C1109") (pin "P$2") (pinfunction "2_P$2") (pintype "passive"))
      (node (ref "C1110") (pin "P$2") (pinfunction "2_P$2") (pintype "passive"))
      (node (ref "C201") (pin "P$2") (pinfunction "2_P$2") (pintype "passive"))
      (node (ref "C202") (pin "P$2") (pinfunction "2_P$2") (pintype "passive"))
      (node (ref "C401") (pin "P$2") (pinfunction "2_P$2") (pintype "passive"))
      (node (ref "C402") (pin "P$2") (pinfunction "2_P$2") (pintype "passive"))
      (node (ref "C501") (pin "P$2") (pinfunction "2_P$2") (pintype "passive"))
      (node (ref "C502") (pin "P$2") (pinfunction "2_P$2") (pintype "passive"))
      (node (ref "C503") (pin "P$2") (pinfunction "2_P$2") (pintype "passive"))
      (node (ref "C504") (pin "P$2") (pinfunction "2_P$2") (pintype "passive"))
      (node (ref "C505") (pin "P$2") (pinfunction "2_P$2") (pintype "passive"))
      (node (ref "C506") (pin "P$2") (pinfunction "2_P$2") (pintype "passive"))
      (node (ref "C507") (pin "P$2") (pinfunction "2_P$2") (pintype "passive"))
      (node (ref "C508") (pin "P$2") (pinfunction "2_P$2") (pintype "passive"))
      (node (ref "C509") (pin "P$2") (pinfunction "2_P$2") (pintype "passive"))
      (node (ref "C511") (pin "P$2") (pinfunction "2_P$2") (pintype "passive"))
      (node (ref "C512") (pin "P$2") (pinfunction "2_P$2") (pintype "passive"))
      (node (ref "C513") (pin "P$2") (pinfunction "2_P$2") (pintype "passive"))
      (node (ref "C514") (pin "P$2") (pinfunction "2_P$2") (pintype "passive"))
      (node (ref "C515") (pin "P$2") (pinfunction "2_P$2") (pintype "passive"))
      (node (ref "C601") (pin "P$2") (pinfunction "2_P$2") (pintype "passive"))
      (node (ref "C602") (pin "P$1") (pinfunction "1_P$1") (pintype "passive"))
      (node (ref "C603") (pin "P$2") (pinfunction "2_P$2") (pintype "passive"))
      (node (ref "C604") (pin "P$2") (pinfunction "2_P$2") (pintype "passive"))
      (node (ref "C605") (pin "P$2") (pinfunction "2_P$2") (pintype "passive"))
      (node (ref "C606") (pin "P$2") (pinfunction "2_P$2") (pintype "passive"))
      (node (ref "C607") (pin "P$2") (pinfunction "2_P$2") (pintype "passive"))
      (node (ref "C608") (pin "P$2") (pinfunction "2_P$2") (pintype "passive"))
      (node (ref "C609") (pin "P$1") (pinfunction "1_P$1") (pintype "passive"))
      (node (ref "C610") (pin "P$2") (pinfunction "2_P$2") (pintype "passive"))
      (node (ref "C611") (pin "P$2") (pinfunction "2_P$2") (pintype "passive"))
      (node (ref "C612") (pin "P$2") (pinfunction "2_P$2") (pintype "passive"))
      (node (ref "C613") (pin "P$2") (pinfunction "2_P$2") (pintype "passive"))
      (node (ref "C614") (pin "P$2") (pinfunction "2_P$2") (pintype "passive"))
      (node (ref "C615") (pin "P$2") (pinfunction "2_P$2") (pintype "passive"))
      (node (ref "C616") (pin "P$2") (pinfunction "2_P$2") (pintype "passive"))
      (node (ref "C617") (pin "P$2") (pinfunction "2_P$2") (pintype "passive"))
      (node (ref "C618") (pin "P$2") (pinfunction "2_P$2") (pintype "passive"))
      (node (ref "C701") (pin "P$2") (pinfunction "2_P$2") (pintype "passive"))
      (node (ref "C702") (pin "P$2") (pinfunction "2_P$2") (pintype "passive"))
      (node (ref "C703") (pin "P$2") (pinfunction "2_P$2") (pintype "passive"))
      (node (ref "C704") (pin "P$2") (pinfunction "2_P$2") (pintype "passive"))
      (node (ref "C801") (pin "P$1") (pinfunction "1_P$1") (pintype "passive"))
      (node (ref "C802") (pin "P$2") (pinfunction "2_P$2") (pintype "passive"))
      (node (ref "C803") (pin "P$2") (pinfunction "2_P$2") (pintype "passive"))
      (node (ref "C804") (pin "P$2") (pinfunction "2_P$2") (pintype "passive"))
      (node (ref "C805") (pin "P$2") (pinfunction "2_P$2") (pintype "passive"))
      (node (ref "C806") (pin "P$1") (pinfunction "1_P$1") (pintype "passive"))
      (node (ref "C901") (pin "P$2") (pinfunction "2_P$2") (pintype "passive"))
      (node (ref "C902") (pin "P$2") (pinfunction "2_P$2") (pintype "passive"))
      (node (ref "C903") (pin "P$2") (pinfunction "2_P$2") (pintype "passive"))
      (node (ref "D201") (pin "A") (pinfunction "A_A") (pintype "passive"))
      (node (ref "D202") (pin "A") (pinfunction "A_A") (pintype "passive"))
      (node (ref "D203") (pin "A") (pinfunction "A_A") (pintype "passive"))
      (node (ref "D401") (pin "A") (pinfunction "A_A") (pintype "passive"))
      (node (ref "D402") (pin "A") (pinfunction "A_A") (pintype "passive"))
      (node (ref "D403") (pin "A") (pinfunction "A_A") (pintype "passive"))
      (node (ref "D404") (pin "A") (pinfunction "A_A") (pintype "passive"))
      (node (ref "D701") (pin "A") (pinfunction "A_A") (pintype "passive"))
      (node (ref "D801") (pin "A") (pinfunction "A_A") (pintype "passive"))
      (node (ref "D901") (pin "A") (pinfunction "A_A") (pintype "passive"))
      (node (ref "D902") (pin "A") (pinfunction "A_A") (pintype "passive"))
      (node (ref "D903") (pin "A") (pinfunction "A_A") (pintype "passive"))
      (node (ref "GND") (pin "P$1") (pinfunction "P$1_P$1") (pintype "passive"))
      (node (ref "GND.") (pin "P$1") (pinfunction "P$1_P$1") (pintype "passive"))
      (node (ref "J201") (pin "6") (pinfunction "6_6") (pintype "passive"))
      (node (ref "J202") (pin "6") (pinfunction "6_6") (pintype "passive"))
      (node (ref "J203") (pin "6") (pinfunction "6_6") (pintype "passive"))
      (node (ref "J204") (pin "6") (pinfunction "6_6") (pintype "passive"))
      (node (ref "J301") (pin "GND") (pinfunction "5_GND") (pintype "power_in"))
      (node (ref "J301") (pin "GND1") (pinfunction "GND1_GND1") (pintype "bidirectional"))
      (node (ref "J301") (pin "GND2") (pinfunction "GND2_GND2") (pintype "bidirectional"))
      (node (ref "J301") (pin "GND3") (pinfunction "GND3_GND3") (pintype "bidirectional"))
      (node (ref "J301") (pin "GND4") (pinfunction "GND4_GND4") (pintype "bidirectional"))
      (node (ref "J302") (pin "4") (pinfunction "4_4") (pintype "passive"))
      (node (ref "J401") (pin "4") (pinfunction "4_4") (pintype "passive"))
      (node (ref "J402") (pin "3") (pinfunction "3_3") (pintype "passive"))
      (node (ref "J403") (pin "7") (pinfunction "7_7") (pintype "passive"))
      (node (ref "J404") (pin "3") (pinfunction "3_3") (pintype "passive"))
      (node (ref "J404") (pin "5") (pinfunction "5_5") (pintype "passive"))
      (node (ref "J405") (pin "4") (pinfunction "4_4") (pintype "passive"))
      (node (ref "J601") (pin "5") (pinfunction "5_5") (pintype "passive"))
      (node (ref "J601") (pin "6") (pinfunction "6_6") (pintype "passive"))
      (node (ref "J701") (pin "2") (pinfunction "2_2") (pintype "passive"))
      (node (ref "J801") (pin "P$2") (pinfunction "P$2_P$2") (pintype "bidirectional"))
      (node (ref "J901") (pin "12") (pinfunction "S_12") (pintype "passive"))
      (node (ref "J901") (pin "15") (pinfunction "S_15") (pintype "passive"))
      (node (ref "J901") (pin "18") (pinfunction "S_18") (pintype "passive"))
      (node (ref "J901") (pin "21") (pinfunction "S_21") (pintype "passive"))
      (node (ref "J901") (pin "24") (pinfunction "S_24") (pintype "passive"))
      (node (ref "J901") (pin "27") (pinfunction "S_27") (pintype "passive"))
      (node (ref "J901") (pin "3") (pinfunction "S_3") (pintype "passive"))
      (node (ref "J901") (pin "30") (pinfunction "S_30") (pintype "passive"))
      (node (ref "J901") (pin "33") (pinfunction "S_33") (pintype "passive"))
      (node (ref "J901") (pin "36") (pinfunction "S_36") (pintype "passive"))
      (node (ref "J901") (pin "39") (pinfunction "S_39") (pintype "passive"))
      (node (ref "J901") (pin "42") (pinfunction "S_42") (pintype "passive"))
      (node (ref "J901") (pin "45") (pinfunction "S_45") (pintype "passive"))
      (node (ref "J901") (pin "48") (pinfunction "S_48") (pintype "passive"))
      (node (ref "J901") (pin "6") (pinfunction "S_6") (pintype "passive"))
      (node (ref "J901") (pin "9") (pinfunction "S_9") (pintype "passive"))
      (node (ref "JX301") (pin "3") (pinfunction "S_3") (pintype "passive"))
      (node (ref "JX301") (pin "5") (pinfunction "S_5") (pintype "passive"))
      (node (ref "JX301") (pin "9") (pinfunction "S_9") (pintype "passive"))
      (node (ref "JX801") (pin "3") (pinfunction "GND_3") (pintype "bidirectional"))
      (node (ref "JX802") (pin "3") (pinfunction "S_3") (pintype "passive"))
      (node (ref "JX802") (pin "5") (pinfunction "S_5") (pintype "passive"))
      (node (ref "JX802") (pin "9") (pinfunction "S_9") (pintype "passive"))
      (node (ref "L1101") (pin "P$3") (pinfunction "P$3_P$3") (pintype "bidirectional"))
      (node (ref "L1101") (pin "P$4") (pinfunction "P$3_P$4") (pintype "bidirectional"))
      (node (ref "L1101") (pin "P$5") (pinfunction "P$3_P$5") (pintype "bidirectional"))
      (node (ref "L1102") (pin "P$3") (pinfunction "P$3_P$3") (pintype "bidirectional"))
      (node (ref "L1102") (pin "P$4") (pinfunction "P$3_P$4") (pintype "bidirectional"))
      (node (ref "L1102") (pin "P$5") (pinfunction "P$3_P$5") (pintype "bidirectional"))
      (node (ref "L201") (pin "P$3") (pinfunction "P$3_P$3") (pintype "bidirectional"))
      (node (ref "L201") (pin "P$4") (pinfunction "P$3_P$4") (pintype "bidirectional"))
      (node (ref "L201") (pin "P$5") (pinfunction "P$3_P$5") (pintype "bidirectional"))
      (node (ref "L202") (pin "P$3") (pinfunction "P$3_P$3") (pintype "bidirectional"))
      (node (ref "L202") (pin "P$4") (pinfunction "P$3_P$4") (pintype "bidirectional"))
      (node (ref "L202") (pin "P$5") (pinfunction "P$3_P$5") (pintype "bidirectional"))
      (node (ref "L203") (pin "P$3") (pinfunction "P$3_P$3") (pintype "bidirectional"))
      (node (ref "L203") (pin "P$4") (pinfunction "P$3_P$4") (pintype "bidirectional"))
      (node (ref "L203") (pin "P$5") (pinfunction "P$3_P$5") (pintype "bidirectional"))
      (node (ref "L401") (pin "P$3") (pinfunction "P$3_P$3") (pintype "bidirectional"))
      (node (ref "L401") (pin "P$4") (pinfunction "P$3_P$4") (pintype "bidirectional"))
      (node (ref "L401") (pin "P$5") (pinfunction "P$3_P$5") (pintype "bidirectional"))
      (node (ref "L402") (pin "P$3") (pinfunction "P$3_P$3") (pintype "bidirectional"))
      (node (ref "L402") (pin "P$4") (pinfunction "P$3_P$4") (pintype "bidirectional"))
      (node (ref "L402") (pin "P$5") (pinfunction "P$3_P$5") (pintype "bidirectional"))
      (node (ref "L403") (pin "P$3") (pinfunction "P$3_P$3") (pintype "bidirectional"))
      (node (ref "L403") (pin "P$4") (pinfunction "P$3_P$4") (pintype "bidirectional"))
      (node (ref "L403") (pin "P$5") (pinfunction "P$3_P$5") (pintype "bidirectional"))
      (node (ref "L404") (pin "P$3") (pinfunction "P$3_P$3") (pintype "bidirectional"))
      (node (ref "L404") (pin "P$4") (pinfunction "P$3_P$4") (pintype "bidirectional"))
      (node (ref "L404") (pin "P$5") (pinfunction "P$3_P$5") (pintype "bidirectional"))
      (node (ref "L603") (pin "P$3") (pinfunction "P$3_P$3") (pintype "bidirectional"))
      (node (ref "L603") (pin "P$4") (pinfunction "P$3_P$4") (pintype "bidirectional"))
      (node (ref "L603") (pin "P$5") (pinfunction "P$3_P$5") (pintype "bidirectional"))
      (node (ref "L901") (pin "P$3") (pinfunction "P$3_P$3") (pintype "bidirectional"))
      (node (ref "L901") (pin "P$4") (pinfunction "P$3_P$4") (pintype "bidirectional"))
      (node (ref "L901") (pin "P$5") (pinfunction "P$3_P$5") (pintype "bidirectional"))
      (node (ref "R1001") (pin "P$1") (pinfunction "1_P$1") (pintype "passive"))
      (node (ref "R1002") (pin "P$1") (pinfunction "1_P$1") (pintype "passive"))
      (node (ref "R102") (pin "P$2") (pinfunction "2_P$2") (pintype "passive"))
      (node (ref "R1103") (pin "P$2") (pinfunction "2_P$2") (pintype "passive"))
      (node (ref "R1104") (pin "P$2") (pinfunction "2_P$2") (pintype "passive"))
      (node (ref "R1107") (pin "P$2") (pinfunction "2_P$2") (pintype "passive"))
      (node (ref "R1111") (pin "P$2") (pinfunction "2_P$2") (pintype "passive"))
      (node (ref "R1114") (pin "P$2") (pinfunction "2_P$2") (pintype "passive"))
      (node (ref "R1115") (pin "P$1") (pinfunction "1_P$1") (pintype "passive"))
      (node (ref "R403") (pin "P$1") (pinfunction "1_P$1") (pintype "passive"))
      (node (ref "R610") (pin "P$2") (pinfunction "2_P$2") (pintype "passive"))
      (node (ref "R611") (pin "P$1") (pinfunction "1_P$1") (pintype "passive"))
      (node (ref "R615") (pin "P$2") (pinfunction "2_P$2") (pintype "passive"))
      (node (ref "R616") (pin "P$2") (pinfunction "2_P$2") (pintype "passive"))
      (node (ref "R617") (pin "P$2") (pinfunction "2_P$2") (pintype "passive"))
      (node (ref "R621") (pin "1") (pinfunction "1_1") (pintype "passive"))
      (node (ref "R702") (pin "P$2") (pinfunction "2_P$2") (pintype "passive"))
      (node (ref "R704") (pin "P$1") (pinfunction "1_P$1") (pintype "passive"))
      (node (ref "R706") (pin "P$2") (pinfunction "2_P$2") (pintype "passive"))
      (node (ref "R708") (pin "P$1") (pinfunction "1_P$1") (pintype "passive"))
      (node (ref "R711") (pin "P$1") (pinfunction "1_P$1") (pintype "passive"))
      (node (ref "R713") (pin "P$2") (pinfunction "2_P$2") (pintype "passive"))
      (node (ref "R801") (pin "P$2") (pinfunction "2_P$2") (pintype "passive"))
      (node (ref "R802") (pin "P$2") (pinfunction "2_P$2") (pintype "passive"))
      (node (ref "R919") (pin "P$1") (pinfunction "1_P$1") (pintype "passive"))
      (node (ref "S601") (pin "B3") (pinfunction "2_B3") (pintype "passive"))
      (node (ref "S801") (pin "B3") (pinfunction "2_B3") (pintype "passive"))
      (node (ref "U1001") (pin "2") (pinfunction "VSS_2") (pintype "bidirectional"))
      (node (ref "U1001") (pin "5") (pinfunction "~{CE}_5") (pintype "bidirectional"))
      (node (ref "U1001") (pin "6") (pinfunction "VBAT_6") (pintype "bidirectional"))
      (node (ref "U1001") (pin "GND") (pinfunction "VSS_GND") (pintype "bidirectional"))
      (node (ref "U1001") (pin "P$2") (pinfunction "VSS_P$2") (pintype "bidirectional"))
      (node (ref "U1001") (pin "P$3") (pinfunction "VSS_P$3") (pintype "bidirectional"))
      (node (ref "U1002") (pin "2") (pinfunction "GND_2") (pintype "bidirectional"))
      (node (ref "U1002") (pin "GND") (pinfunction "GND_GND") (pintype "bidirectional"))
      (node (ref "U101") (pin "10") (pinfunction "VSS_10") (pintype "power_in"))
      (node (ref "U101") (pin "20") (pinfunction "VSSA_20") (pintype "power_in"))
      (node (ref "U101") (pin "27") (pinfunction "VSS_27") (pintype "power_in"))
      (node (ref "U101") (pin "74") (pinfunction "VSS_74") (pintype "power_in"))
      (node (ref "U101") (pin "99") (pinfunction "VSS_99") (pintype "power_in"))
      (node (ref "U102") (pin "4") (pinfunction "VSS_4") (pintype "bidirectional"))
      (node (ref "U1101") (pin "P$10") (pinfunction "GND_P$10") (pintype "bidirectional"))
      (node (ref "U1101") (pin "P$25") (pinfunction "GND_P$25") (pintype "bidirectional"))
      (node (ref "U201") (pin "11") (pinfunction "GND_11") (pintype "power_in"))
      (node (ref "U202") (pin "11") (pinfunction "GND_11") (pintype "power_in"))
      (node (ref "U301") (pin "6") (pinfunction "GND_6") (pintype "power_in"))
      (node (ref "U302") (pin "2") (pinfunction "GND_2") (pintype "bidirectional"))
      (node (ref "U401") (pin "2") (pinfunction "GND_2") (pintype "power_in"))
      (node (ref "U401") (pin "5") (pinfunction "SHDN_5") (pintype "input"))
      (node (ref "U401") (pin "8") (pinfunction "RS_8") (pintype "input"))
      (node (ref "U501") (pin "10") (pinfunction "RES_P10_GND_10") (pintype "bidirectional"))
      (node (ref "U501") (pin "11") (pinfunction "RES_P11_GND_11") (pintype "bidirectional"))
      (node (ref "U501") (pin "12") (pinfunction "RES_P12_GND_12") (pintype "bidirectional"))
      (node (ref "U501") (pin "13") (pinfunction "GND_13") (pintype "bidirectional"))
      (node (ref "U501") (pin "8") (pinfunction "RES_P8_GND_8") (pintype "bidirectional"))
      (node (ref "U501") (pin "9") (pinfunction "RES_P9_GND_9") (pintype "bidirectional"))
      (node (ref "U502") (pin "10") (pinfunction "GND_10") (pintype "bidirectional"))
      (node (ref "U502") (pin "11") (pinfunction "GND_11") (pintype "bidirectional"))
      (node (ref "U502") (pin "12") (pinfunction "GND_12") (pintype "bidirectional"))
      (node (ref "U502") (pin "13") (pinfunction "GND_13") (pintype "bidirectional"))
      (node (ref "U502") (pin "9") (pinfunction "GND_9") (pintype "bidirectional"))
      (node (ref "U504") (pin "10") (pinfunction "RSRV_10") (pintype "bidirectional"))
      (node (ref "U504") (pin "12") (pinfunction "GND_12") (pintype "bidirectional"))
      (node (ref "U504") (pin "13") (pinfunction "GND_13") (pintype "bidirectional"))
      (node (ref "U504") (pin "16") (pinfunction "GND_16") (pintype "bidirectional"))
      (node (ref "U504") (pin "5") (pinfunction "GND_5") (pintype "bidirectional"))
      (node (ref "U505") (pin "1") (pinfunction "CLKIN_1") (pintype "bidirectional"))
      (node (ref "U505") (pin "18") (pinfunction "GND_18") (pintype "bidirectional"))
      (node (ref "U506") (pin "2") (pinfunction "PS_2") (pintype "bidirectional"))
      (node (ref "U506") (pin "3") (pinfunction "GND_3") (pintype "bidirectional"))
      (node (ref "U601") (pin "2") (pinfunction "VSS_2") (pintype "bidirectional"))
      (node (ref "U601") (pin "6") (pinfunction "VBAT_6") (pintype "bidirectional"))
      (node (ref "U601") (pin "GND") (pinfunction "VSS_GND") (pintype "bidirectional"))
      (node (ref "U601") (pin "P$2") (pinfunction "VSS_P$2") (pintype "bidirectional"))
      (node (ref "U601") (pin "P$3") (pinfunction "VSS_P$3") (pintype "bidirectional"))
      (node (ref "U602") (pin "2") (pinfunction "VSS_2") (pintype "bidirectional"))
      (node (ref "U602") (pin "6") (pinfunction "VBAT_6") (pintype "bidirectional"))
      (node (ref "U602") (pin "GND") (pinfunction "VSS_GND") (pintype "bidirectional"))
      (node (ref "U602") (pin "P$2") (pinfunction "VSS_P$2") (pintype "bidirectional"))
      (node (ref "U602") (pin "P$3") (pinfunction "VSS_P$3") (pintype "bidirectional"))
      (node (ref "U603") (pin "2") (pinfunction "GND_2") (pintype "bidirectional"))
      (node (ref "U603") (pin "GND") (pinfunction "GND_GND") (pintype "bidirectional"))
      (node (ref "U701") (pin "5") (pinfunction "GND_5") (pintype "power_in"))
      (node (ref "U702") (pin "4") (pinfunction "GND_4") (pintype "power_in"))
      (node (ref "U801") (pin "23") (pinfunction "VSS_1_23") (pintype "power_in"))
      (node (ref "U801") (pin "35") (pinfunction "VSS_2_35") (pintype "power_in"))
      (node (ref "U801") (pin "47") (pinfunction "VSS_3_47") (pintype "power_in"))
      (node (ref "U801") (pin "8") (pinfunction "VSSA_8") (pintype "power_in"))
      (node (ref "U901") (pin "11") (pinfunction "GND_11") (pintype "power_in"))
      (node (ref "U902") (pin "11") (pinfunction "GND_11") (pintype "power_in"))
      (node (ref "U903") (pin "1") (pinfunction "~{1OE}_1") (pintype "input"))
      (node (ref "U903") (pin "4") (pinfunction "GND_4") (pintype "power_in"))
      (node (ref "X101") (pin "2") (pinfunction "NC_2_2") (pintype "power_in"))
      (node (ref "X101") (pin "4") (pinfunction "NC_4_4") (pintype "power_in"))
      (node (ref "X503") (pin "2") (pinfunction "S_2") (pintype "passive"))
      (node (ref "X801") (pin "2") (pinfunction "NC_2_2") (pintype "power_in"))
      (node (ref "X801") (pin "4") (pinfunction "NC_4_4") (pintype "power_in"))
    )
    (net (code "47") (name "GPIO_EXT_1") (class "Default")
      (node (ref "J403") (pin "6") (pinfunction "6_6") (pintype "passive"))
      (node (ref "U101") (pin "8") (pinfunction "PC14_8") (pintype "bidirectional"))
    )
    (net (code "48") (name "GYRO_DRDY") (class "Default")
      (node (ref "U101") (pin "35") (pinfunction "PB0_35") (pintype "bidirectional"))
      (node (ref "U501") (pin "6") (pinfunction "DRDY/INT2_6") (pintype "output"))
      (node (ref "U502") (pin "6") (pinfunction "DRDY/INT2_6") (pintype "bidirectional"))
      (node (ref "X503") (pin "5") (pinfunction "S_5") (pintype "passive"))
    )
    (net (code "49") (name "IO-BOOT0") (class "Default")
      (node (ref "IO-BOOT1101") (pin "P$1") (pinfunction "P$1_P$1") (pintype "passive"))
      (node (ref "R801") (pin "P$1") (pinfunction "1_P$1") (pintype "passive"))
      (node (ref "U801") (pin "44") (pinfunction "BOOT0_44") (pintype "input"))
    )
    (net (code "50") (name "IO-CH1") (class "Default")
      (node (ref "U801") (pin "10") (pinfunction "PA0_10") (pintype "bidirectional"))
      (node (ref "U902") (pin "9") (pinfunction "A8_9") (pintype "bidirectional"))
    )
    (net (code "51") (name "IO-CH2") (class "Default")
      (node (ref "U801") (pin "11") (pinfunction "PA1_11") (pintype "bidirectional"))
      (node (ref "U902") (pin "8") (pinfunction "A7_8") (pintype "bidirectional"))
    )
    (net (code "52") (name "IO-CH3") (class "Default")
      (node (ref "U801") (pin "45") (pinfunction "PB8_45") (pintype "bidirectional"))
      (node (ref "U902") (pin "7") (pinfunction "A6_7") (pintype "bidirectional"))
    )
    (net (code "53") (name "IO-CH4") (class "Default")
      (node (ref "U801") (pin "46") (pinfunction "PB9_46") (pintype "bidirectional"))
      (node (ref "U902") (pin "6") (pinfunction "A5_6") (pintype "bidirectional"))
    )
    (net (code "54") (name "IO-CH5") (class "Default")
      (node (ref "U801") (pin "16") (pinfunction "PA6_16") (pintype "bidirectional"))
      (node (ref "U902") (pin "5") (pinfunction "A4_5") (pintype "bidirectional"))
    )
    (net (code "55") (name "IO-CH6") (class "Default")
      (node (ref "U801") (pin "17") (pinfunction "PA7_17") (pintype "bidirectional"))
      (node (ref "U902") (pin "4") (pinfunction "A3_4") (pintype "bidirectional"))
    )
    (net (code "56") (name "IO-CH7") (class "Default")
      (node (ref "U801") (pin "18") (pinfunction "PB0_18") (pintype "bidirectional"))
      (node (ref "U902") (pin "3") (pinfunction "A2_3") (pintype "bidirectional"))
    )
    (net (code "57") (name "IO-CH8") (class "Default")
      (node (ref "U801") (pin "19") (pinfunction "PB1_19") (pintype "bidirectional"))
      (node (ref "U902") (pin "1") (pinfunction "A1_1") (pintype "bidirectional"))
    )
    (net (code "58") (name "IO-SWCLK") (class "Default")
      (node (ref "JX802") (pin "4") (pinfunction "S_4") (pintype "passive"))
      (node (ref "U801") (pin "37") (pinfunction "PA14_37") (pintype "bidirectional"))
    )
    (net (code "59") (name "IO-SWDIO") (class "Default")
      (node (ref "JX802") (pin "2") (pinfunction "S_2") (pintype "passive"))
      (node (ref "U801") (pin "34") (pinfunction "PA13_34") (pintype "bidirectional"))
    )
    (net (code "60") (name "IO-SWO") (class "Default")
      (node (ref "JX802") (pin "6") (pinfunction "S_6") (pintype "passive"))
      (node (ref "U801") (pin "39") (pinfunction "PB3_39") (pintype "bidirectional"))
    )
    (net (code "61") (name "IO-USART1_RX") (class "Default")
      (node (ref "J801") (pin "P$3") (pinfunction "P$3_P$3") (pintype "bidirectional"))
      (node (ref "JX801") (pin "2") (pinfunction "+5V_2") (pintype "bidirectional"))
      (node (ref "U801") (pin "31") (pinfunction "PA10_31") (pintype "bidirectional"))
    )
    (net (code "62") (name "IO-USART1_TX") (class "Default")
      (node (ref "JX801") (pin "1") (pinfunction "PPM_1") (pintype "bidirectional"))
      (node (ref "R101") (pin "P$2") (pinfunction "2_P$2") (pintype "passive"))
      (node (ref "U801") (pin "30") (pinfunction "PA9_30") (pintype "bidirectional"))
    )
    (net (code "63") (name "IO-VDD_3V3") (class "Default")
      (node (ref "C1003") (pin "P$1") (pinfunction "1_P$1") (pintype "passive"))
      (node (ref "C1004") (pin "P$1") (pinfunction "1_P$1") (pintype "passive"))
      (node (ref "C802") (pin "P$1") (pinfunction "1_P$1") (pintype "passive"))
      (node (ref "C803") (pin "P$1") (pinfunction "1_P$1") (pintype "passive"))
      (node (ref "C804") (pin "P$1") (pinfunction "1_P$1") (pintype "passive"))
      (node (ref "C901") (pin "P$1") (pinfunction "1_P$1") (pintype "passive"))
      (node (ref "C903") (pin "P$1") (pinfunction "1_P$1") (pintype "passive"))
      (node (ref "D701") (pin "C") (pinfunction "C_C") (pintype "passive"))
      (node (ref "J702") (pin "1") (pinfunction "1_1") (pintype "passive"))
      (node (ref "JX802") (pin "1") (pinfunction "S_1") (pintype "passive"))
      (node (ref "U1002") (pin "7") (pinfunction "VOUT2_7") (pintype "bidirectional"))
      (node (ref "U801") (pin "24") (pinfunction "VDD_1_24") (pintype "power_in"))
      (node (ref "U801") (pin "36") (pinfunction "VDD_2_36") (pintype "power_in"))
      (node (ref "U801") (pin "48") (pinfunction "VDD_3_48") (pintype "power_in"))
      (node (ref "U801") (pin "9") (pinfunction "VDDA_9") (pintype "power_in"))
      (node (ref "U902") (pin "10") (pinfunction "OE_10") (pintype "input"))
      (node (ref "U902") (pin "19") (pinfunction "VCCB_19") (pintype "input"))
      (node (ref "U902") (pin "2") (pinfunction "VCCA_2") (pintype "input"))
      (node (ref "U903") (pin "8") (pinfunction "VCC_8") (pintype "power_in"))
    )
    (net (code "64") (name "IO-VDD_5V5") (class "Default")
      (node (ref "C1001") (pin "P$1") (pinfunction "1_P$1") (pintype "passive"))
      (node (ref "C1005") (pin "P$1") (pinfunction "1_P$1") (pintype "passive"))
      (node (ref "D1001") (pin "3") (pinfunction "CC_3") (pintype "passive"))
      (node (ref "J901") (pin "2") (pinfunction "S_2") (pintype "passive"))
      (node (ref "LED702") (pin "A") (pinfunction "A_A") (pintype "passive"))
      (node (ref "LED703") (pin "A") (pinfunction "A_A") (pintype "passive"))
      (node (ref "LED705") (pin "A") (pinfunction "A_A") (pintype "passive"))
      (node (ref "U1002") (pin "1") (pinfunction "VIN_1") (pintype "bidirectional"))
      (node (ref "U1002") (pin "4") (pinfunction "EN2_4") (pintype "bidirectional"))
    )
    (net (code "65") (name "IO-~{RESET}") (class "Default")
      (node (ref "C801") (pin "P$2") (pinfunction "2_P$2") (pintype "passive"))
      (node (ref "S801") (pin "A1") (pinfunction "1_A1") (pintype "passive"))
      (node (ref "U1002") (pin "3") (pinfunction "POR2_3") (pintype "bidirectional"))
      (node (ref "U801") (pin "7") (pinfunction "NRST_7") (pintype "input"))
    )
    (net (code "66") (name "IO-~{VDD_SERVO_IN_FAULT}") (class "Default")
      (node (ref "U1001") (pin "4") (pinfunction "~{FAULT}_4") (pintype "bidirectional"))
      (node (ref "U801") (pin "38") (pinfunction "PA15_38") (pintype "bidirectional"))
    )
    (net (code "67") (name "MAG_DRDY") (class "Default")
      (node (ref "U101") (pin "36") (pinfunction "PB1_36") (pintype "bidirectional"))
      (node (ref "U504") (pin "9") (pinfunction "INT2_9") (pintype "bidirectional"))
      (node (ref "X503") (pin "4") (pinfunction "S_4") (pintype "passive"))
    )
    (net (code "68") (name "MPU_DRDY") (class "Default")
      (node (ref "U101") (pin "62") (pinfunction "PD15_62") (pintype "bidirectional"))
      (node (ref "U505") (pin "12") (pinfunction "INT_12") (pintype "bidirectional"))
    )
    (net (code "69") (name "Net-(C102-1)") (class "Default")
      (node (ref "C102") (pin "P$1") (pinfunction "1_P$1") (pintype "passive"))
      (node (ref "U101") (pin "12") (pinfunction "OSC_IN_12") (pintype "input"))
      (node (ref "X101") (pin "3") (pinfunction "3_3") (pintype "bidirectional"))
    )
    (net (code "70") (name "Net-(C103-2)") (class "Default")
      (node (ref "C103") (pin "P$2") (pinfunction "2_P$2") (pintype "passive"))
      (node (ref "U101") (pin "13") (pinfunction "OSC_OUT_13") (pintype "output"))
      (node (ref "X101") (pin "1") (pinfunction "1_1") (pintype "bidirectional"))
    )
    (net (code "71") (name "Net-(C504-1)") (class "Default")
      (node (ref "C504") (pin "P$1") (pinfunction "1_P$1") (pintype "passive"))
      (node (ref "U501") (pin "14") (pinfunction "PLLFILT_14") (pintype "bidirectional"))
    )
    (net (code "72") (name "Net-(C505-1)") (class "Default")
      (node (ref "C505") (pin "P$1") (pinfunction "1_P$1") (pintype "passive"))
      (node (ref "U502") (pin "14") (pinfunction "CAP_14") (pintype "bidirectional"))
    )
    (net (code "73") (name "Net-(C509-1)") (class "Default")
      (node (ref "C509") (pin "P$1") (pinfunction "1_P$1") (pintype "passive"))
      (node (ref "U504") (pin "15") (pinfunction "C1_15") (pintype "bidirectional"))
    )
    (net (code "74") (name "Net-(C510-1)") (class "Default")
      (node (ref "C510") (pin "P$1") (pinfunction "1_P$1") (pintype "passive"))
      (node (ref "U504") (pin "2") (pinfunction "SETC_2") (pintype "bidirectional"))
    )
    (net (code "75") (name "Net-(C510-2)") (class "Default")
      (node (ref "C510") (pin "P$2") (pinfunction "2_P$2") (pintype "passive"))
      (node (ref "U504") (pin "3") (pinfunction "SETP_3") (pintype "bidirectional"))
    )
    (net (code "76") (name "Net-(C512-1)") (class "Default")
      (node (ref "C512") (pin "P$1") (pinfunction "1_P$1") (pintype "passive"))
      (node (ref "U505") (pin "10") (pinfunction "REGOUT_10") (pintype "bidirectional"))
    )
    (net (code "77") (name "Net-(C515-1)") (class "Default")
      (node (ref "C515") (pin "P$1") (pinfunction "1_P$1") (pintype "passive"))
      (node (ref "U505") (pin "20") (pinfunction "CPOUT_20") (pintype "bidirectional"))
    )
    (net (code "78") (name "Net-(C601-1)") (class "Default")
      (node (ref "C601") (pin "P$1") (pinfunction "1_P$1") (pintype "passive"))
      (node (ref "C615") (pin "P$1") (pinfunction "1_P$1") (pintype "passive"))
      (node (ref "L603") (pin "P$2") (pinfunction "P$2_P$2") (pintype "bidirectional"))
      (node (ref "R603") (pin "P$1") (pinfunction "1_P$1") (pintype "passive"))
      (node (ref "U603") (pin "1") (pinfunction "VIN_1") (pintype "bidirectional"))
      (node (ref "U603") (pin "4") (pinfunction "EN2_4") (pintype "bidirectional"))
    )
    (net (code "79") (name "Net-(C602-2)") (class "Default")
      (node (ref "C602") (pin "P$2") (pinfunction "2_P$2") (pintype "passive"))
      (node (ref "U603") (pin "6") (pinfunction "CSET_6") (pintype "bidirectional"))
    )
    (net (code "80") (name "Net-(C611-1)") (class "Default")
      (node (ref "C611") (pin "P$1") (pinfunction "1_P$1") (pintype "passive"))
      (node (ref "U101") (pin "49") (pinfunction "VCAP_1_49") (pintype "power_in"))
    )
    (net (code "81") (name "Net-(C613-1)") (class "Default")
      (node (ref "C613") (pin "P$1") (pinfunction "1_P$1") (pintype "passive"))
      (node (ref "U101") (pin "73") (pinfunction "VCAP_2_73") (pintype "power_in"))
    )
    (net (code "82") (name "Net-(C703-1)") (class "Default")
      (node (ref "C703") (pin "P$1") (pinfunction "1_P$1") (pintype "passive"))
      (node (ref "J701") (pin "1") (pinfunction "1_1") (pintype "passive"))
      (node (ref "R703") (pin "P$1") (pinfunction "1_P$1") (pintype "passive"))
      (node (ref "U702") (pin "1") (pinfunction "OUT_1") (pintype "output"))
    )
    (net (code "83") (name "Net-(C704-1)") (class "Default")
      (node (ref "C704") (pin "P$1") (pinfunction "1_P$1") (pintype "passive"))
      (node (ref "R705") (pin "P$1") (pinfunction "1_P$1") (pintype "passive"))
      (node (ref "U702") (pin "6") (pinfunction "VCC_6") (pintype "bidirectional"))
    )
    (net (code "84") (name "Net-(C805-1)") (class "Default")
      (node (ref "C805") (pin "P$1") (pinfunction "1_P$1") (pintype "passive"))
      (node (ref "U801") (pin "5") (pinfunction "PD0/OSC<=_5") (pintype "bidirectional"))
      (node (ref "X801") (pin "3") (pinfunction "3_3") (pintype "bidirectional"))
    )
    (net (code "85") (name "Net-(C806-2)") (class "Default")
      (node (ref "C806") (pin "P$2") (pinfunction "2_P$2") (pintype "passive"))
      (node (ref "U801") (pin "6") (pinfunction "PD1/OSC=>_6") (pintype "bidirectional"))
      (node (ref "X801") (pin "1") (pinfunction "1_1") (pintype "bidirectional"))
    )
    (net (code "86") (name "Net-(C1002-1)") (class "Default")
      (node (ref "C1002") (pin "P$1") (pinfunction "1_P$1") (pintype "passive"))
      (node (ref "U1002") (pin "6") (pinfunction "CSET_6") (pintype "bidirectional"))
    )
    (net (code "87") (name "Net-(C1105-1)") (class "Default")
      (node (ref "C1105") (pin "P$1") (pinfunction "1_P$1") (pintype "passive"))
      (node (ref "U1101") (pin "P$18") (pinfunction "VS1_P$18") (pintype "bidirectional"))
      (node (ref "U1102") (pin "P$1") (pinfunction "S_P$1") (pintype "passive"))
      (node (ref "U1102") (pin "P$3") (pinfunction "S_P$3") (pintype "passive"))
    )
    (net (code "88") (name "Net-(C1106-1)") (class "Default")
      (node (ref "C1106") (pin "P$1") (pinfunction "1_P$1") (pintype "passive"))
      (node (ref "U1101") (pin "P$16") (pinfunction "VS2_P$16") (pintype "bidirectional"))
      (node (ref "U1103") (pin "P$1") (pinfunction "S_P$1") (pintype "passive"))
      (node (ref "U1103") (pin "P$3") (pinfunction "S_P$3") (pintype "passive"))
    )
    (net (code "89") (name "Net-(C1107-1)") (class "Default")
      (node (ref "C1107") (pin "P$1") (pinfunction "1_P$1") (pintype "passive"))
      (node (ref "U1101") (pin "P$14") (pinfunction "VS3_P$14") (pintype "bidirectional"))
      (node (ref "U1104") (pin "P$1") (pinfunction "S_P$1") (pintype "passive"))
      (node (ref "U1104") (pin "P$3") (pinfunction "S_P$3") (pintype "passive"))
    )
    (net (code "90") (name "Net-(C1108-1)") (class "Default")
      (node (ref "C1108") (pin "P$1") (pinfunction "1_P$1") (pintype "passive"))
      (node (ref "R1105") (pin "P$2") (pinfunction "2_P$2") (pintype "passive"))
      (node (ref "R1106") (pin "P$1") (pinfunction "1_P$1") (pintype "passive"))
      (node (ref "U1101") (pin "P$1") (pinfunction "UV1_P$1") (pintype "bidirectional"))
    )
    (net (code "91") (name "Net-(C1109-1)") (class "Default")
      (node (ref "C1109") (pin "P$1") (pinfunction "1_P$1") (pintype "passive"))
      (node (ref "R1109") (pin "P$2") (pinfunction "2_P$2") (pintype "passive"))
      (node (ref "R1110") (pin "P$1") (pinfunction "1_P$1") (pintype "passive"))
      (node (ref "U1101") (pin "P$3") (pinfunction "UV2_P$3") (pintype "bidirectional"))
    )
    (net (code "92") (name "Net-(C1110-1)") (class "Default")
      (node (ref "C1110") (pin "P$1") (pinfunction "1_P$1") (pintype "passive"))
      (node (ref "R1112") (pin "P$2") (pinfunction "2_P$2") (pintype "passive"))
      (node (ref "R1113") (pin "P$1") (pinfunction "1_P$1") (pintype "passive"))
      (node (ref "U1101") (pin "P$5") (pinfunction "UV3_P$5") (pintype "bidirectional"))
    )
    (net (code "93") (name "Net-(D201-PadC)") (class "Default")
      (node (ref "D201") (pin "C") (pinfunction "C_C") (pintype "passive"))
      (node (ref "J201") (pin "1") (pinfunction "1_1") (pintype "passive"))
      (node (ref "L201") (pin "P$2") (pinfunction "P$2_P$2") (pintype "bidirectional"))
    )
    (net (code "94") (name "Net-(D202-PadC)") (class "Default")
      (node (ref "D202") (pin "C") (pinfunction "C_C") (pintype "passive"))
      (node (ref "J202") (pin "1") (pinfunction "1_1") (pintype "passive"))
      (node (ref "L202") (pin "P$2") (pinfunction "P$2_P$2") (pintype "bidirectional"))
    )
    (net (code "95") (name "Net-(D203-PadC)") (class "Default")
      (node (ref "D203") (pin "C") (pinfunction "C_C") (pintype "passive"))
      (node (ref "J203") (pin "1") (pinfunction "1_1") (pintype "passive"))
      (node (ref "J204") (pin "1") (pinfunction "1_1") (pintype "passive"))
      (node (ref "L203") (pin "P$2") (pinfunction "P$2_P$2") (pintype "bidirectional"))
    )
    (net (code "96") (name "Net-(D401-PadC)") (class "Default")
      (node (ref "D401") (pin "C") (pinfunction "C_C") (pintype "passive"))
      (node (ref "J401") (pin "1") (pinfunction "1_1") (pintype "passive"))
      (node (ref "J402") (pin "1") (pinfunction "1_1") (pintype "passive"))
      (node (ref "L401") (pin "P$2") (pinfunction "P$2_P$2") (pintype "bidirectional"))
    )
    (net (code "97") (name "Net-(D402-PadC)") (class "Default")
      (node (ref "D402") (pin "C") (pinfunction "C_C") (pintype "passive"))
      (node (ref "J403") (pin "1") (pinfunction "1_1") (pintype "passive"))
      (node (ref "L402") (pin "P$2") (pinfunction "P$2_P$2") (pintype "bidirectional"))
    )
    (net (code "98") (name "Net-(D403-PadC)") (class "Default")
      (node (ref "D403") (pin "C") (pinfunction "C_C") (pintype "passive"))
      (node (ref "J404") (pin "1") (pinfunction "1_1") (pintype "passive"))
      (node (ref "L404") (pin "P$2") (pinfunction "P$2_P$2") (pintype "bidirectional"))
    )
    (net (code "99") (name "Net-(D404-PadC)") (class "Default")
      (node (ref "D404") (pin "C") (pinfunction "C_C") (pintype "passive"))
      (node (ref "J405") (pin "1") (pinfunction "1_1") (pintype "passive"))
      (node (ref "L403") (pin "P$2") (pinfunction "P$2_P$2") (pintype "bidirectional"))
    )
    (net (code "100") (name "Net-(D904-C)") (class "Default")
      (node (ref "D903") (pin "C") (pinfunction "C_C") (pintype "passive"))
      (node (ref "D904") (pin "CATHODE") (pinfunction "C_CATHODE") (pintype "passive"))
      (node (ref "L901") (pin "P$1") (pinfunction "P$1_P$1") (pintype "bidirectional"))
    )
    (net (code "101") (name "Net-(D1001-A1)") (class "Default")
      (node (ref "D1001") (pin "1") (pinfunction "A1_1") (pintype "passive"))
      (node (ref "F1001") (pin "2") (pinfunction "2_2") (pintype "bidirectional"))
    )
    (net (code "102") (name "Net-(D1001-A2)") (class "Default")
      (node (ref "D1001") (pin "2") (pinfunction "A2_2") (pintype "passive"))
      (node (ref "U1001") (pin "8") (pinfunction "OUT_8") (pintype "bidirectional"))
    )
    (net (code "103") (name "Net-(J301-2)") (class "Default")
      (node (ref "J301") (pin "D-") (pinfunction "2_D-") (pintype "bidirectional"))
      (node (ref "J302") (pin "3") (pinfunction "3_3") (pintype "passive"))
      (node (ref "U302") (pin "1") (pinfunction "D1I_1") (pintype "bidirectional"))
    )
    (net (code "104") (name "Net-(J301-3)") (class "Default")
      (node (ref "J301") (pin "D+") (pinfunction "3_D+") (pintype "bidirectional"))
      (node (ref "J302") (pin "2") (pinfunction "2_2") (pintype "passive"))
      (node (ref "U302") (pin "3") (pinfunction "D2I_3") (pintype "bidirectional"))
    )
    (net (code "105") (name "Net-(J901A-S)") (class "Default")
      (node (ref "J901") (pin "1") (pinfunction "S_1") (pintype "passive"))
      (node (ref "R909") (pin "P$2") (pinfunction "2_P$2") (pintype "passive"))
    )
    (net (code "106") (name "Net-(J901B-S)") (class "Default")
      (node (ref "J901") (pin "10") (pinfunction "S_10") (pintype "passive"))
      (node (ref "R914") (pin "P$2") (pinfunction "2_P$2") (pintype "passive"))
    )
    (net (code "107") (name "Net-(J901C-S)") (class "Default")
      (node (ref "J901") (pin "13") (pinfunction "S_13") (pintype "passive"))
      (node (ref "R906") (pin "P$2") (pinfunction "2_P$2") (pintype "passive"))
    )
    (net (code "108") (name "Net-(J901D-S)") (class "Default")
      (node (ref "J901") (pin "16") (pinfunction "S_16") (pintype "passive"))
      (node (ref "R915") (pin "P$2") (pinfunction "2_P$2") (pintype "passive"))
    )
    (net (code "109") (name "Net-(J901E-S)") (class "Default")
      (node (ref "J901") (pin "19") (pinfunction "S_19") (pintype "passive"))
      (node (ref "R907") (pin "P$2") (pinfunction "2_P$2") (pintype "passive"))
    )
    (net (code "110") (name "Net-(J901G-S)") (class "Default")
      (node (ref "J901") (pin "22") (pinfunction "S_22") (pintype "passive"))
      (node (ref "R916") (pin "P$2") (pinfunction "2_P$2") (pintype "passive"))
    )
    (net (code "111") (name "Net-(J901H-S)") (class "Default")
      (node (ref "J901") (pin "25") (pinfunction "S_25") (pintype "passive"))
      (node (ref "R908") (pin "P$2") (pinfunction "2_P$2") (pintype "passive"))
    )
    (net (code "112") (name "Net-(J901I-S)") (class "Default")
      (node (ref "J901") (pin "28") (pinfunction "S_28") (pintype "passive"))
      (node (ref "R917") (pin "P$2") (pinfunction "2_P$2") (pintype "passive"))
    )
    (net (code "113") (name "Net-(J901J-S)") (class "Default")
      (node (ref "J901") (pin "31") (pinfunction "S_31") (pintype "passive"))
      (node (ref "R902") (pin "P$2") (pinfunction "2_P$2") (pintype "passive"))
    )
    (net (code "114") (name "Net-(J901K-S)") (class "Default")
      (node (ref "J901") (pin "34") (pinfunction "S_34") (pintype "passive"))
      (node (ref "R911") (pin "P$2") (pinfunction "2_P$2") (pintype "passive"))
    )
    (net (code "115") (name "Net-(J901L-S)") (class "Default")
      (node (ref "J901") (pin "37") (pinfunction "S_37") (pintype "passive"))
      (node (ref "R903") (pin "P$2") (pinfunction "2_P$2") (pintype "passive"))
    )
    (net (code "116") (name "Net-(J901M-S)") (class "Default")
      (node (ref "J901") (pin "4") (pinfunction "S_4") (pintype "passive"))
      (node (ref "R910") (pin "P$2") (pinfunction "2_P$2") (pintype "passive"))
    )
    (net (code "117") (name "Net-(J901N-S)") (class "Default")
      (node (ref "J901") (pin "40") (pinfunction "S_40") (pintype "passive"))
      (node (ref "R912") (pin "P$2") (pinfunction "2_P$2") (pintype "passive"))
    )
    (net (code "118") (name "Net-(J901O-S)") (class "Default")
      (node (ref "J901") (pin "43") (pinfunction "S_43") (pintype "passive"))
      (node (ref "R904") (pin "P$2") (pinfunction "2_P$2") (pintype "passive"))
    )
    (net (code "119") (name "Net-(J901P-S)") (class "Default")
      (node (ref "J901") (pin "46") (pinfunction "S_46") (pintype "passive"))
      (node (ref "R913") (pin "P$2") (pinfunction "2_P$2") (pintype "passive"))
    )
    (net (code "120") (name "Net-(J901Q-S)") (class "Default")
      (node (ref "J901") (pin "7") (pinfunction "S_7") (pintype "passive"))
      (node (ref "R905") (pin "P$2") (pinfunction "2_P$2") (pintype "passive"))
    )
    (net (code "121") (name "Net-(L701-2)") (class "Default")
      (node (ref "L701") (pin "P$2") (pinfunction "2_P$2") (pintype "passive"))
      (node (ref "U702") (pin "5") (pinfunction "SW_5") (pintype "passive"))
    )
    (net (code "122") (name "Net-(Q601-PadC)") (class "Default")
      (node (ref "Q601") (pin "C") (pinfunction "C_C") (pintype "passive"))
      (node (ref "R621") (pin "2") (pinfunction "2_2") (pintype "passive"))
    )
    (net (code "123") (name "Net-(R101-1)") (class "Default")
      (node (ref "R101") (pin "P$1") (pinfunction "1_P$1") (pintype "passive"))
      (node (ref "U101") (pin "69") (pinfunction "PA10_69") (pintype "bidirectional"))
    )
    (net (code "124") (name "Net-(R102-1)") (class "Default")
      (node (ref "R102") (pin "P$1") (pinfunction "1_P$1") (pintype "passive"))
      (node (ref "U101") (pin "37") (pinfunction "PB2_37") (pintype "bidirectional"))
    )
    (net (code "125") (name "Net-(R201-1)") (class "Default")
      (node (ref "R201") (pin "P$1") (pinfunction "1_P$1") (pintype "passive"))
      (node (ref "U201") (pin "20") (pinfunction "B1_20") (pintype "bidirectional"))
    )
    (net (code "126") (name "Net-(R202-1)") (class "Default")
      (node (ref "R202") (pin "P$1") (pinfunction "1_P$1") (pintype "passive"))
      (node (ref "U201") (pin "17") (pinfunction "B3_17") (pintype "bidirectional"))
    )
    (net (code "127") (name "Net-(R203-1)") (class "Default")
      (node (ref "R203") (pin "P$1") (pinfunction "1_P$1") (pintype "passive"))
      (node (ref "U201") (pin "15") (pinfunction "B5_15") (pintype "bidirectional"))
    )
    (net (code "128") (name "Net-(R204-1)") (class "Default")
      (node (ref "R204") (pin "P$1") (pinfunction "1_P$1") (pintype "passive"))
      (node (ref "U201") (pin "13") (pinfunction "B7_13") (pintype "bidirectional"))
    )
    (net (code "129") (name "Net-(R205-1)") (class "Default")
      (node (ref "R205") (pin "P$1") (pinfunction "1_P$1") (pintype "passive"))
      (node (ref "U202") (pin "17") (pinfunction "B3_17") (pintype "bidirectional"))
    )
    (net (code "130") (name "Net-(R206-1)") (class "Default")
      (node (ref "R206") (pin "P$1") (pinfunction "1_P$1") (pintype "passive"))
      (node (ref "U202") (pin "15") (pinfunction "B5_15") (pintype "bidirectional"))
    )
    (net (code "131") (name "Net-(R207-1)") (class "Default")
      (node (ref "R207") (pin "P$1") (pinfunction "1_P$1") (pintype "passive"))
      (node (ref "U202") (pin "13") (pinfunction "B7_13") (pintype "bidirectional"))
    )
    (net (code "132") (name "Net-(R208-1)") (class "Default")
      (node (ref "R208") (pin "P$1") (pinfunction "1_P$1") (pintype "passive"))
      (node (ref "U201") (pin "18") (pinfunction "B2_18") (pintype "bidirectional"))
    )
    (net (code "133") (name "Net-(R209-1)") (class "Default")
      (node (ref "R209") (pin "P$1") (pinfunction "1_P$1") (pintype "passive"))
      (node (ref "U201") (pin "16") (pinfunction "B4_16") (pintype "bidirectional"))
    )
    (net (code "134") (name "Net-(R210-1)") (class "Default")
      (node (ref "R210") (pin "P$1") (pinfunction "1_P$1") (pintype "passive"))
      (node (ref "U201") (pin "14") (pinfunction "B6_14") (pintype "bidirectional"))
    )
    (net (code "135") (name "Net-(R211-1)") (class "Default")
      (node (ref "R211") (pin "P$1") (pinfunction "1_P$1") (pintype "passive"))
      (node (ref "U201") (pin "12") (pinfunction "B8_12") (pintype "bidirectional"))
    )
    (net (code "136") (name "Net-(R212-1)") (class "Default")
      (node (ref "R212") (pin "P$1") (pinfunction "1_P$1") (pintype "passive"))
      (node (ref "U202") (pin "16") (pinfunction "B4_16") (pintype "bidirectional"))
    )
    (net (code "137") (name "Net-(R213-1)") (class "Default")
      (node (ref "R213") (pin "P$1") (pinfunction "1_P$1") (pintype "passive"))
      (node (ref "U202") (pin "14") (pinfunction "B6_14") (pintype "bidirectional"))
    )
    (net (code "138") (name "Net-(R214-1)") (class "Default")
      (node (ref "R214") (pin "P$1") (pinfunction "1_P$1") (pintype "passive"))
      (node (ref "U202") (pin "12") (pinfunction "B8_12") (pintype "bidirectional"))
    )
    (net (code "139") (name "Net-(R215-2)") (class "Default")
      (node (ref "J203") (pin "4") (pinfunction "4_4") (pintype "passive"))
      (node (ref "R215") (pin "P$2") (pinfunction "2_P$2") (pintype "passive"))
    )
    (net (code "140") (name "Net-(R216-2)") (class "Default")
      (node (ref "J203") (pin "5") (pinfunction "5_5") (pintype "passive"))
      (node (ref "R216") (pin "P$2") (pinfunction "2_P$2") (pintype "passive"))
    )
    (net (code "141") (name "Net-(R404-2)") (class "Default")
      (node (ref "J401") (pin "2") (pinfunction "2_2") (pintype "passive"))
      (node (ref "R404") (pin "P$2") (pinfunction "2_P$2") (pintype "passive"))
    )
    (net (code "142") (name "Net-(R405-2)") (class "Default")
      (node (ref "J401") (pin "3") (pinfunction "3_3") (pintype "passive"))
      (node (ref "R405") (pin "P$2") (pinfunction "2_P$2") (pintype "passive"))
    )
    (net (code "143") (name "Net-(R407-2)") (class "Default")
      (node (ref "J404") (pin "2") (pinfunction "2_2") (pintype "passive"))
      (node (ref "R407") (pin "P$2") (pinfunction "2_P$2") (pintype "passive"))
    )
    (net (code "144") (name "Net-(R408-2)") (class "Default")
      (node (ref "J404") (pin "4") (pinfunction "4_4") (pintype "passive"))
      (node (ref "R408") (pin "P$2") (pinfunction "2_P$2") (pintype "passive"))
    )
    (net (code "145") (name "Net-(R608-2)") (class "Default")
      (node (ref "D602") (pin "C") (pinfunction "C_C") (pintype "passive"))
      (node (ref "R608") (pin "P$2") (pinfunction "2_P$2") (pintype "passive"))
    )
    (net (code "146") (name "Net-(R616-1)") (class "Default")
      (node (ref "R616") (pin "P$1") (pinfunction "1_P$1") (pintype "passive"))
      (node (ref "U602") (pin "7") (pinfunction "ILIM_7") (pintype "bidirectional"))
    )
    (net (code "147") (name "Net-(R617-1)") (class "Default")
      (node (ref "R617") (pin "P$1") (pinfunction "1_P$1") (pintype "passive"))
      (node (ref "U601") (pin "7") (pinfunction "ILIM_7") (pintype "bidirectional"))
    )
    (net (code "148") (name "Net-(R620-1)") (class "Default")
      (node (ref "Q601") (pin "B") (pinfunction "B_B") (pintype "passive"))
      (node (ref "R620") (pin "P$1") (pinfunction "1_P$1") (pintype "passive"))
    )
    (net (code "149") (name "Net-(R701-1)") (class "Default")
      (node (ref "R701") (pin "P$1") (pinfunction "1_P$1") (pintype "passive"))
      (node (ref "U702") (pin "7") (pinfunction "+IN_7") (pintype "input"))
    )
    (net (code "150") (name "Net-(R702-1)") (class "Default")
      (node (ref "R702") (pin "P$1") (pinfunction "1_P$1") (pintype "passive"))
      (node (ref "R703") (pin "P$2") (pinfunction "2_P$2") (pintype "passive"))
      (node (ref "U702") (pin "8") (pinfunction "-IN_8") (pintype "input"))
    )
    (net (code "151") (name "Net-(R704-2)") (class "Default")
      (node (ref "R704") (pin "P$2") (pinfunction "2_P$2") (pintype "passive"))
      (node (ref "U701") (pin "6") (pinfunction "REXT_6") (pintype "bidirectional"))
    )
    (net (code "152") (name "Net-(R705-2)") (class "Default")
      (node (ref "R705") (pin "P$2") (pinfunction "2_P$2") (pintype "passive"))
      (node (ref "R706") (pin "P$1") (pinfunction "1_P$1") (pintype "passive"))
      (node (ref "U702") (pin "2") (pinfunction "FB_2") (pintype "bidirectional"))
    )
    (net (code "153") (name "Net-(R707-2)") (class "Default")
      (node (ref "R707") (pin "P$2") (pinfunction "2_P$2") (pintype "passive"))
      (node (ref "R735") (pin "P$1") (pinfunction "1_P$1") (pintype "passive"))
    )
    (net (code "154") (name "Net-(R708-2)") (class "Default")
      (node (ref "LED702") (pin "C") (pinfunction "C_C") (pintype "passive"))
      (node (ref "R708") (pin "P$2") (pinfunction "2_P$2") (pintype "passive"))
    )
    (net (code "155") (name "Net-(R709-2)") (class "Default")
      (node (ref "R709") (pin "P$2") (pinfunction "2_P$2") (pintype "passive"))
      (node (ref "R736") (pin "P$1") (pinfunction "1_P$1") (pintype "passive"))
    )
    (net (code "156") (name "Net-(R710-1)") (class "Default")
      (node (ref "J702") (pin "2") (pinfunction "2_2") (pintype "passive"))
      (node (ref "R710") (pin "P$1") (pinfunction "1_P$1") (pintype "passive"))
    )
    (net (code "157") (name "Net-(R711-2)") (class "Default")
      (node (ref "LED704") (pin "C") (pinfunction "C_C") (pintype "passive"))
      (node (ref "R711") (pin "P$2") (pinfunction "2_P$2") (pintype "passive"))
    )
    (net (code "158") (name "Net-(R712-2)") (class "Default")
      (node (ref "LED705") (pin "C") (pinfunction "C_C") (pintype "passive"))
      (node (ref "R712") (pin "P$2") (pinfunction "2_P$2") (pintype "passive"))
    )
    (net (code "159") (name "Net-(R735-2)") (class "Default")
      (node (ref "LED701") (pin "C") (pinfunction "C_C") (pintype "passive"))
      (node (ref "R735") (pin "P$2") (pinfunction "2_P$2") (pintype "passive"))
    )
    (net (code "160") (name "Net-(R736-2)") (class "Default")
      (node (ref "LED703") (pin "C") (pinfunction "C_C") (pintype "passive"))
      (node (ref "R736") (pin "P$2") (pinfunction "2_P$2") (pintype "passive"))
    )
    (net (code "161") (name "Net-(R802-1)") (class "Default")
      (node (ref "R802") (pin "P$1") (pinfunction "1_P$1") (pintype "passive"))
      (node (ref "U801") (pin "20") (pinfunction "PB2_20") (pintype "bidirectional"))
    )
    (net (code "162") (name "Net-(R803-1)") (class "Default")
      (node (ref "R803") (pin "P$1") (pinfunction "1_P$1") (pintype "passive"))
      (node (ref "U801") (pin "12") (pinfunction "PA2_12") (pintype "bidirectional"))
    )
    (net (code "163") (name "Net-(R804-1)") (class "Default")
      (node (ref "R804") (pin "P$1") (pinfunction "1_P$1") (pintype "passive"))
      (node (ref "U801") (pin "13") (pinfunction "PA3_13") (pintype "bidirectional"))
    )
    (net (code "164") (name "Net-(R901-2)") (class "Default")
      (node (ref "D902") (pin "C") (pinfunction "C_C") (pintype "passive"))
      (node (ref "R901") (pin "P$2") (pinfunction "2_P$2") (pintype "passive"))
      (node (ref "R910") (pin "P$1") (pinfunction "1_P$1") (pintype "passive"))
      (node (ref "U903") (pin "3") (pinfunction "2Y_3") (pintype "bidirectional"))
    )
    (net (code "165") (name "Net-(R902-1)") (class "Default")
      (node (ref "R902") (pin "P$1") (pinfunction "1_P$1") (pintype "passive"))
      (node (ref "U901") (pin "20") (pinfunction "B1_20") (pintype "bidirectional"))
    )
    (net (code "166") (name "Net-(R903-1)") (class "Default")
      (node (ref "R903") (pin "P$1") (pinfunction "1_P$1") (pintype "passive"))
      (node (ref "U901") (pin "17") (pinfunction "B3_17") (pintype "bidirectional"))
    )
    (net (code "167") (name "Net-(R904-1)") (class "Default")
      (node (ref "R904") (pin "P$1") (pinfunction "1_P$1") (pintype "passive"))
      (node (ref "U901") (pin "15") (pinfunction "B5_15") (pintype "bidirectional"))
    )
    (net (code "168") (name "Net-(R905-1)") (class "Default")
      (node (ref "R905") (pin "P$1") (pinfunction "1_P$1") (pintype "passive"))
      (node (ref "U902") (pin "20") (pinfunction "B1_20") (pintype "bidirectional"))
    )
    (net (code "169") (name "Net-(R906-1)") (class "Default")
      (node (ref "R906") (pin "P$1") (pinfunction "1_P$1") (pintype "passive"))
      (node (ref "U902") (pin "17") (pinfunction "B3_17") (pintype "bidirectional"))
    )
    (net (code "170") (name "Net-(R907-1)") (class "Default")
      (node (ref "R907") (pin "P$1") (pinfunction "1_P$1") (pintype "passive"))
      (node (ref "U902") (pin "15") (pinfunction "B5_15") (pintype "bidirectional"))
    )
    (net (code "171") (name "Net-(R908-1)") (class "Default")
      (node (ref "R908") (pin "P$1") (pinfunction "1_P$1") (pintype "passive"))
      (node (ref "U902") (pin "13") (pinfunction "B7_13") (pintype "bidirectional"))
    )
    (net (code "172") (name "Net-(R911-1)") (class "Default")
      (node (ref "R911") (pin "P$1") (pinfunction "1_P$1") (pintype "passive"))
      (node (ref "U901") (pin "18") (pinfunction "B2_18") (pintype "bidirectional"))
    )
    (net (code "173") (name "Net-(R912-1)") (class "Default")
      (node (ref "R912") (pin "P$1") (pinfunction "1_P$1") (pintype "passive"))
      (node (ref "U901") (pin "16") (pinfunction "B4_16") (pintype "bidirectional"))
    )
    (net (code "174") (name "Net-(R913-1)") (class "Default")
      (node (ref "R913") (pin "P$1") (pinfunction "1_P$1") (pintype "passive"))
      (node (ref "U901") (pin "14") (pinfunction "B6_14") (pintype "bidirectional"))
    )
    (net (code "175") (name "Net-(R914-1)") (class "Default")
      (node (ref "R914") (pin "P$1") (pinfunction "1_P$1") (pintype "passive"))
      (node (ref "U902") (pin "18") (pinfunction "B2_18") (pintype "bidirectional"))
    )
    (net (code "176") (name "Net-(R915-1)") (class "Default")
      (node (ref "R915") (pin "P$1") (pinfunction "1_P$1") (pintype "passive"))
      (node (ref "U902") (pin "16") (pinfunction "B4_16") (pintype "bidirectional"))
    )
    (net (code "177") (name "Net-(R916-1)") (class "Default")
      (node (ref "R916") (pin "P$1") (pinfunction "1_P$1") (pintype "passive"))
      (node (ref "U902") (pin "14") (pinfunction "B6_14") (pintype "bidirectional"))
    )
    (net (code "178") (name "Net-(R917-1)") (class "Default")
      (node (ref "R917") (pin "P$1") (pinfunction "1_P$1") (pintype "passive"))
      (node (ref "U902") (pin "12") (pinfunction "B8_12") (pintype "bidirectional"))
    )
    (net (code "179") (name "Net-(R918-2)") (class "Default")
      (node (ref "R918") (pin "P$2") (pinfunction "2_P$2") (pintype "passive"))
      (node (ref "R922") (pin "P$1") (pinfunction "1_P$1") (pintype "passive"))
    )
    (net (code "180") (name "Net-(R1001-2)") (class "Default")
      (node (ref "R1001") (pin "P$2") (pinfunction "2_P$2") (pintype "passive"))
      (node (ref "U1001") (pin "7") (pinfunction "ILIM_7") (pintype "bidirectional"))
    )
    (net (code "181") (name "Net-(R1101-2)") (class "Default")
      (node (ref "L1101") (pin "P$2") (pinfunction "P$2_P$2") (pintype "bidirectional"))
      (node (ref "R1101") (pin "P$2") (pinfunction "2_P$2") (pintype "passive"))
    )
    (net (code "182") (name "Net-(R1102-2)") (class "Default")
      (node (ref "L1102") (pin "P$2") (pinfunction "P$2_P$2") (pintype "bidirectional"))
      (node (ref "R1102") (pin "P$2") (pinfunction "2_P$2") (pintype "passive"))
    )
    (net (code "183") (name "Net-(R1103-1)") (class "Default")
      (node (ref "J601") (pin "4") (pinfunction "4_4") (pintype "passive"))
      (node (ref "L1102") (pin "P$1") (pinfunction "P$1_P$1") (pintype "bidirectional"))
      (node (ref "R1103") (pin "P$1") (pinfunction "1_P$1") (pintype "passive"))
    )
    (net (code "184") (name "Net-(R1104-1)") (class "Default")
      (node (ref "J601") (pin "3") (pinfunction "3_3") (pintype "passive"))
      (node (ref "L1101") (pin "P$1") (pinfunction "P$1_P$1") (pintype "bidirectional"))
      (node (ref "R1104") (pin "P$1") (pinfunction "1_P$1") (pintype "passive"))
    )
    (net (code "185") (name "Net-(R1106-2)") (class "Default")
      (node (ref "R1106") (pin "P$2") (pinfunction "2_P$2") (pintype "passive"))
      (node (ref "R1107") (pin "P$1") (pinfunction "1_P$1") (pintype "passive"))
      (node (ref "U1101") (pin "P$2") (pinfunction "OV1_P$2") (pintype "bidirectional"))
    )
    (net (code "186") (name "Net-(R1110-2)") (class "Default")
      (node (ref "R1110") (pin "P$2") (pinfunction "2_P$2") (pintype "passive"))
      (node (ref "R1111") (pin "P$1") (pinfunction "1_P$1") (pintype "passive"))
      (node (ref "U1101") (pin "P$4") (pinfunction "OV2_P$4") (pintype "bidirectional"))
    )
    (net (code "187") (name "Net-(R1113-2)") (class "Default")
      (node (ref "R1113") (pin "P$2") (pinfunction "2_P$2") (pintype "passive"))
      (node (ref "R1114") (pin "P$1") (pinfunction "1_P$1") (pintype "passive"))
      (node (ref "U1101") (pin "P$6") (pinfunction "OV3_P$6") (pintype "bidirectional"))
    )
    (net (code "188") (name "Net-(R1115-2)") (class "Default")
      (node (ref "R1115") (pin "P$2") (pinfunction "2_P$2") (pintype "passive"))
      (node (ref "U1101") (pin "P$24") (pinfunction "HYS_P$24") (pintype "bidirectional"))
    )
    (net (code "189") (name "Net-(U701-OUT0)") (class "Default")
      (node (ref "U701") (pin "9") (pinfunction "OUT0_9") (pintype "open_collector"))
      (node (ref "U703") (pin "C1") (pinfunction "C_C1") (pintype "passive"))
    )
    (net (code "190") (name "Net-(U701-OUT1)") (class "Default")
      (node (ref "U701") (pin "8") (pinfunction "OUT1_8") (pintype "open_collector"))
      (node (ref "U703") (pin "C2") (pinfunction "C_C2") (pintype "passive"))
    )
    (net (code "191") (name "Net-(U701-OUT2)") (class "Default")
      (node (ref "U701") (pin "7") (pinfunction "OUT2_7") (pintype "open_collector"))
      (node (ref "U703") (pin "C3") (pinfunction "C_C3") (pintype "passive"))
    )
    (net (code "192") (name "Net-(U1101-G1)") (class "Default")
      (node (ref "U1101") (pin "P$17") (pinfunction "G1_P$17") (pintype "bidirectional"))
      (node (ref "U1102") (pin "P$2") (pinfunction "G_P$2") (pintype "passive"))
      (node (ref "U1102") (pin "P$4") (pinfunction "G_P$4") (pintype "passive"))
    )
    (net (code "193") (name "Net-(U1101-G2)") (class "Default")
      (node (ref "U1101") (pin "P$15") (pinfunction "G2_P$15") (pintype "bidirectional"))
      (node (ref "U1103") (pin "P$2") (pinfunction "G_P$2") (pintype "passive"))
      (node (ref "U1103") (pin "P$4") (pinfunction "G_P$4") (pintype "passive"))
    )
    (net (code "194") (name "Net-(U1101-G3)") (class "Default")
      (node (ref "U1101") (pin "P$13") (pinfunction "G3_P$13") (pintype "bidirectional"))
      (node (ref "U1104") (pin "P$2") (pinfunction "G_P$2") (pintype "passive"))
      (node (ref "U1104") (pin "P$4") (pinfunction "G_P$4") (pintype "passive"))
    )
    (net (code "195") (name "OTG_FS_DM") (class "Default")
      (node (ref "U101") (pin "70") (pinfunction "PA11_70") (pintype "bidirectional"))
      (node (ref "U302") (pin "6") (pinfunction "D1O_6") (pintype "bidirectional"))
    )
    (net (code "196") (name "OTG_FS_DP") (class "Default")
      (node (ref "U101") (pin "71") (pinfunction "PA12_71") (pintype "bidirectional"))
      (node (ref "U302") (pin "4") (pinfunction "D2O_4") (pintype "bidirectional"))
    )
    (net (code "197") (name "PPM_INPUT") (class "Default")
      (node (ref "D901") (pin "C") (pinfunction "C_C") (pintype "passive"))
      (node (ref "R909") (pin "P$1") (pinfunction "1_P$1") (pintype "passive"))
      (node (ref "U801") (pin "29") (pinfunction "PA8_29") (pintype "bidirectional"))
      (node (ref "U903") (pin "2") (pinfunction "1A_2") (pintype "bidirectional"))
    )
    (net (code "198") (name "PRESSURE_SENS") (class "Default")
      (node (ref "C401") (pin "P$1") (pinfunction "1_P$1") (pintype "passive"))
      (node (ref "R403") (pin "P$2") (pinfunction "2_P$2") (pintype "passive"))
      (node (ref "R406") (pin "P$1") (pinfunction "1_P$1") (pintype "passive"))
      (node (ref "U101") (pin "34") (pinfunction "PC5_34") (pintype "bidirectional"))
    )
    (net (code "199") (name "PRESSURE_SENS_IN") (class "Default")
      (node (ref "ADC_PR") (pin "P$1") (pinfunction "P$1_P$1") (pintype "passive"))
      (node (ref "J402") (pin "2") (pinfunction "2_2") (pintype "passive"))
      (node (ref "R406") (pin "P$2") (pinfunction "2_P$2") (pintype "passive"))
    )
    (net (code "200") (name "RSSI_IN") (class "Default")
      (node (ref "R901") (pin "P$1") (pinfunction "1_P$1") (pintype "passive"))
      (node (ref "U801") (pin "15") (pinfunction "PA5_15") (pintype "bidirectional"))
      (node (ref "U801") (pin "33") (pinfunction "PA12_33") (pintype "bidirectional"))
    )
    (net (code "201") (name "SAFETY") (class "Default")
      (node (ref "J702") (pin "3") (pinfunction "3_3") (pintype "passive"))
      (node (ref "R713") (pin "P$1") (pinfunction "1_P$1") (pintype "passive"))
      (node (ref "U801") (pin "41") (pinfunction "PB5_41") (pintype "bidirectional"))
    )
    (net (code "202") (name "SBUS_INPUT") (class "Default")
      (node (ref "U801") (pin "22") (pinfunction "PB11_22") (pintype "bidirectional"))
      (node (ref "U903") (pin "6") (pinfunction "1Y_6") (pintype "bidirectional"))
    )
    (net (code "203") (name "SBUS_OUTPUT") (class "Default")
      (node (ref "U801") (pin "21") (pinfunction "PB10_21") (pintype "bidirectional"))
      (node (ref "U903") (pin "5") (pinfunction "2A_5") (pintype "bidirectional"))
    )
    (net (code "204") (name "SDIO_CK") (class "Default")
      (node (ref "U101") (pin "80") (pinfunction "PC12_80") (pintype "bidirectional"))
      (node (ref "U301") (pin "5") (pinfunction "CLK_5") (pintype "bidirectional"))
    )
    (net (code "205") (name "SDIO_CMD") (class "Default")
      (node (ref "R303") (pin "P$1") (pinfunction "1_P$1") (pintype "passive"))
      (node (ref "U101") (pin "83") (pinfunction "PD2_83") (pintype "bidirectional"))
      (node (ref "U301") (pin "3") (pinfunction "CMD_3") (pintype "bidirectional"))
    )
    (net (code "206") (name "SDIO_D0") (class "Default")
      (node (ref "R304") (pin "P$1") (pinfunction "1_P$1") (pintype "passive"))
      (node (ref "U101") (pin "65") (pinfunction "PC8_65") (pintype "bidirectional"))
      (node (ref "U301") (pin "7") (pinfunction "D0_7") (pintype "bidirectional"))
    )
    (net (code "207") (name "SDIO_D1") (class "Default")
      (node (ref "R305") (pin "P$1") (pinfunction "1_P$1") (pintype "passive"))
      (node (ref "U101") (pin "66") (pinfunction "PC9_66") (pintype "bidirectional"))
      (node (ref "U301") (pin "8") (pinfunction "D1_8") (pintype "bidirectional"))
    )
    (net (code "208") (name "SDIO_D2") (class "Default")
      (node (ref "R301") (pin "P$1") (pinfunction "1_P$1") (pintype "passive"))
      (node (ref "U101") (pin "78") (pinfunction "PC10_78") (pintype "bidirectional"))
      (node (ref "U301") (pin "1") (pinfunction "D2_1") (pintype "bidirectional"))
    )
    (net (code "209") (name "SDIO_D3") (class "Default")
      (node (ref "R302") (pin "P$1") (pinfunction "1_P$1") (pintype "passive"))
      (node (ref "U101") (pin "79") (pinfunction "PC11_79") (pintype "bidirectional"))
      (node (ref "U301") (pin "2") (pinfunction "D3_2") (pintype "bidirectional"))
    )
    (net (code "210") (name "SERIAL1_CTS") (class "Default")
      (node (ref "J201") (pin "4") (pinfunction "4_4") (pintype "passive"))
      (node (ref "R211") (pin "P$2") (pinfunction "2_P$2") (pintype "passive"))
    )
    (net (code "211") (name "SERIAL1_RTS") (class "Default")
      (node (ref "J201") (pin "5") (pinfunction "5_5") (pintype "passive"))
      (node (ref "R204") (pin "P$2") (pinfunction "2_P$2") (pintype "passive"))
    )
    (net (code "212") (name "SERIAL1_RX") (class "Default")
      (node (ref "J201") (pin "3") (pinfunction "3_3") (pintype "passive"))
      (node (ref "R203") (pin "P$2") (pinfunction "2_P$2") (pintype "passive"))
      (node (ref "S1RX") (pin "P$1") (pinfunction "P$1_P$1") (pintype "passive"))
    )
    (net (code "213") (name "SERIAL1_TX") (class "Default")
      (node (ref "J201") (pin "2") (pinfunction "2_2") (pintype "passive"))
      (node (ref "R210") (pin "P$2") (pinfunction "2_P$2") (pintype "passive"))
      (node (ref "S1TX") (pin "P$1") (pinfunction "P$1_P$1") (pintype "passive"))
    )
    (net (code "214") (name "SERIAL2_CTS") (class "Default")
      (node (ref "J202") (pin "4") (pinfunction "4_4") (pintype "passive"))
      (node (ref "R208") (pin "P$2") (pinfunction "2_P$2") (pintype "passive"))
    )
    (net (code "215") (name "SERIAL2_RTS") (class "Default")
      (node (ref "J202") (pin "5") (pinfunction "5_5") (pintype "passive"))
      (node (ref "R201") (pin "P$2") (pinfunction "2_P$2") (pintype "passive"))
    )
    (net (code "216") (name "SERIAL2_RX") (class "Default")
      (node (ref "J202") (pin "3") (pinfunction "3_3") (pintype "passive"))
      (node (ref "R202") (pin "P$2") (pinfunction "2_P$2") (pintype "passive"))
      (node (ref "S2RX") (pin "P$1") (pinfunction "P$1_P$1") (pintype "passive"))
    )
    (net (code "217") (name "SERIAL2_TX") (class "Default")
      (node (ref "J202") (pin "2") (pinfunction "2_2") (pintype "passive"))
      (node (ref "R209") (pin "P$2") (pinfunction "2_P$2") (pintype "passive"))
      (node (ref "S2TX") (pin "P$1") (pinfunction "P$1_P$1") (pintype "passive"))
    )
    (net (code "218") (name "SERIAL3_RX") (class "Default")
      (node (ref "J203") (pin "3") (pinfunction "3_3") (pintype "passive"))
      (node (ref "R207") (pin "P$2") (pinfunction "2_P$2") (pintype "passive"))
      (node (ref "S3RX") (pin "P$1") (pinfunction "P$1_P$1") (pintype "passive"))
    )
    (net (code "219") (name "SERIAL3_TX") (class "Default")
      (node (ref "J203") (pin "2") (pinfunction "2_2") (pintype "passive"))
      (node (ref "R214") (pin "P$2") (pinfunction "2_P$2") (pintype "passive"))
      (node (ref "S3TX") (pin "P$1") (pinfunction "P$1_P$1") (pintype "passive"))
    )
    (net (code "220") (name "SERIAL4_RX") (class "Default")
      (node (ref "J204") (pin "3") (pinfunction "3_3") (pintype "passive"))
      (node (ref "R206") (pin "P$2") (pinfunction "2_P$2") (pintype "passive"))
      (node (ref "S4RX") (pin "P$1") (pinfunction "P$1_P$1") (pintype "passive"))
    )
    (net (code "221") (name "SERIAL4_TX") (class "Default")
      (node (ref "J204") (pin "2") (pinfunction "2_2") (pintype "passive"))
      (node (ref "R213") (pin "P$2") (pinfunction "2_P$2") (pintype "passive"))
      (node (ref "S4TX") (pin "P$1") (pinfunction "P$1_P$1") (pintype "passive"))
    )
    (net (code "222") (name "SERIAL5_RX") (class "Default")
      (node (ref "J204") (pin "5") (pinfunction "5_5") (pintype "passive"))
      (node (ref "R205") (pin "P$2") (pinfunction "2_P$2") (pintype "passive"))
      (node (ref "S5_RX") (pin "P$1") (pinfunction "P$1_P$1") (pintype "passive"))
    )
    (net (code "223") (name "SERIAL5_TX") (class "Default")
      (node (ref "J204") (pin "4") (pinfunction "4_4") (pintype "passive"))
      (node (ref "R212") (pin "P$2") (pinfunction "2_P$2") (pintype "passive"))
      (node (ref "S5_TX") (pin "P$1") (pinfunction "P$1_P$1") (pintype "passive"))
    )
    (net (code "224") (name "SERIAL_FMU_TO_IO") (class "Default")
      (node (ref "R804") (pin "P$2") (pinfunction "2_P$2") (pintype "passive"))
      (node (ref "U101") (pin "63") (pinfunction "PC6_63") (pintype "bidirectional"))
    )
    (net (code "225") (name "SERIAL_IO_TO_FMU") (class "Default")
      (node (ref "R803") (pin "P$2") (pinfunction "2_P$2") (pintype "passive"))
      (node (ref "U101") (pin "64") (pinfunction "PC7_64") (pintype "bidirectional"))
    )
    (net (code "226") (name "SPI_EXT_MISO") (class "Default")
      (node (ref "J403") (pin "3") (pinfunction "3_3") (pintype "passive"))
      (node (ref "U101") (pin "4") (pinfunction "PE5_4") (pintype "bidirectional"))
    )
    (net (code "227") (name "SPI_EXT_MOSI") (class "Default")
      (node (ref "J403") (pin "4") (pinfunction "4_4") (pintype "passive"))
      (node (ref "U101") (pin "5") (pinfunction "PE6_5") (pintype "bidirectional"))
    )
    (net (code "228") (name "SPI_EXT_SCK") (class "Default")
      (node (ref "J403") (pin "2") (pinfunction "2_2") (pintype "passive"))
      (node (ref "U101") (pin "1") (pinfunction "PE2_1") (pintype "bidirectional"))
    )
    (net (code "229") (name "SPI_INT_MISO") (class "Default")
      (node (ref "U101") (pin "31") (pinfunction "PA6_31") (pintype "bidirectional"))
      (node (ref "U501") (pin "4") (pinfunction "SDO/SA0_4") (pintype "bidirectional"))
      (node (ref "U502") (pin "4") (pinfunction "SDO/SA0_4") (pintype "bidirectional"))
      (node (ref "U504") (pin "7") (pinfunction "SDO/SA0_7") (pintype "bidirectional"))
      (node (ref "U505") (pin "9") (pinfunction "AD0/SDO_9") (pintype "bidirectional"))
      (node (ref "U506") (pin "6") (pinfunction "SDO_6") (pintype "bidirectional"))
      (node (ref "X503") (pin "9") (pinfunction "S_9") (pintype "passive"))
    )
    (net (code "230") (name "SPI_INT_MOSI") (class "Default")
      (node (ref "U101") (pin "32") (pinfunction "PA7_32") (pintype "bidirectional"))
      (node (ref "U501") (pin "3") (pinfunction "SDA/SDI/SDO_3") (pintype "bidirectional"))
      (node (ref "U502") (pin "3") (pinfunction "SDA/SDI/SDO_3") (pintype "bidirectional"))
      (node (ref "U504") (pin "6") (pinfunction "SDA/SDI/SDO_6") (pintype "bidirectional"))
      (node (ref "U505") (pin "24") (pinfunction "SDA/SDI_24") (pintype "bidirectional"))
      (node (ref "U506") (pin "7") (pinfunction "SDI/SDA_7") (pintype "bidirectional"))
      (node (ref "X503") (pin "8") (pinfunction "S_8") (pintype "passive"))
    )
    (net (code "231") (name "SPI_INT_SCK") (class "Default")
      (node (ref "U101") (pin "30") (pinfunction "PA5_30") (pintype "bidirectional"))
      (node (ref "U501") (pin "2") (pinfunction "SCL/SPC_2") (pintype "input"))
      (node (ref "U502") (pin "2") (pinfunction "SCL/SPC_2") (pintype "bidirectional"))
      (node (ref "U504") (pin "4") (pinfunction "SCL/SPC_4") (pintype "bidirectional"))
      (node (ref "U505") (pin "23") (pinfunction "SCL/SCLK_23") (pintype "bidirectional"))
      (node (ref "U506") (pin "8") (pinfunction "SCLK_8") (pintype "bidirectional"))
      (node (ref "X503") (pin "10") (pinfunction "S_10") (pintype "passive"))
    )
    (net (code "232") (name "VBAT") (class "Default")
      (node (ref "B601") (pin "1") (pinfunction "POS_1") (pintype "bidirectional"))
      (node (ref "R608") (pin "P$1") (pinfunction "1_P$1") (pintype "passive"))
      (node (ref "U101") (pin "6") (pinfunction "VBAT_6") (pintype "power_in"))
      (node (ref "U801") (pin "1") (pinfunction "VBAT_1") (pintype "power_in"))
    )
    (net (code "233") (name "VBUS") (class "Default")
      (node (ref "C1103") (pin "P$1") (pinfunction "1_P$1") (pintype "passive"))
      (node (ref "J301") (pin "VBUS") (pinfunction "1_VBUS") (pintype "power_in"))
      (node (ref "J302") (pin "1") (pinfunction "1_1") (pintype "passive"))
      (node (ref "R1112") (pin "P$1") (pinfunction "1_P$1") (pintype "passive"))
      (node (ref "U101") (pin "68") (pinfunction "PA9_68") (pintype "bidirectional"))
      (node (ref "U1101") (pin "P$19") (pinfunction "V3_P$19") (pintype "bidirectional"))
      (node (ref "U1104") (pin "P$7") (pinfunction "D_P$7") (pintype "passive"))
      (node (ref "U1104") (pin "P$8") (pinfunction "D_P$8") (pintype "passive"))
      (node (ref "U302") (pin "5") (pinfunction "VBUS_5") (pintype "bidirectional"))
      (node (ref "VBUS") (pin "P$1") (pinfunction "P$1_P$1") (pintype "passive"))
    )
    (net (code "234") (name "VDD_3V3_SENSORS") (class "Default")
      (node (ref "C501") (pin "P$1") (pinfunction "1_P$1") (pintype "passive"))
      (node (ref "C502") (pin "P$1") (pinfunction "1_P$1") (pintype "passive"))
      (node (ref "C503") (pin "P$1") (pinfunction "1_P$1") (pintype "passive"))
      (node (ref "C506") (pin "P$1") (pinfunction "1_P$1") (pintype "passive"))
      (node (ref "C507") (pin "P$1") (pinfunction "1_P$1") (pintype "passive"))
      (node (ref "C508") (pin "P$1") (pinfunction "1_P$1") (pintype "passive"))
      (node (ref "C511") (pin "P$1") (pinfunction "1_P$1") (pintype "passive"))
      (node (ref "C513") (pin "P$1") (pinfunction "1_P$1") (pintype "passive"))
      (node (ref "C514") (pin "P$1") (pinfunction "1_P$1") (pintype "passive"))
      (node (ref "C605") (pin "P$1") (pinfunction "1_P$1") (pintype "passive"))
      (node (ref "C617") (pin "P$1") (pinfunction "1_P$1") (pintype "passive"))
      (node (ref "Q601") (pin "E") (pinfunction "E_E") (pintype "passive"))
      (node (ref "U501") (pin "1") (pinfunction "VDD_IO_1") (pintype "bidirectional"))
      (node (ref "U501") (pin "15") (pinfunction "RES_P15_VDD_15") (pintype "bidirectional"))
      (node (ref "U501") (pin "16") (pinfunction "VDD_16") (pintype "bidirectional"))
      (node (ref "U502") (pin "1") (pinfunction "VDD_IO_1") (pintype "bidirectional"))
      (node (ref "U502") (pin "15") (pinfunction "VDD_15") (pintype "bidirectional"))
      (node (ref "U502") (pin "16") (pinfunction "VDD_16") (pintype "bidirectional"))
      (node (ref "U504") (pin "1") (pinfunction "VDD_IO_1") (pintype "bidirectional"))
      (node (ref "U504") (pin "14") (pinfunction "VDD_14") (pintype "bidirectional"))
      (node (ref "U505") (pin "13") (pinfunction "VDD_13") (pintype "bidirectional"))
      (node (ref "U506") (pin "1") (pinfunction "VDD_1") (pintype "bidirectional"))
      (node (ref "U603") (pin "8") (pinfunction "VOUT1_8") (pintype "bidirectional"))
      (node (ref "VDDA_3V1101") (pin "P$1") (pinfunction "P$1_P$1") (pintype "passive"))
      (node (ref "X503") (pin "1") (pinfunction "S_1") (pintype "passive"))
    )
    (net (code "235") (name "VDD_3V3_SENSORS_EN") (class "Default")
      (node (ref "R603") (pin "P$2") (pinfunction "2_P$2") (pintype "passive"))
      (node (ref "R620") (pin "P$2") (pinfunction "2_P$2") (pintype "passive"))
      (node (ref "R635") (pin "P$2") (pinfunction "2_P$2") (pintype "passive"))
      (node (ref "U101") (pin "2") (pinfunction "PE3_2") (pintype "bidirectional"))
      (node (ref "U603") (pin "5") (pinfunction "EN1_5") (pintype "bidirectional"))
    )
    (net (code "236") (name "VDD_3V3_SPEKTRUM") (class "Default")
      (node (ref "C1008") (pin "P$1") (pinfunction "1_P$1") (pintype "passive"))
      (node (ref "D801") (pin "C") (pinfunction "C_C") (pintype "passive"))
      (node (ref "J801") (pin "P$1") (pinfunction "P$1_P$1") (pintype "bidirectional"))
      (node (ref "U1002") (pin "8") (pinfunction "VOUT1_8") (pintype "bidirectional"))
    )
    (net (code "237") (name "VDD_3V3_SPEKTRUM_EN") (class "Default")
      (node (ref "R1002") (pin "P$2") (pinfunction "2_P$2") (pintype "passive"))
      (node (ref "U1002") (pin "5") (pinfunction "EN1_5") (pintype "bidirectional"))
      (node (ref "U801") (pin "2") (pinfunction "PC13_2") (pintype "bidirectional"))
    )
    (net (code "238") (name "VDD_5V_BRICK") (class "Default")
      (node (ref "C1101") (pin "P$1") (pinfunction "1_P$1") (pintype "passive"))
      (node (ref "J601") (pin "1") (pinfunction "1_1") (pintype "passive"))
      (node (ref "J601") (pin "2") (pinfunction "2_2") (pintype "passive"))
      (node (ref "R1105") (pin "P$1") (pinfunction "1_P$1") (pintype "passive"))
      (node (ref "U1101") (pin "P$21") (pinfunction "V1_P$21") (pintype "bidirectional"))
      (node (ref "U1102") (pin "P$7") (pinfunction "D_P$7") (pintype "passive"))
      (node (ref "U1102") (pin "P$8") (pinfunction "D_P$8") (pintype "passive"))
      (node (ref "VDD_5V_BRICK") (pin "P$1") (pinfunction "P$1_P$1") (pintype "passive"))
    )
    (net (code "239") (name "VDD_5V_HIPOWER") (class "Default")
      (node (ref "C614") (pin "P$1") (pinfunction "1_P$1") (pintype "passive"))
      (node (ref "L201") (pin "P$1") (pinfunction "P$1_P$1") (pintype "bidirectional"))
      (node (ref "U601") (pin "8") (pinfunction "OUT_8") (pintype "bidirectional"))
    )
    (net (code "240") (name "VDD_5V_IN") (class "Default")
      (node (ref "C1104") (pin "P$1") (pinfunction "1_P$1") (pintype "passive"))
      (node (ref "C702") (pin "P$1") (pinfunction "1_P$1") (pintype "passive"))
      (node (ref "F1001") (pin "1") (pinfunction "1_1") (pintype "bidirectional"))
      (node (ref "L603") (pin "P$1") (pinfunction "P$1_P$1") (pintype "bidirectional"))
      (node (ref "L701") (pin "P$1") (pinfunction "1_P$1") (pintype "passive"))
      (node (ref "LED701") (pin "A") (pinfunction "A_A") (pintype "passive"))
      (node (ref "LED704") (pin "A") (pinfunction "A_A") (pintype "passive"))
      (node (ref "R609") (pin "P$2") (pinfunction "2_P$2") (pintype "passive"))
      (node (ref "RN1101") (pin "5") (pinfunction "2_5") (pintype "passive"))
      (node (ref "RN1101") (pin "6") (pinfunction "2_6") (pintype "passive"))
      (node (ref "RN1101") (pin "7") (pinfunction "2_7") (pintype "passive"))
      (node (ref "U1101") (pin "P$12") (pinfunction "VOUT_P$12") (pintype "bidirectional"))
      (node (ref "U1102") (pin "P$5") (pinfunction "D_P$5") (pintype "passive"))
      (node (ref "U1102") (pin "P$6") (pinfunction "D_P$6") (pintype "passive"))
      (node (ref "U1103") (pin "P$5") (pinfunction "D_P$5") (pintype "passive"))
      (node (ref "U1103") (pin "P$6") (pinfunction "D_P$6") (pintype "passive"))
      (node (ref "U1104") (pin "P$5") (pinfunction "D_P$5") (pintype "passive"))
      (node (ref "U1104") (pin "P$6") (pinfunction "D_P$6") (pintype "passive"))
      (node (ref "U601") (pin "1") (pinfunction "IN_1") (pintype "bidirectional"))
      (node (ref "U602") (pin "1") (pinfunction "IN_1") (pintype "bidirectional"))
      (node (ref "U702") (pin "3") (pinfunction "VIN_3") (pintype "power_in"))
      (node (ref "U703") (pin "A1") (pinfunction "A_A1") (pintype "passive"))
      (node (ref "U703") (pin "A2") (pinfunction "A_A2") (pintype "passive"))
      (node (ref "U703") (pin "A3") (pinfunction "A_A3") (pintype "passive"))
      (node (ref "VDD_5V_IN") (pin "P$1") (pinfunction "P$1_P$1") (pintype "passive"))
    )
    (net (code "241") (name "VDD_5V_PERIPH") (class "Default")
      (node (ref "C618") (pin "P$1") (pinfunction "1_P$1") (pintype "passive"))
      (node (ref "L202") (pin "P$1") (pinfunction "P$1_P$1") (pintype "bidirectional"))
      (node (ref "L203") (pin "P$1") (pinfunction "P$1_P$1") (pintype "bidirectional"))
      (node (ref "L401") (pin "P$1") (pinfunction "P$1_P$1") (pintype "bidirectional"))
      (node (ref "L402") (pin "P$1") (pinfunction "P$1_P$1") (pintype "bidirectional"))
      (node (ref "L403") (pin "P$1") (pinfunction "P$1_P$1") (pintype "bidirectional"))
      (node (ref "L404") (pin "P$1") (pinfunction "P$1_P$1") (pintype "bidirectional"))
      (node (ref "U602") (pin "8") (pinfunction "OUT_8") (pintype "bidirectional"))
    )
    (net (code "242") (name "VDD_5V_SENS") (class "Default")
      (node (ref "R609") (pin "P$1") (pinfunction "1_P$1") (pintype "passive"))
      (node (ref "R610") (pin "P$1") (pinfunction "1_P$1") (pintype "passive"))
      (node (ref "U101") (pin "29") (pinfunction "PA4_29") (pintype "bidirectional"))
    )
    (net (code "243") (name "VDD_SERVO") (class "Default")
      (node (ref "C1102") (pin "P$1") (pinfunction "1_P$1") (pintype "passive"))
      (node (ref "D904") (pin "ANODE") (pinfunction "A_ANODE") (pintype "passive"))
      (node (ref "J901") (pin "11") (pinfunction "S_11") (pintype "passive"))
      (node (ref "J901") (pin "14") (pinfunction "S_14") (pintype "passive"))
      (node (ref "J901") (pin "17") (pinfunction "S_17") (pintype "passive"))
      (node (ref "J901") (pin "20") (pinfunction "S_20") (pintype "passive"))
      (node (ref "J901") (pin "23") (pinfunction "S_23") (pintype "passive"))
      (node (ref "J901") (pin "26") (pinfunction "S_26") (pintype "passive"))
      (node (ref "J901") (pin "29") (pinfunction "S_29") (pintype "passive"))
      (node (ref "J901") (pin "32") (pinfunction "S_32") (pintype "passive"))
      (node (ref "J901") (pin "35") (pinfunction "S_35") (pintype "passive"))
      (node (ref "J901") (pin "38") (pinfunction "S_38") (pintype "passive"))
      (node (ref "J901") (pin "41") (pinfunction "S_41") (pintype "passive"))
      (node (ref "J901") (pin "44") (pinfunction "S_44") (pintype "passive"))
      (node (ref "J901") (pin "47") (pinfunction "S_47") (pintype "passive"))
      (node (ref "J901") (pin "5") (pinfunction "S_5") (pintype "passive"))
      (node (ref "J901") (pin "8") (pinfunction "S_8") (pintype "passive"))
      (node (ref "R1109") (pin "P$1") (pinfunction "1_P$1") (pintype "passive"))
      (node (ref "R922") (pin "P$2") (pinfunction "2_P$2") (pintype "passive"))
      (node (ref "U1101") (pin "P$20") (pinfunction "V2_P$20") (pintype "bidirectional"))
      (node (ref "U1103") (pin "P$7") (pinfunction "D_P$7") (pintype "passive"))
      (node (ref "U1103") (pin "P$8") (pinfunction "D_P$8") (pintype "passive"))
      (node (ref "VDD_SERVO") (pin "P$1") (pinfunction "P$1_P$1") (pintype "passive"))
    )
    (net (code "244") (name "VDD_SERVO_IN") (class "Default")
      (node (ref "L901") (pin "P$2") (pinfunction "P$2_P$2") (pintype "bidirectional"))
      (node (ref "U1001") (pin "1") (pinfunction "IN_1") (pintype "bidirectional"))
    )
    (net (code "245") (name "VDD_SERVO_SENS") (class "Default")
      (node (ref "R918") (pin "P$1") (pinfunction "1_P$1") (pintype "passive"))
      (node (ref "R919") (pin "P$2") (pinfunction "2_P$2") (pintype "passive"))
      (node (ref "U801") (pin "14") (pinfunction "PA4_14") (pintype "bidirectional"))
    )
    (net (code "246") (name "unconnected-(J301-4-PadID)") (class "Default")
      (node (ref "J301") (pin "ID") (pinfunction "4_ID") (pintype "passive"))
    )
    (net (code "247") (name "unconnected-(JX301A-S-Pad10)") (class "Default")
      (node (ref "JX301") (pin "10") (pinfunction "S_10") (pintype "passive"))
    )
    (net (code "248") (name "unconnected-(JX301F-S-Pad8)") (class "Default")
      (node (ref "JX301") (pin "8") (pinfunction "S_8") (pintype "passive"))
    )
    (net (code "249") (name "unconnected-(JX802A-S-Pad10)") (class "Default")
      (node (ref "JX802") (pin "10") (pinfunction "S_10") (pintype "passive"))
    )
    (net (code "250") (name "unconnected-(JX802F-S-Pad8)") (class "Default")
      (node (ref "JX802") (pin "8") (pinfunction "S_8") (pintype "passive"))
    )
    (net (code "251") (name "unconnected-(U101I-PC1-Pad16)") (class "Default")
      (node (ref "U101") (pin "16") (pinfunction "PC1_16") (pintype "bidirectional"))
    )
    (net (code "252") (name "unconnected-(U202-A1-Pad1)") (class "Default")
      (node (ref "U202") (pin "1") (pinfunction "A1_1") (pintype "bidirectional"))
    )
    (net (code "253") (name "unconnected-(U202-A2-Pad3)") (class "Default")
      (node (ref "U202") (pin "3") (pinfunction "A2_3") (pintype "bidirectional"))
    )
    (net (code "254") (name "unconnected-(U202-B1-Pad20)") (class "Default")
      (node (ref "U202") (pin "20") (pinfunction "B1_20") (pintype "bidirectional"))
    )
    (net (code "255") (name "unconnected-(U202-B2-Pad18)") (class "Default")
      (node (ref "U202") (pin "18") (pinfunction "B2_18") (pintype "bidirectional"))
    )
    (net (code "256") (name "unconnected-(U501-INT1-Pad7)") (class "Default")
      (node (ref "U501") (pin "7") (pinfunction "INT1_7") (pintype "output"))
    )
    (net (code "257") (name "unconnected-(U502-DEN-Pad8)") (class "Default")
      (node (ref "U502") (pin "8") (pinfunction "DEN_8") (pintype "bidirectional"))
    )
    (net (code "258") (name "unconnected-(U502-INT1-Pad7)") (class "Default")
      (node (ref "U502") (pin "7") (pinfunction "INT1_7") (pintype "bidirectional"))
    )
    (net (code "259") (name "unconnected-(U505-AUX_CL-Pad7)") (class "Default")
      (node (ref "U505") (pin "7") (pinfunction "AUX_CL_7") (pintype "bidirectional"))
    )
    (net (code "260") (name "unconnected-(U505-AUX_DA-Pad6)") (class "Default")
      (node (ref "U505") (pin "6") (pinfunction "AUX_DA_6") (pintype "bidirectional"))
    )
    (net (code "261") (name "unconnected-(U505-CLKOUT-Pad22)") (class "Default")
      (node (ref "U505") (pin "22") (pinfunction "CLKOUT_22") (pintype "bidirectional"))
    )
    (net (code "262") (name "unconnected-(U505-FSYNC-Pad11)") (class "Default")
      (node (ref "U505") (pin "11") (pinfunction "FSYNC_11") (pintype "bidirectional"))
    )
    (net (code "263") (name "unconnected-(U505-NC1-Pad2)") (class "Default")
      (node (ref "U505") (pin "2") (pinfunction "NC1_2") (pintype "bidirectional"))
    )
    (net (code "264") (name "unconnected-(U505-NC2-Pad3)") (class "Default")
      (node (ref "U505") (pin "3") (pinfunction "NC2_3") (pintype "bidirectional"))
    )
    (net (code "265") (name "unconnected-(U505-NC3-Pad4)") (class "Default")
      (node (ref "U505") (pin "4") (pinfunction "NC3_4") (pintype "bidirectional"))
    )
    (net (code "266") (name "unconnected-(U505-NC4-Pad5)") (class "Default")
      (node (ref "U505") (pin "5") (pinfunction "NC4_5") (pintype "bidirectional"))
    )
    (net (code "267") (name "unconnected-(U505-NC5-Pad14)") (class "Default")
      (node (ref "U505") (pin "14") (pinfunction "NC5_14") (pintype "bidirectional"))
    )
    (net (code "268") (name "unconnected-(U505-NC6-Pad15)") (class "Default")
      (node (ref "U505") (pin "15") (pinfunction "NC6_15") (pintype "bidirectional"))
    )
    (net (code "269") (name "unconnected-(U505-NC7-Pad16)") (class "Default")
      (node (ref "U505") (pin "16") (pinfunction "NC7_16") (pintype "bidirectional"))
    )
    (net (code "270") (name "unconnected-(U505-NC8-Pad17)") (class "Default")
      (node (ref "U505") (pin "17") (pinfunction "NC8_17") (pintype "bidirectional"))
    )
    (net (code "271") (name "unconnected-(U505-RESV1-Pad19)") (class "Default")
      (node (ref "U505") (pin "19") (pinfunction "RESV1_19") (pintype "bidirectional"))
    )
    (net (code "272") (name "unconnected-(U505-RESV2-Pad21)") (class "Default")
      (node (ref "U505") (pin "21") (pinfunction "RESV2_21") (pintype "bidirectional"))
    )
    (net (code "273") (name "unconnected-(U506-CSB1-Pad4)") (class "Default")
      (node (ref "U506") (pin "4") (pinfunction "CSB1_4") (pintype "bidirectional"))
    )
    (net (code "274") (name "unconnected-(U801B-PA11-Pad32)") (class "Default")
      (node (ref "U801") (pin "32") (pinfunction "PA11_32") (pintype "bidirectional"))
    )
    (net (code "275") (name "unconnected-(U801D-PB12-Pad25)") (class "Default")
      (node (ref "U801") (pin "25") (pinfunction "PB12_25") (pintype "bidirectional"))
    )
    (net (code "276") (name "unconnected-(U801E-PB6-Pad42)") (class "Default")
      (node (ref "U801") (pin "42") (pinfunction "PB6_42") (pintype "bidirectional"))
    )
    (net (code "277") (name "unconnected-(U801E-PB7-Pad43)") (class "Default")
      (node (ref "U801") (pin "43") (pinfunction "PB7_43") (pintype "bidirectional"))
    )
    (net (code "278") (name "unconnected-(U801F-PC14-Pad3)") (class "Default")
      (node (ref "U801") (pin "3") (pinfunction "PC14_3") (pintype "bidirectional"))
    )
    (net (code "279") (name "unconnected-(U801F-PC15-Pad4)") (class "Default")
      (node (ref "U801") (pin "4") (pinfunction "PC15_4") (pintype "bidirectional"))
    )
    (net (code "280") (name "unconnected-(U901-A7-Pad8)") (class "Default")
      (node (ref "U901") (pin "8") (pinfunction "A7_8") (pintype "bidirectional"))
    )
    (net (code "281") (name "unconnected-(U901-A8-Pad9)") (class "Default")
      (node (ref "U901") (pin "9") (pinfunction "A8_9") (pintype "bidirectional"))
    )
    (net (code "282") (name "unconnected-(U901-B7-Pad13)") (class "Default")
      (node (ref "U901") (pin "13") (pinfunction "B7_13") (pintype "bidirectional"))
    )
    (net (code "283") (name "unconnected-(U901-B8-Pad12)") (class "Default")
      (node (ref "U901") (pin "12") (pinfunction "B8_12") (pintype "bidirectional"))
    )
    (net (code "284") (name "unconnected-(U1101-CAS-PadP$11)") (class "Default")
      (node (ref "U1101") (pin "P$11") (pinfunction "CAS_P$11") (pintype "bidirectional"))
    )
    (net (code "285") (name "unconnected-(U1101-EN-PadP$22)") (class "Default")
      (node (ref "U1101") (pin "P$22") (pinfunction "EN_P$22") (pintype "bidirectional"))
    )
    (net (code "286") (name "unconnected-(U1101-~{SHDN}-PadP$23)") (class "Default")
      (node (ref "U1101") (pin "P$23") (pinfunction "~{SHDN}_P$23") (pintype "bidirectional"))
    )
    (net (code "287") (name "~{ACCEL_MAG_CS}") (class "Default")
      (node (ref "U101") (pin "9") (pinfunction "PC15_9") (pintype "bidirectional"))
      (node (ref "U504") (pin "8") (pinfunction "CS_8") (pintype "bidirectional"))
      (node (ref "X503") (pin "6") (pinfunction "S_6") (pintype "passive"))
    )
    (net (code "288") (name "~{BARO_CS}") (class "Default")
      (node (ref "U101") (pin "88") (pinfunction "PD7_88") (pintype "bidirectional"))
      (node (ref "U506") (pin "5") (pinfunction "CSB2_5") (pintype "bidirectional"))
    )
    (net (code "289") (name "~{FMU-LED_AMBER}") (class "Default")
      (node (ref "R707") (pin "P$1") (pinfunction "1_P$1") (pintype "passive"))
      (node (ref "U101") (pin "43") (pinfunction "PE12_43") (pintype "bidirectional"))
    )
    (net (code "290") (name "~{FRAM_CS}") (class "Default")
      (node (ref "U101") (pin "57") (pinfunction "PD10_57") (pintype "bidirectional"))
      (node (ref "U102") (pin "1") (pinfunction "~{S}_1") (pintype "bidirectional"))
    )
    (net (code "291") (name "~{GYRO_CS}") (class "Default")
      (node (ref "U101") (pin "7") (pinfunction "PC13_7") (pintype "bidirectional"))
      (node (ref "U501") (pin "5") (pinfunction "CS_5") (pintype "input"))
      (node (ref "U502") (pin "5") (pinfunction "CS_5") (pintype "bidirectional"))
      (node (ref "X503") (pin "7") (pinfunction "S_7") (pintype "passive"))
    )
    (net (code "292") (name "~{IO-LED_AMBER}") (class "Default")
      (node (ref "R709") (pin "P$1") (pinfunction "1_P$1") (pintype "passive"))
      (node (ref "U801") (pin "28") (pinfunction "PB15_28") (pintype "bidirectional"))
    )
    (net (code "293") (name "~{IO-LED_BLUE}") (class "Default")
      (node (ref "R712") (pin "P$1") (pinfunction "1_P$1") (pintype "passive"))
      (node (ref "U801") (pin "27") (pinfunction "PB14_27") (pintype "bidirectional"))
    )
    (net (code "294") (name "~{IO-LED_SAFETY}") (class "Default")
      (node (ref "R710") (pin "P$2") (pinfunction "2_P$2") (pintype "passive"))
      (node (ref "U801") (pin "26") (pinfunction "PB13_26") (pintype "bidirectional"))
    )
    (net (code "295") (name "~{MPU_CS}") (class "Default")
      (node (ref "U101") (pin "17") (pinfunction "PC2_17") (pintype "bidirectional"))
      (node (ref "U505") (pin "8") (pinfunction "/CS_8") (pintype "bidirectional"))
    )
    (net (code "296") (name "~{SBUS_OUTPUT_EN}") (class "Default")
      (node (ref "U801") (pin "40") (pinfunction "PB4_40") (pintype "bidirectional"))
      (node (ref "U903") (pin "7") (pinfunction "~{2OE}_7") (pintype "input"))
    )
    (net (code "297") (name "~{SPI_EXT_NSS}") (class "Default")
      (node (ref "J403") (pin "5") (pinfunction "5_5") (pintype "passive"))
      (node (ref "U101") (pin "3") (pinfunction "PE4_3") (pintype "bidirectional"))
    )
    (net (code "298") (name "~{VBUS_VALID}") (class "Default")
      (node (ref "!VBUS_VALID") (pin "P$1") (pinfunction "P$1_P$1") (pintype "passive"))
      (node (ref "RN1101") (pin "2") (pinfunction "1_2") (pintype "passive"))
      (node (ref "U101") (pin "15") (pinfunction "PC0_15") (pintype "bidirectional"))
      (node (ref "U1101") (pin "P$9") (pinfunction "~{VALID3}_P$9") (pintype "bidirectional"))
    )
    (net (code "299") (name "~{VDD_5V_HIPOWER_OC}") (class "Default")
      (node (ref "R602") (pin "P$1") (pinfunction "1_P$1") (pintype "passive"))
      (node (ref "U101") (pin "41") (pinfunction "PE10_41") (pintype "bidirectional"))
      (node (ref "U601") (pin "4") (pinfunction "~{FAULT}_4") (pintype "bidirectional"))
    )
    (net (code "300") (name "~{VDD_5V_PERIPH_EN}") (class "Default")
      (node (ref "R615") (pin "P$1") (pinfunction "1_P$1") (pintype "passive"))
      (node (ref "U101") (pin "67") (pinfunction "PA8_67") (pintype "bidirectional"))
      (node (ref "U601") (pin "5") (pinfunction "~{CE}_5") (pintype "bidirectional"))
      (node (ref "U602") (pin "5") (pinfunction "~{CE}_5") (pintype "bidirectional"))
    )
    (net (code "301") (name "~{VDD_5V_PERIPH_OC}") (class "Default")
      (node (ref "R604") (pin "P$1") (pinfunction "1_P$1") (pintype "passive"))
      (node (ref "U101") (pin "46") (pinfunction "PE15_46") (pintype "bidirectional"))
      (node (ref "U602") (pin "4") (pinfunction "~{FAULT}_4") (pintype "bidirectional"))
    )
    (net (code "302") (name "~{VDD_BRICK_VALID}") (class "Default")
      (node (ref "!VDD_BRICK_VALID") (pin "P$1") (pinfunction "P$1_P$1") (pintype "passive"))
      (node (ref "RN1101") (pin "4") (pinfunction "1_4") (pintype "passive"))
      (node (ref "U101") (pin "91") (pinfunction "PB5_91") (pintype "bidirectional"))
      (node (ref "U1101") (pin "P$7") (pinfunction "~{VALID1}_P$7") (pintype "bidirectional"))
    )
    (net (code "303") (name "~{VDD_SERVO_VALID}") (class "Default")
      (node (ref "!VDD_SERVO_VALID") (pin "P$1") (pinfunction "P$1_P$1") (pintype "passive"))
      (node (ref "RN1101") (pin "3") (pinfunction "1_3") (pintype "passive"))
      (node (ref "U101") (pin "93") (pinfunction "PB7_93") (pintype "bidirectional"))
      (node (ref "U1101") (pin "P$8") (pinfunction "~{VALID2}_P$8") (pintype "bidirectional"))
    )
  )
)
